# PUMA-10S_V2_1.net
KiCad netlist of a schematic drawn in Altium Designer
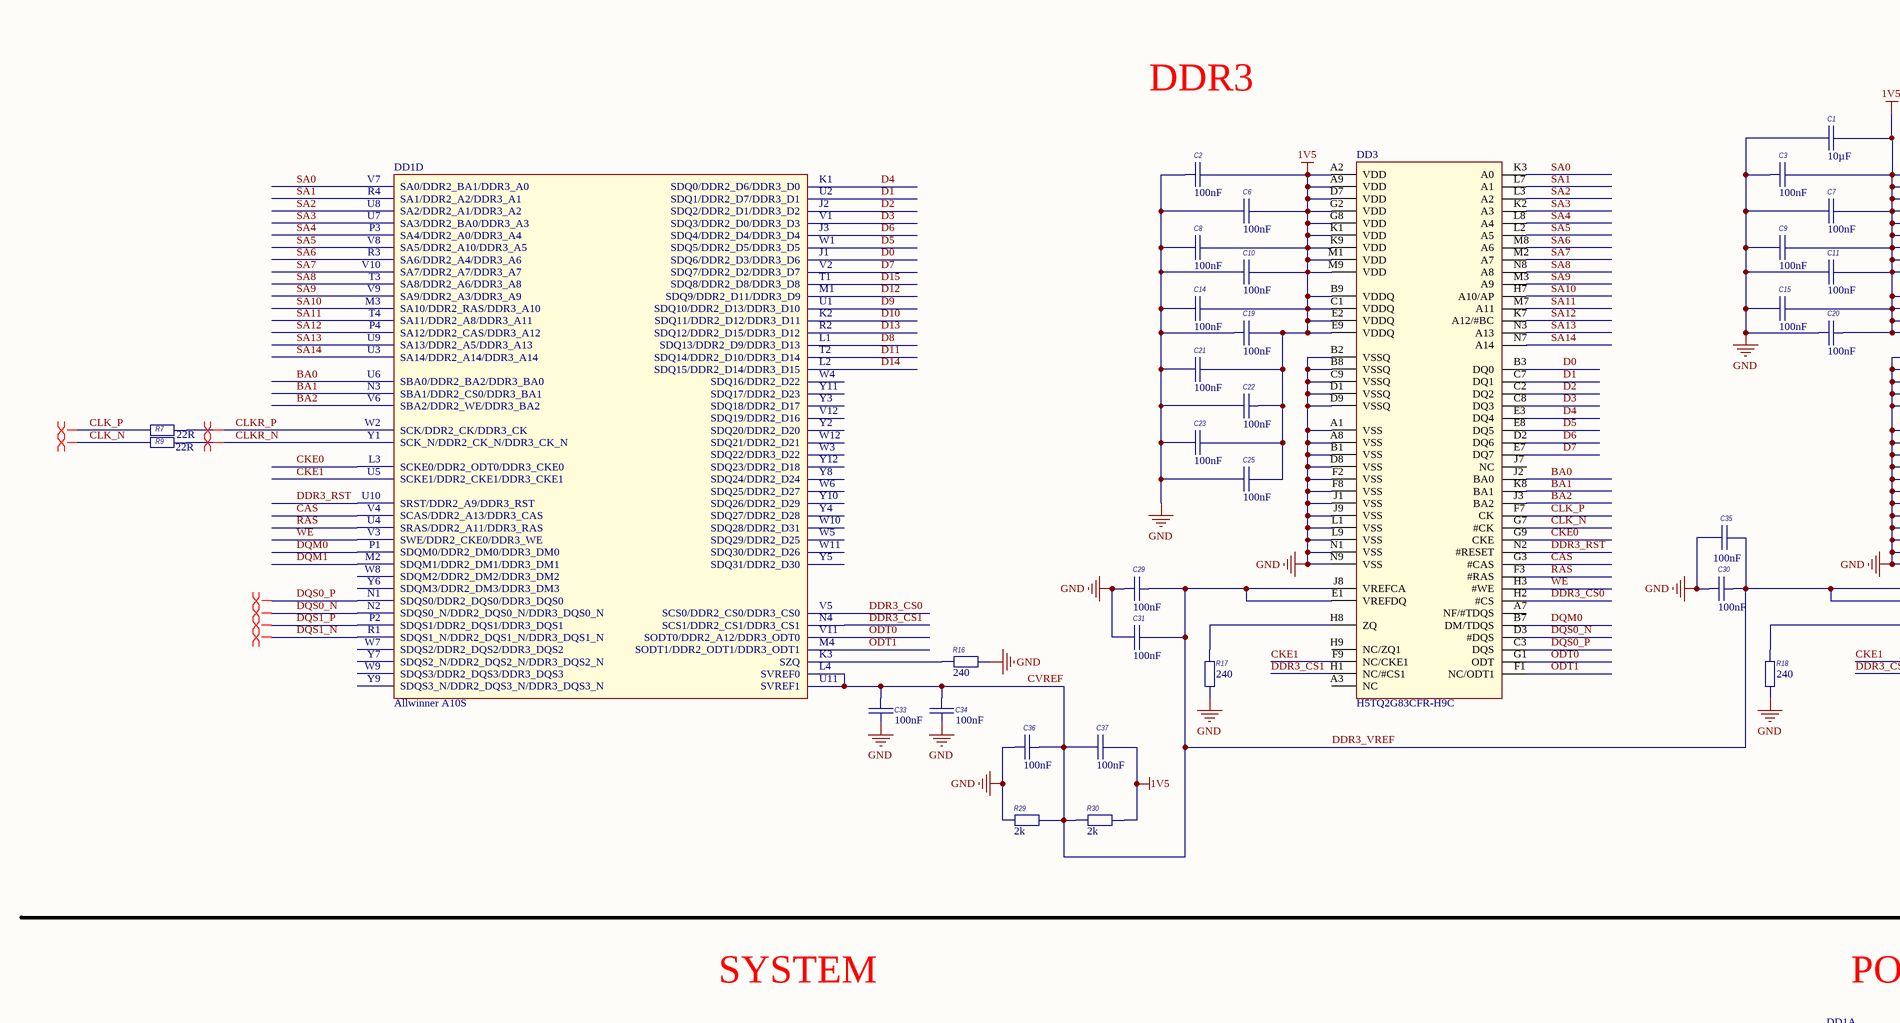
[diagram p0: PUMA-10S_V2.1.SchDoc, top left]
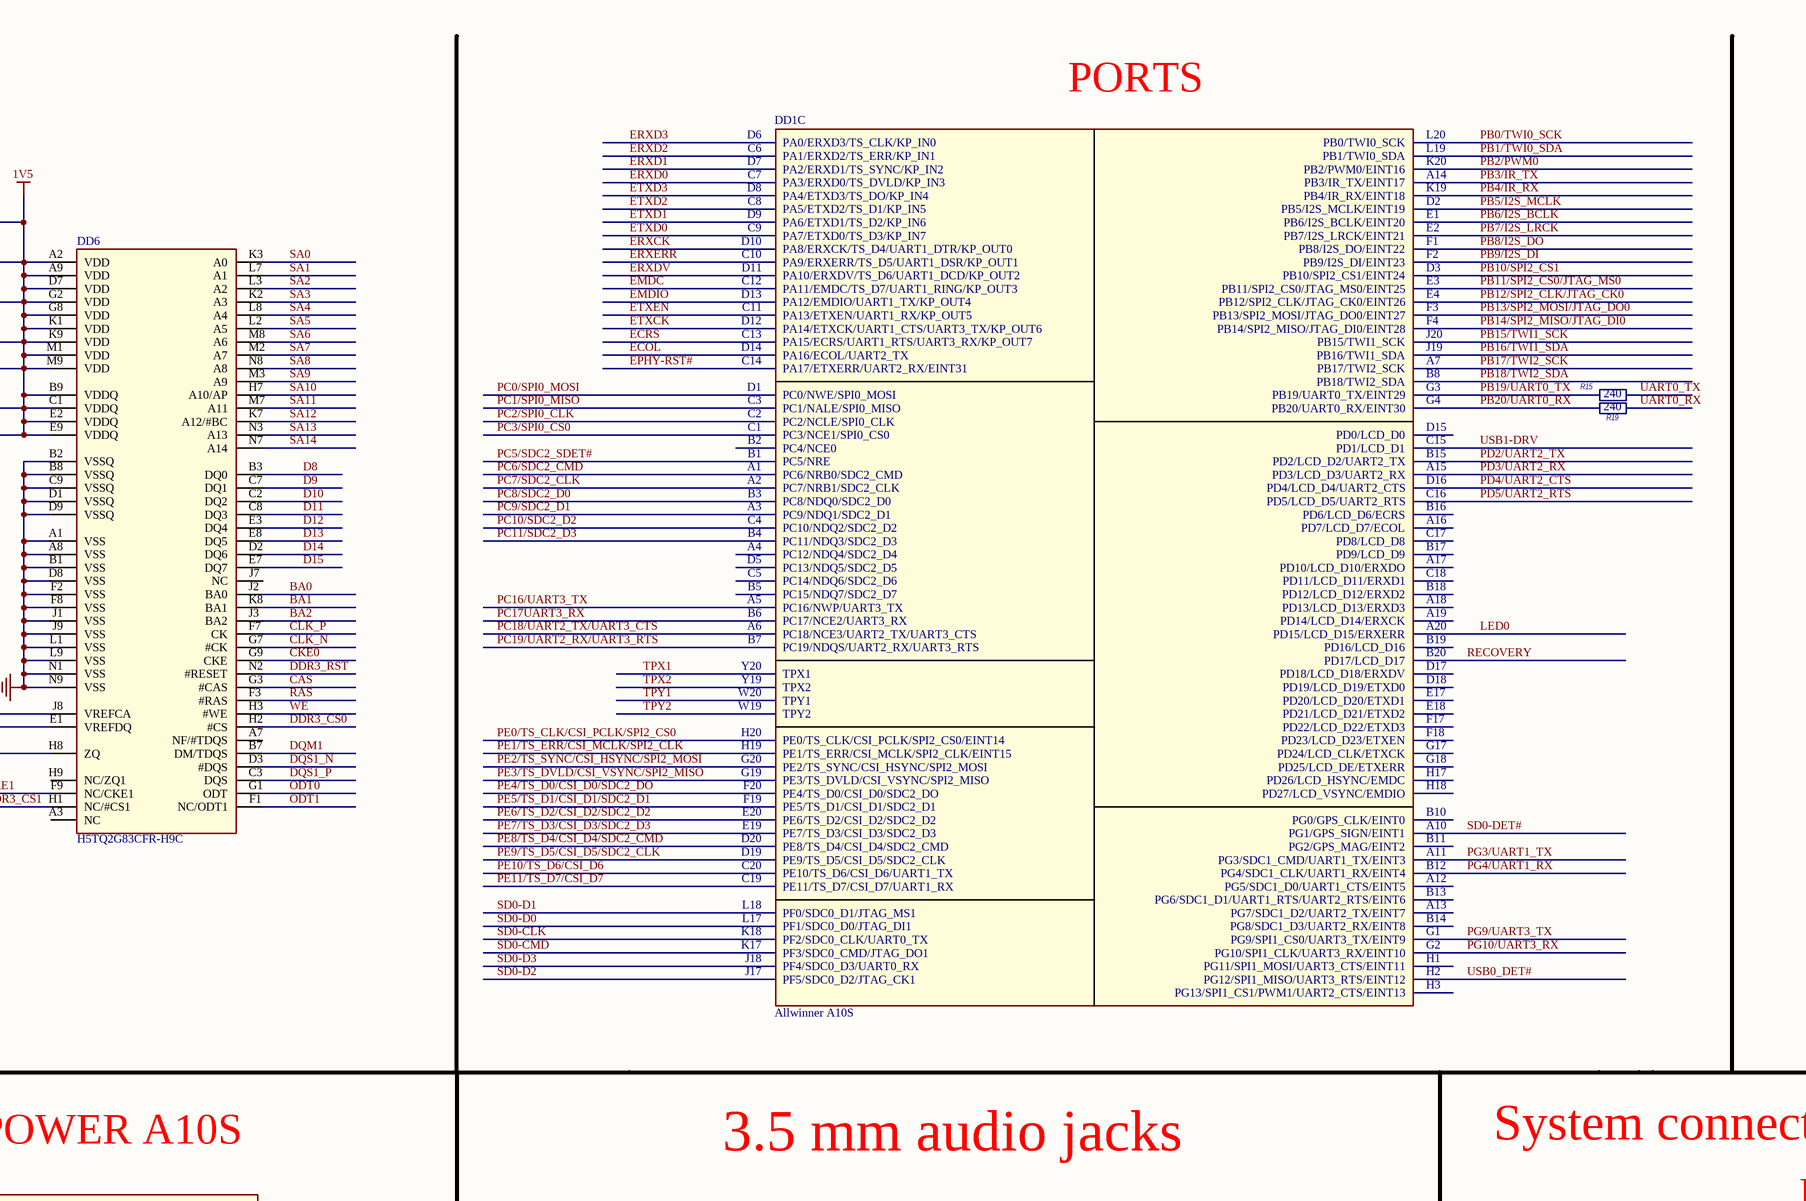
[diagram p1: PUMA-10S_V2.1.SchDoc, top middle]
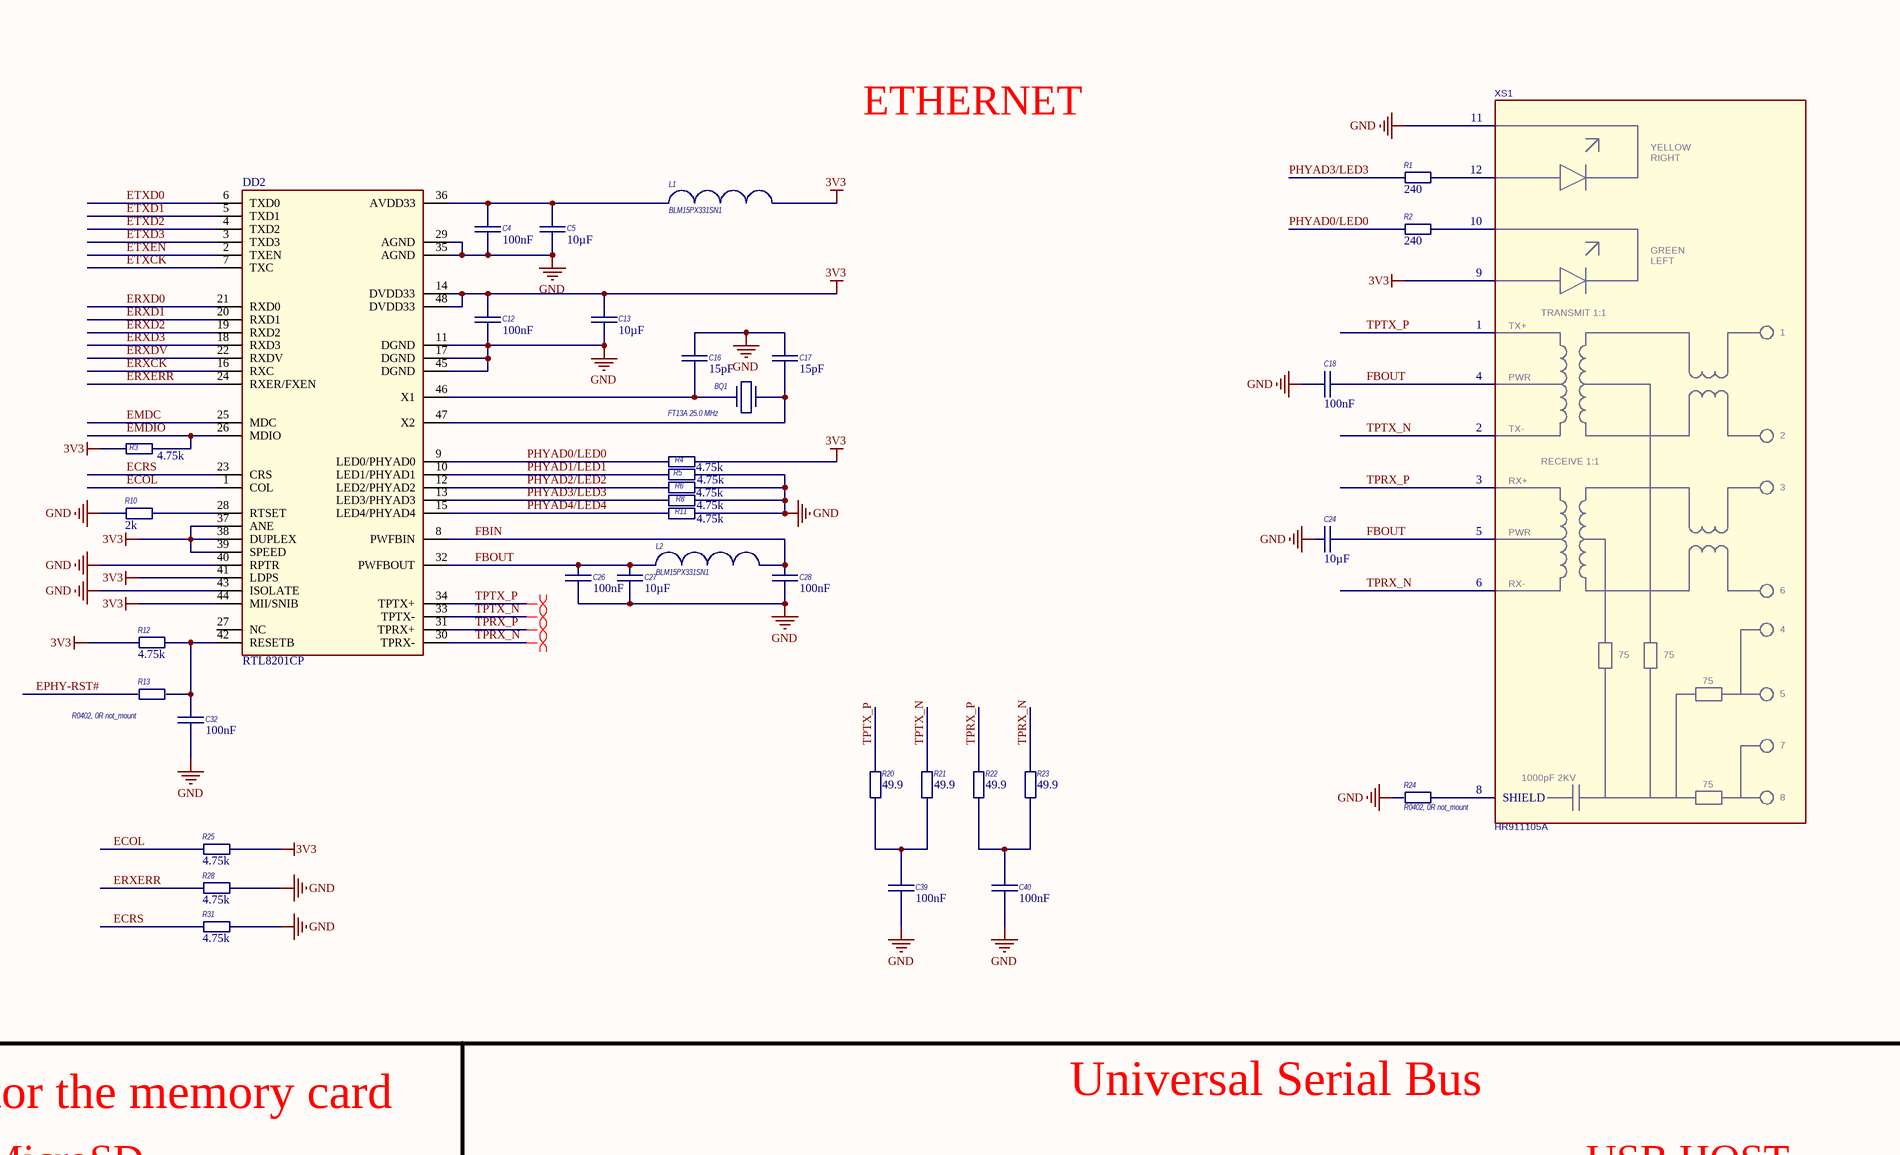
[diagram p2: PUMA-10S_V2.1.SchDoc, top right]
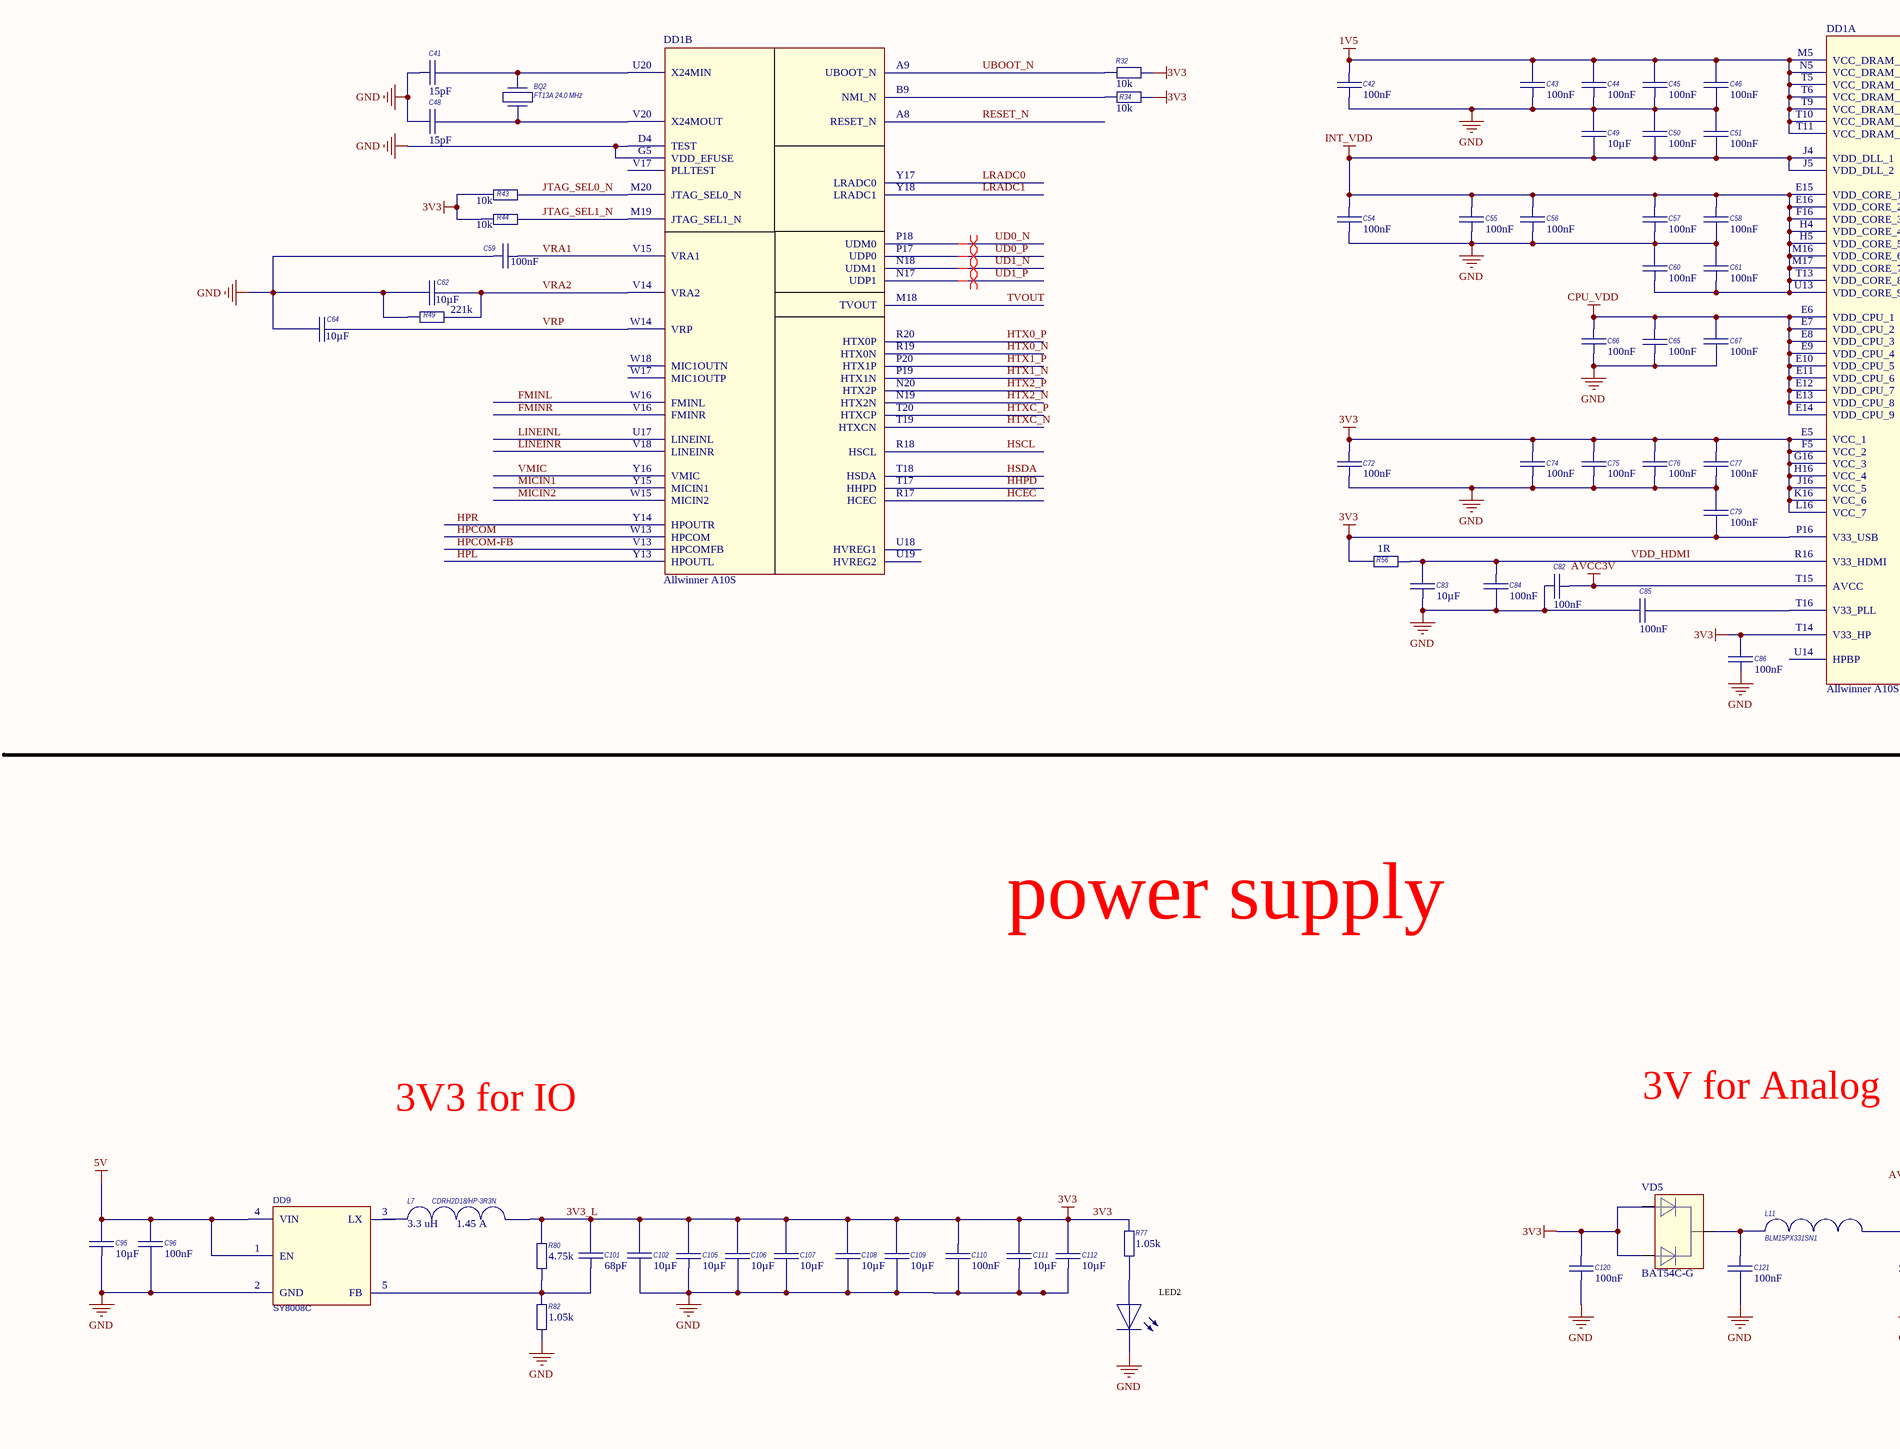
[diagram p3: PUMA-10S_V2.1.SchDoc, centre left]
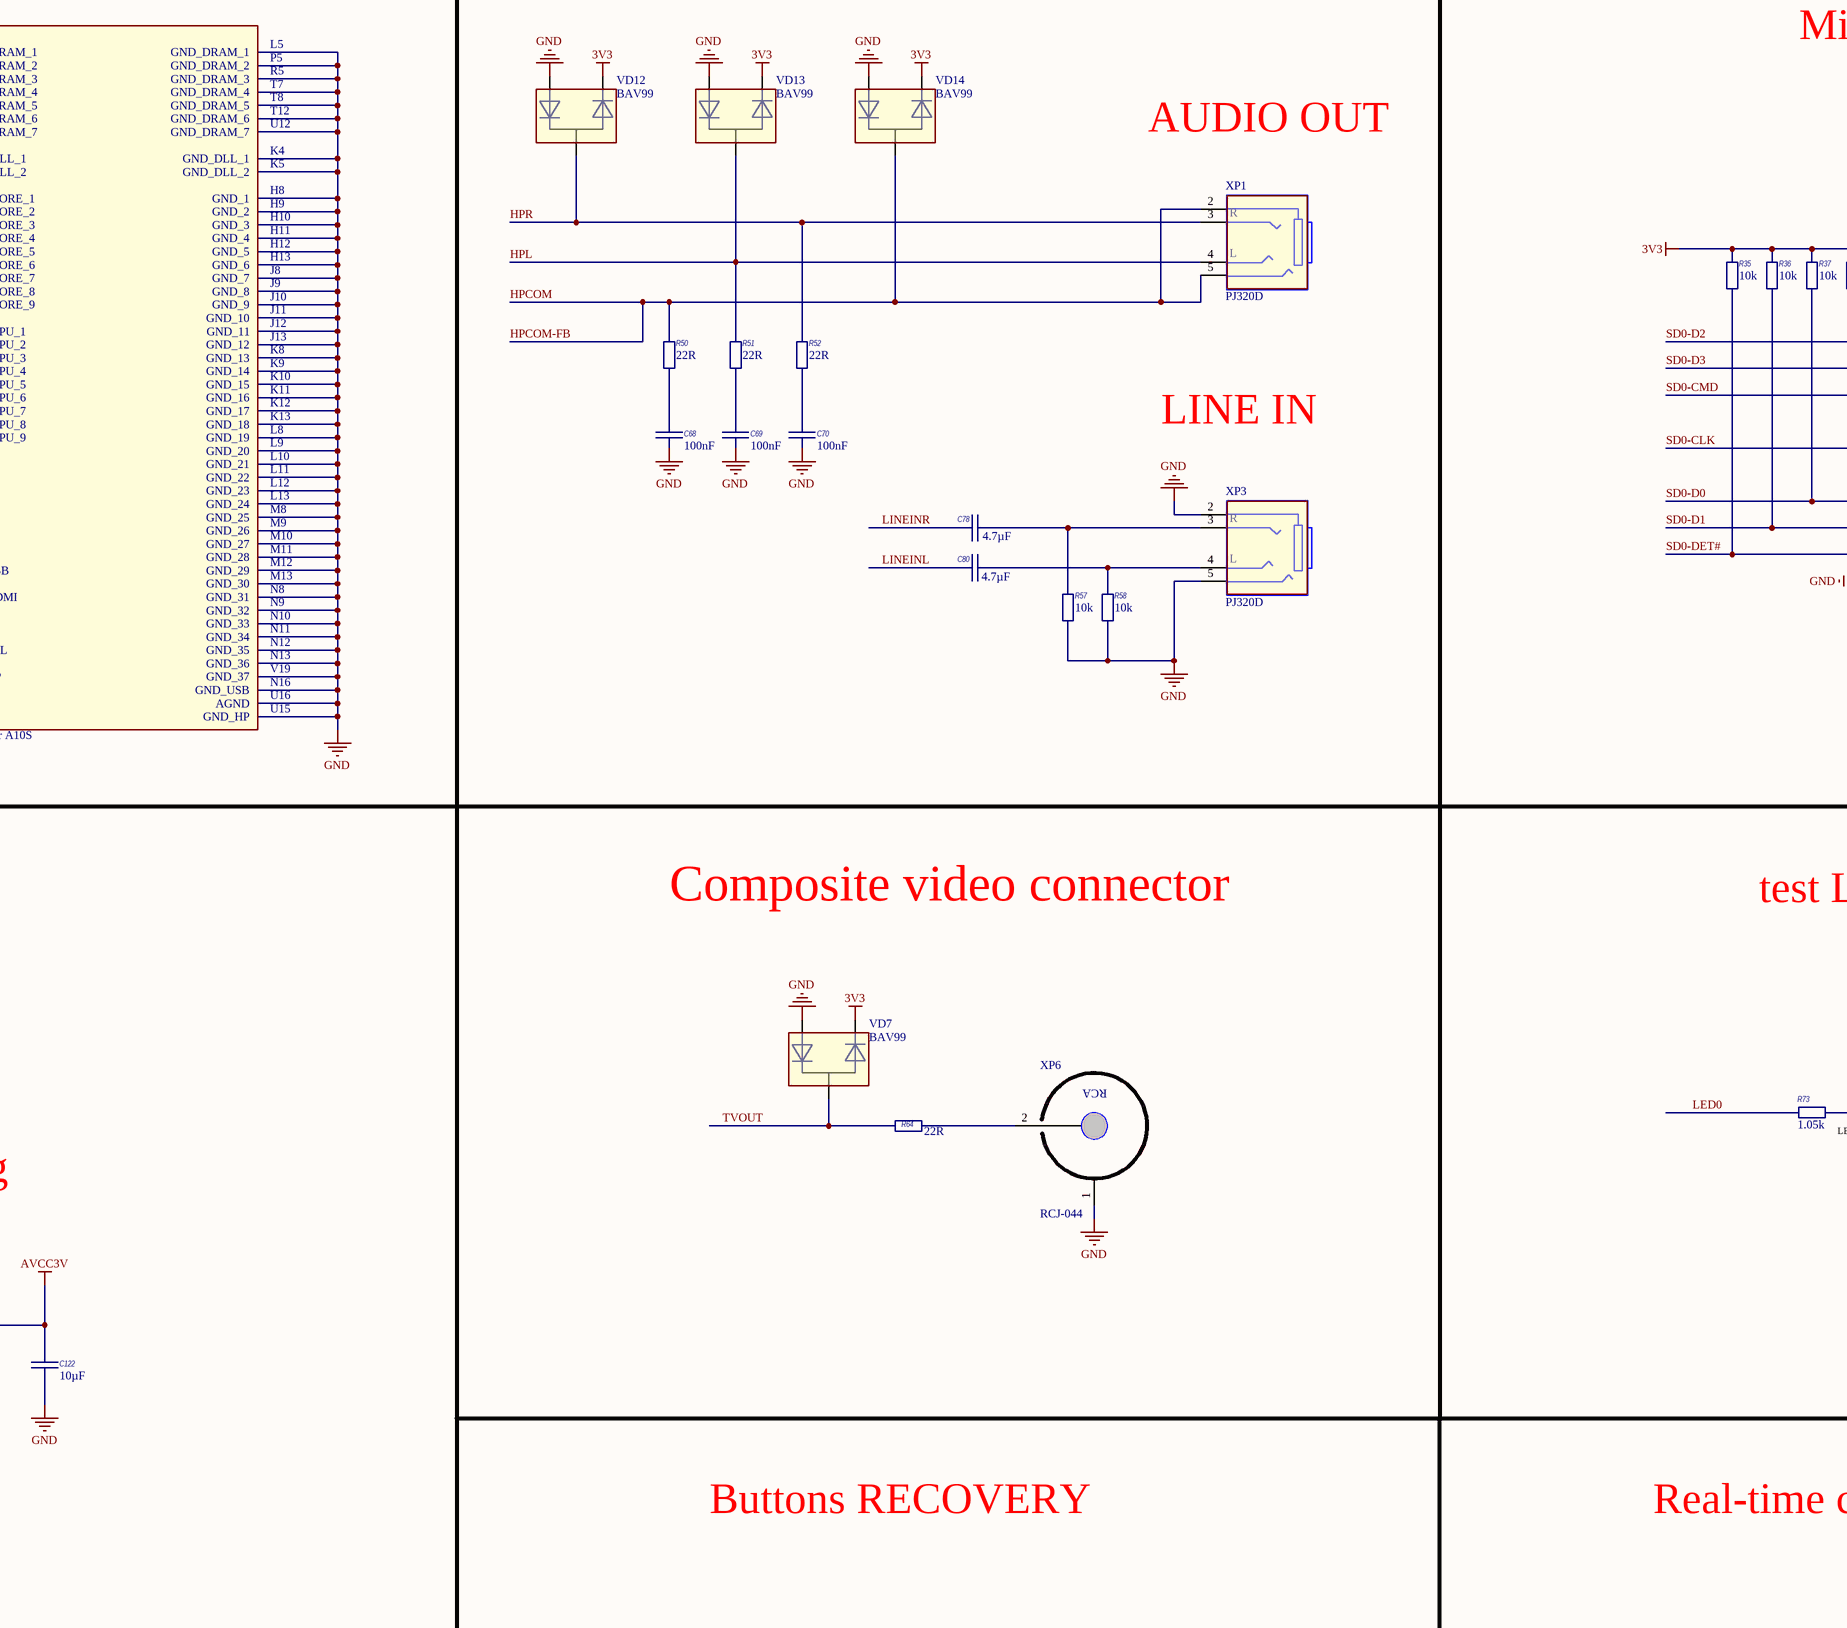
[diagram p4: PUMA-10S_V2.1.SchDoc, centre middle]
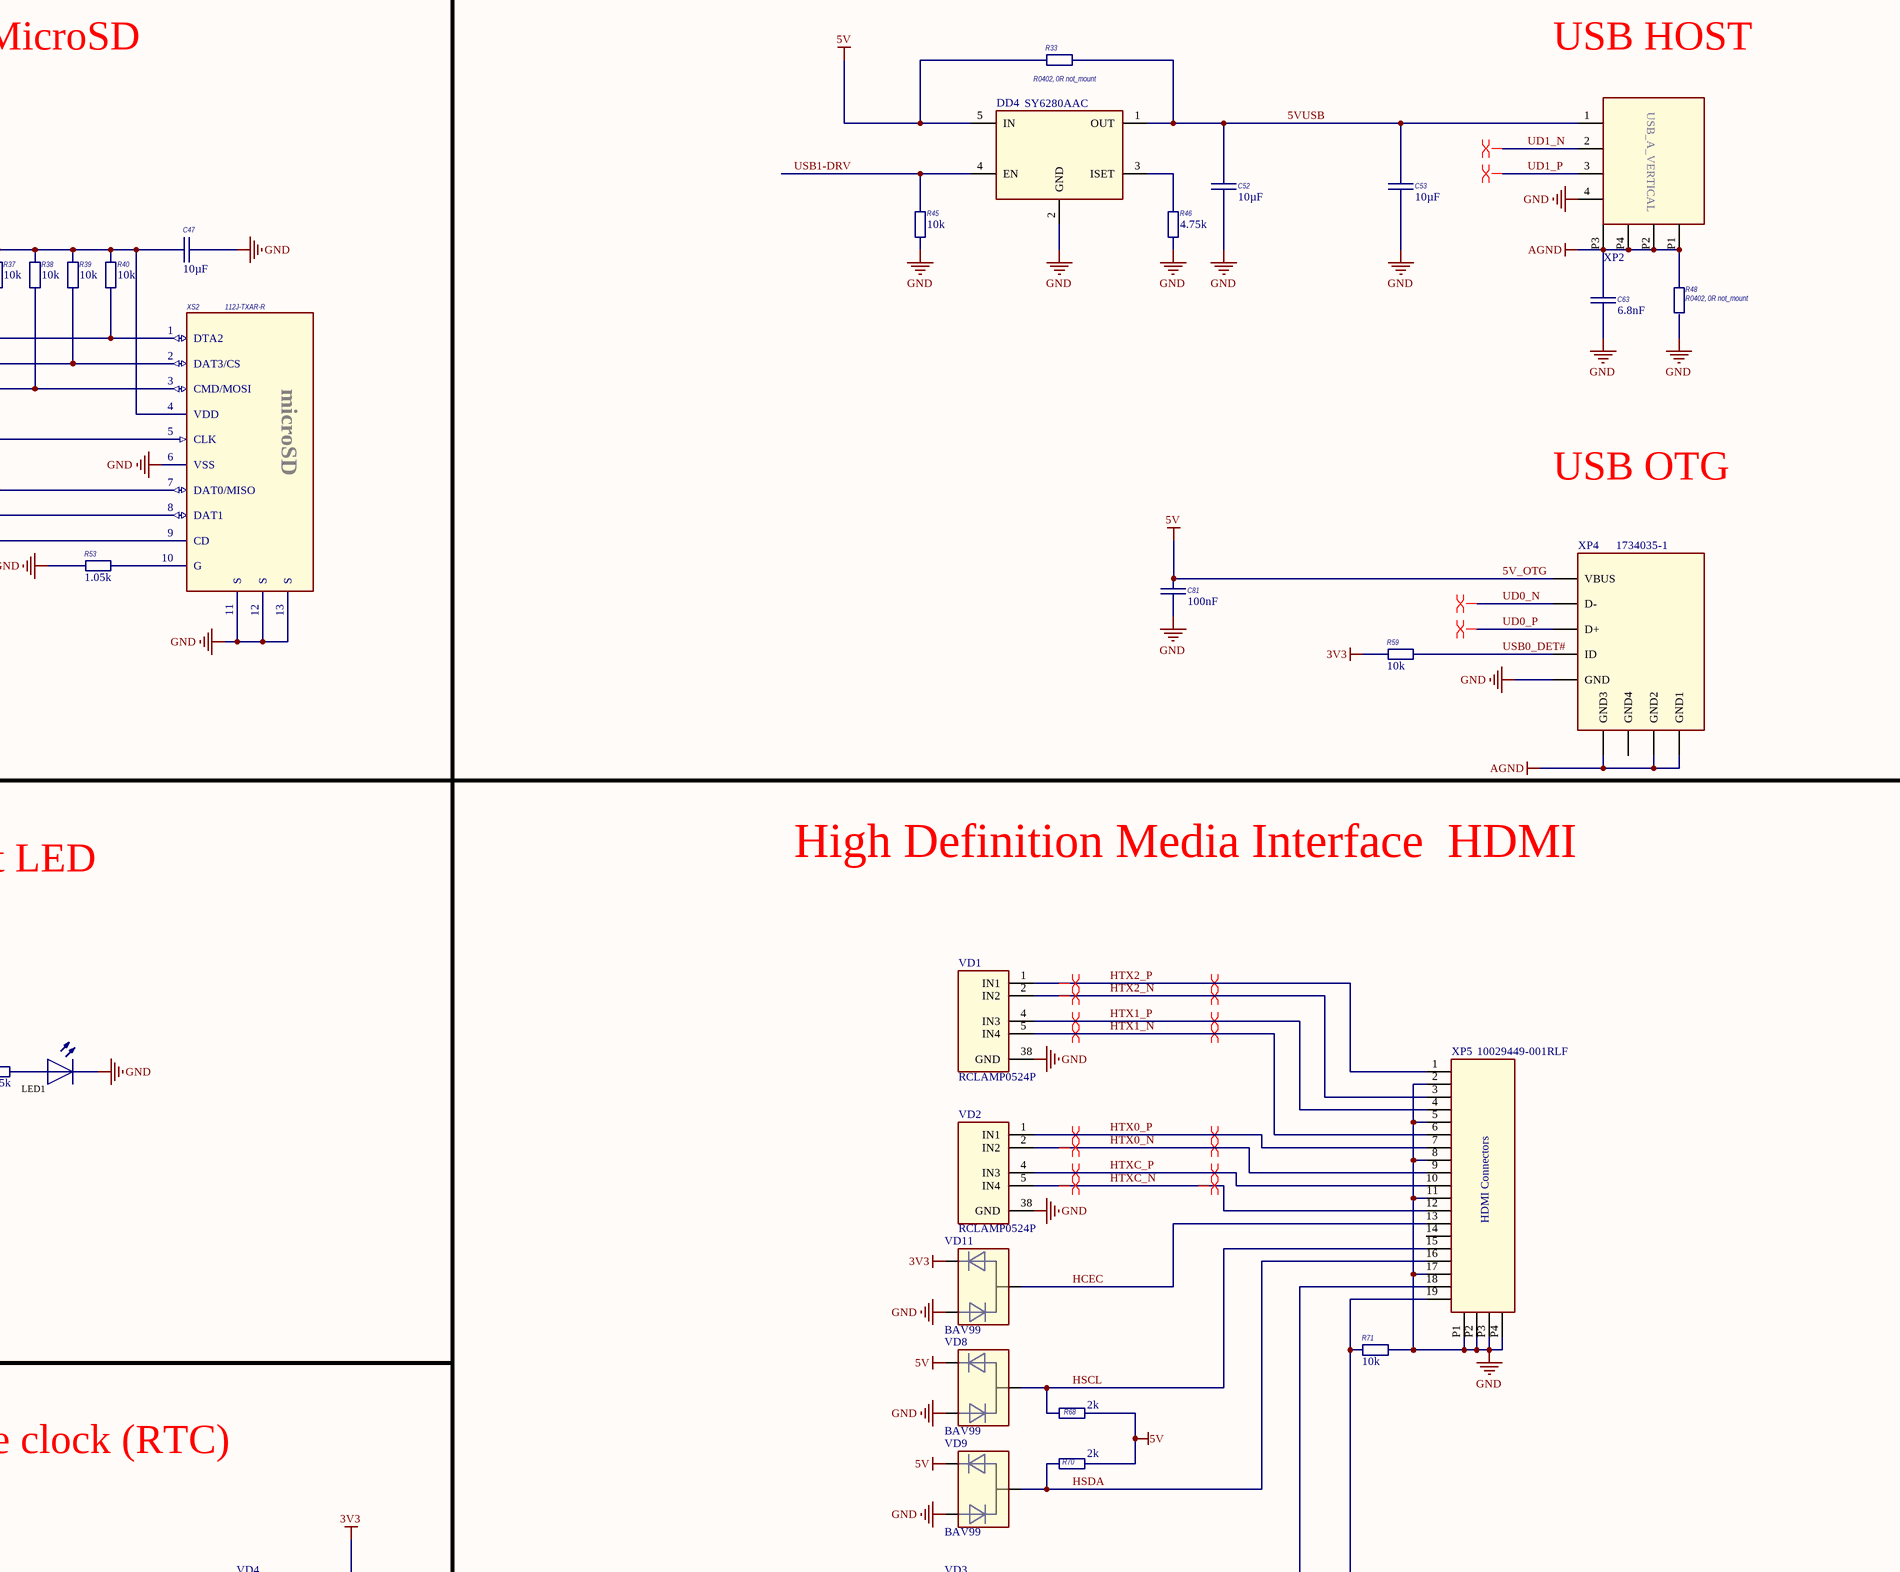
[diagram p5: PUMA-10S_V2.1.SchDoc, centre right]
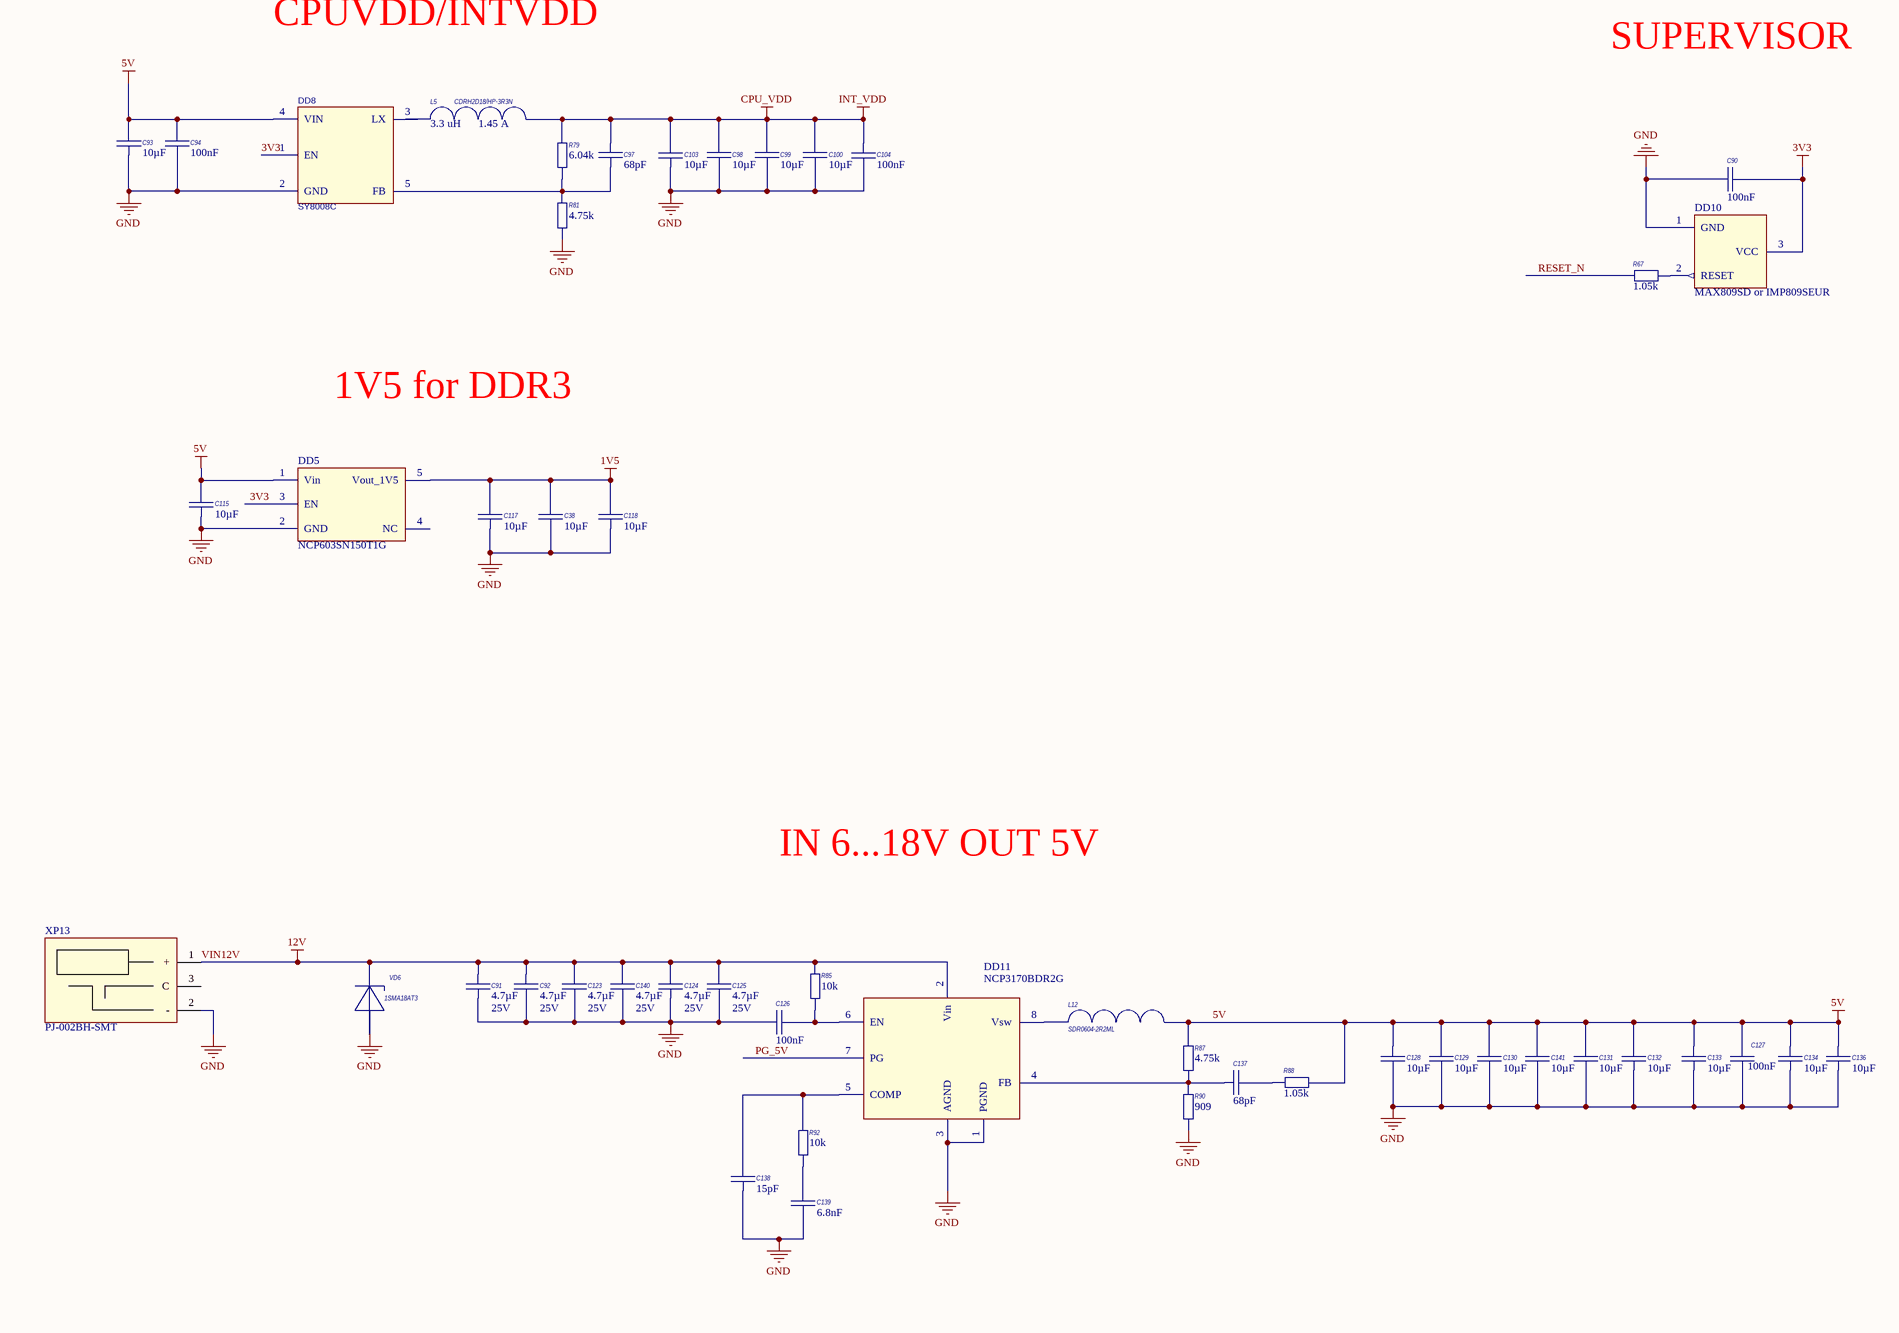
[diagram p6: PUMA-10S_V2.1.SchDoc, bottom left]
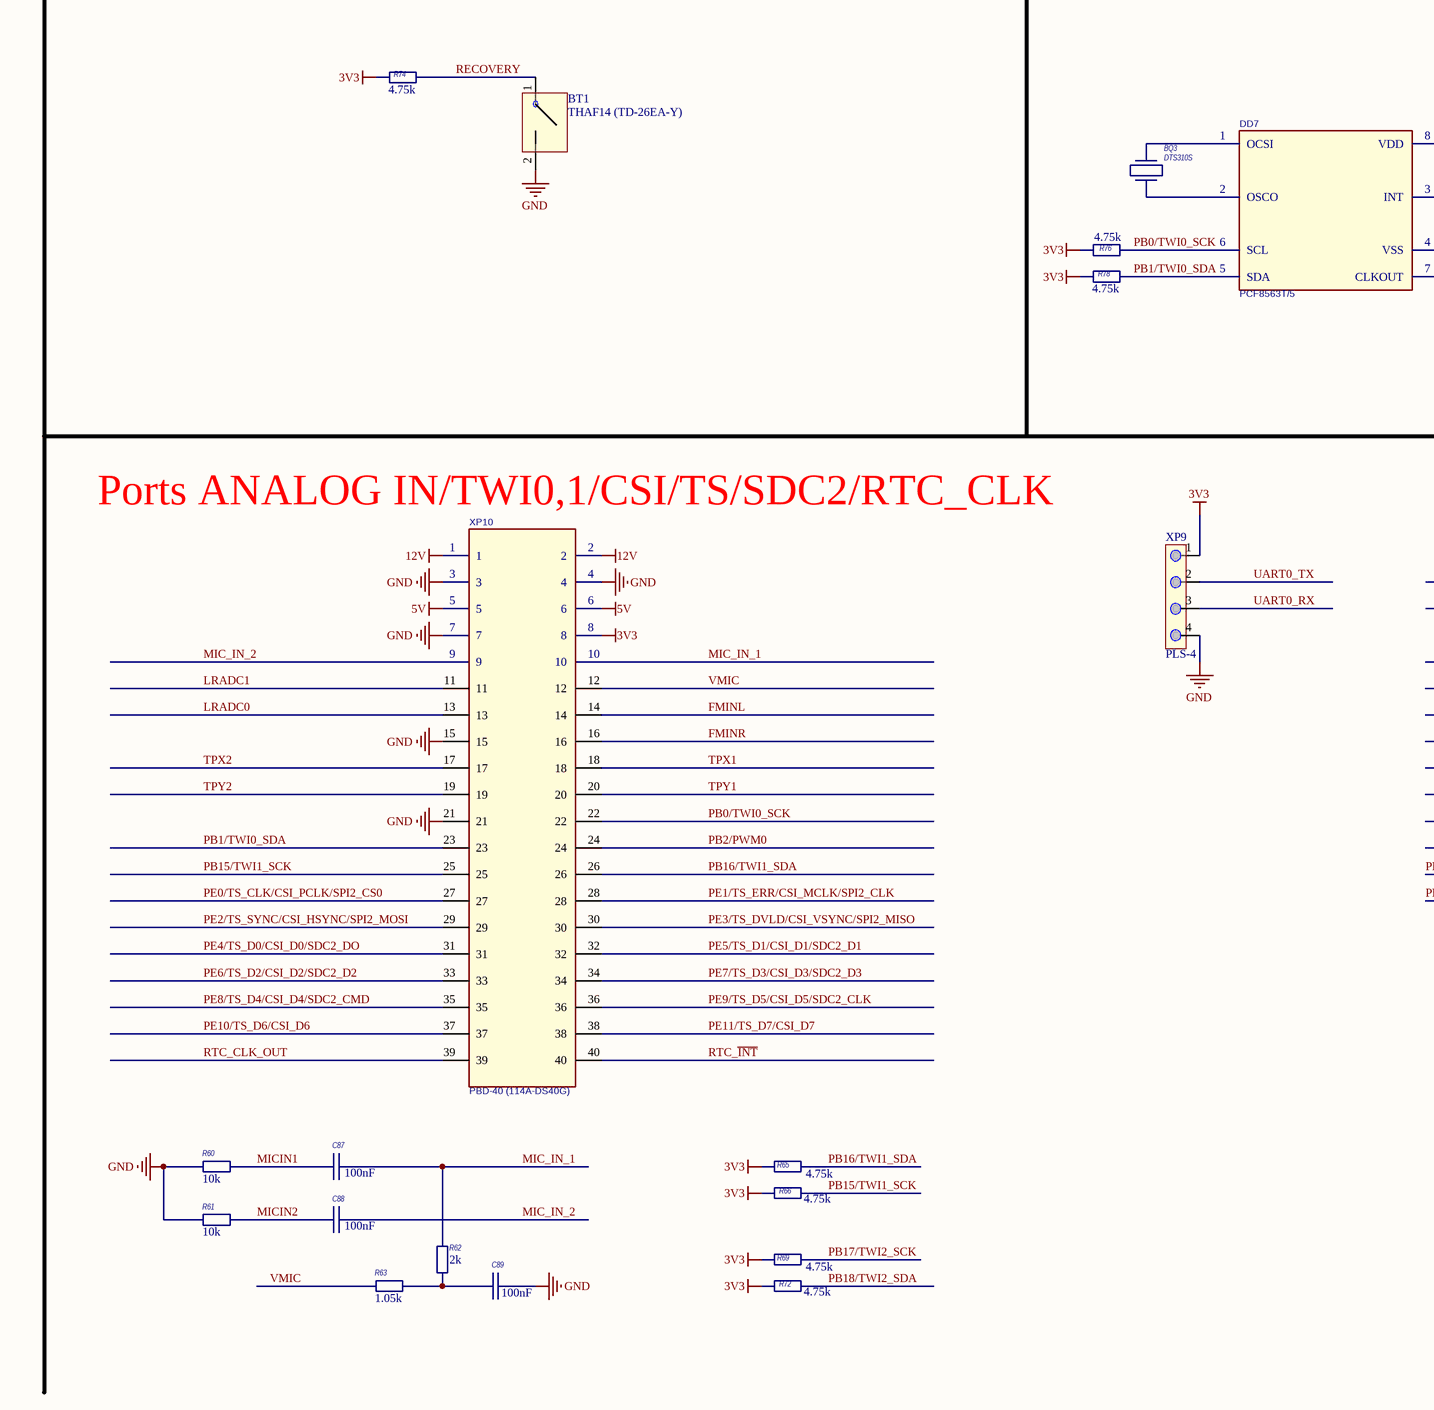
[diagram p7: PUMA-10S_V2.1.SchDoc, bottom middle]
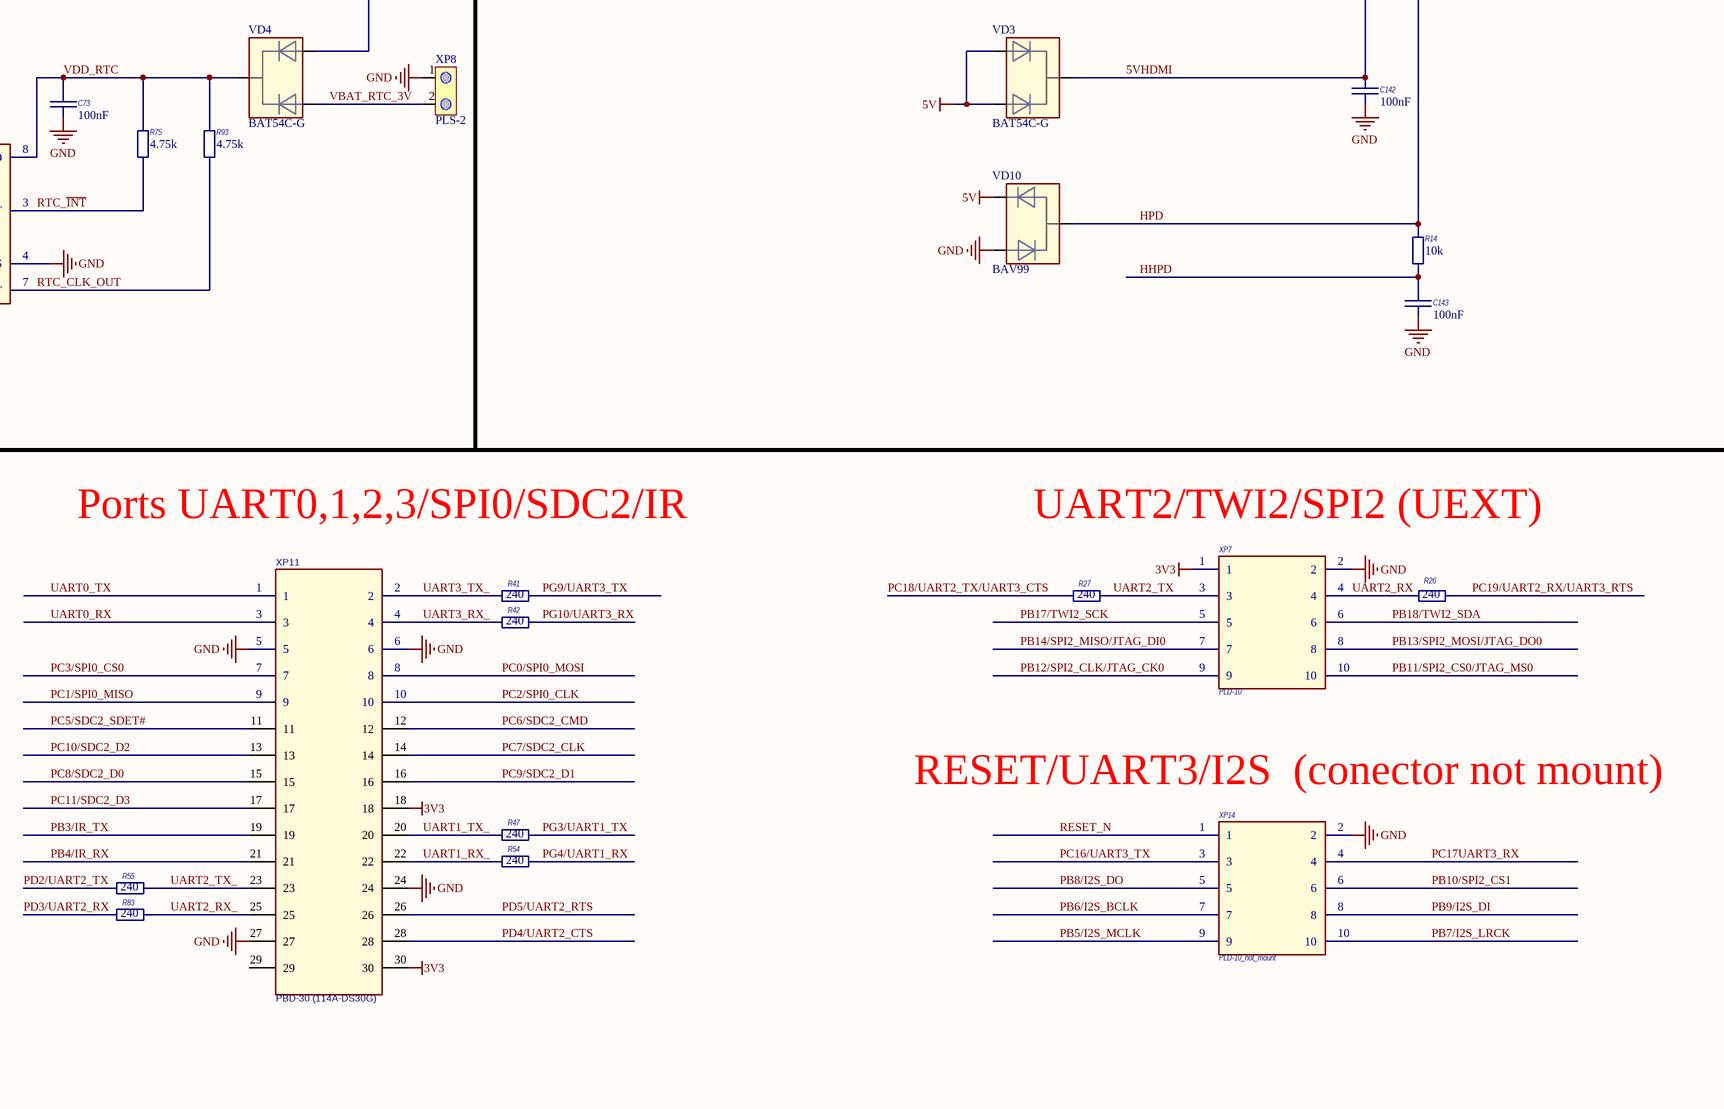
[diagram p8: PUMA-10S_V2.1.SchDoc, bottom right]

(export (version "E")
  (design (tool "Eeschema 10.0.6"))
  (components
    (comp (ref "BQ1")
      (value "FT13A 25.0 MHz")
      (footprint "3225")
      (description "CRYSTAL 25MHZ, 16pF, 50PPM, 3.2x2.5mm")
      (libsource (lib "CRYSTALS") (part "FT13A 25.0 MHz"))
    )
    (comp (ref "BQ2")
      (value "FT13A 24.0 MHz")
      (footprint "3225")
      (description "CRYSTAL 24MHZ, 16pF, 50PPM, 3.2x2.5mm")
      (libsource (lib "CRYSTALS") (part "FT13A 24.0 MHz"))
    )
    (comp (ref "BQ3")
      (value "DTS310S")
      (footprint "3215")
      (description "Crystal Resonator 32.768kHz, 12.5pF 30PPM")
      (libsource (lib "CRYSTALS") (part "Crystal Resonator 32.768kHz, 12.5pF 30PPM"))
    )
    (comp (ref "BT1")
      (value "THAF14 (TD-26EA-Y)")
      (footprint "THAF14")
      (description "Horizontal Push Tact Switch")
      (libsource (lib "PUMA-10S") (part "THAF14"))
    )
    (comp (ref "C1")
      (value "GRM188R60J106ME47")
      (footprint "C0603")
      (description "C0603 10uF 6.3V X5R")
      (fields
        (field (name "MANUFACTURER") "Murata Electronics North America")
        (field (name "MANUFACTURER PART NUMBER") "GRM188R60J106ME47D")
        (field (name "CAPACITANCE") "10µF")
      )
      (libsource (lib "CAPACITORS") (part "GRM188R60J106ME47"))
    )
    (comp (ref "C2")
      (value "GRM155R71C104KA88")
      (footprint "C0402_IPC High Density")
      (description "C0402, 100nF,  16V, X7R")
      (fields
        (field (name "MANUFACTURER") "MURATA")
        (field (name "MANUFACTURER PART NUMBER") "GRM155R71C104KA88D")
        (field (name "CAPACITANCE") "100nF")
      )
      (libsource (lib "CAPACITORS") (part "GRM155R71C104KA88"))
    )
    (comp (ref "C3")
      (value "GRM155R71C104KA88")
      (footprint "C0402_IPC High Density")
      (description "C0402, 100nF,  16V, X7R")
      (fields
        (field (name "MANUFACTURER") "MURATA")
        (field (name "MANUFACTURER PART NUMBER") "GRM155R71C104KA88D")
        (field (name "CAPACITANCE") "100nF")
      )
      (libsource (lib "CAPACITORS") (part "GRM155R71C104KA88"))
    )
    (comp (ref "C4")
      (value "GRM155R71C104KA88")
      (footprint "C0402_IPC High Density")
      (description "C0402, 100nF,  16V, X7R")
      (fields
        (field (name "MANUFACTURER") "MURATA")
        (field (name "MANUFACTURER PART NUMBER") "GRM155R71C104KA88D")
        (field (name "CAPACITANCE") "100nF")
      )
      (libsource (lib "CAPACITORS") (part "GRM155R71C104KA88"))
    )
    (comp (ref "C5")
      (value "GRM188R60J106ME47")
      (footprint "C0603")
      (description "C0603 10uF 6.3V X5R")
      (fields
        (field (name "MANUFACTURER") "Murata Electronics North America")
        (field (name "TOLERANCE") "±20%")
        (field (name "CAPACITANCE") "10µF")
      )
      (libsource (lib "CAPACITORS") (part "GRM188R60J106ME47"))
    )
    (comp (ref "C6")
      (value "GRM155R71C104KA88")
      (footprint "C0402_IPC High Density")
      (description "C0402, 100nF,  16V, X7R")
      (fields
        (field (name "MANUFACTURER") "MURATA")
        (field (name "MANUFACTURER PART NUMBER") "GRM155R71C104KA88D")
        (field (name "CAPACITANCE") "100nF")
      )
      (libsource (lib "CAPACITORS") (part "GRM155R71C104KA88"))
    )
    (comp (ref "C7")
      (value "GRM155R71C104KA88")
      (footprint "C0402_IPC High Density")
      (description "C0402, 100nF,  16V, X7R")
      (fields
        (field (name "MANUFACTURER") "MURATA")
        (field (name "MANUFACTURER PART NUMBER") "GRM155R71C104KA88D")
        (field (name "CAPACITANCE") "100nF")
      )
      (libsource (lib "CAPACITORS") (part "GRM155R71C104KA88"))
    )
    (comp (ref "C8")
      (value "GRM155R71C104KA88")
      (footprint "C0402_IPC High Density")
      (description "C0402, 100nF,  16V, X7R")
      (fields
        (field (name "MANUFACTURER") "MURATA")
        (field (name "MANUFACTURER PART NUMBER") "GRM155R71C104KA88D")
        (field (name "CAPACITANCE") "100nF")
      )
      (libsource (lib "CAPACITORS") (part "GRM155R71C104KA88"))
    )
    (comp (ref "C9")
      (value "GRM155R71C104KA88")
      (footprint "C0402_IPC High Density")
      (description "C0402, 100nF,  16V, X7R")
      (fields
        (field (name "MANUFACTURER") "MURATA")
        (field (name "MANUFACTURER PART NUMBER") "GRM155R71C104KA88D")
        (field (name "CAPACITANCE") "100nF")
      )
      (libsource (lib "CAPACITORS") (part "GRM155R71C104KA88"))
    )
    (comp (ref "C10")
      (value "GRM155R71C104KA88")
      (footprint "C0402_IPC High Density")
      (description "C0402, 100nF,  16V, X7R")
      (fields
        (field (name "MANUFACTURER") "MURATA")
        (field (name "MANUFACTURER PART NUMBER") "GRM155R71C104KA88D")
        (field (name "CAPACITANCE") "100nF")
      )
      (libsource (lib "CAPACITORS") (part "GRM155R71C104KA88"))
    )
    (comp (ref "C11")
      (value "GRM155R71C104KA88")
      (footprint "C0402_IPC High Density")
      (description "C0402, 100nF,  16V, X7R")
      (fields
        (field (name "MANUFACTURER") "MURATA")
        (field (name "MANUFACTURER PART NUMBER") "GRM155R71C104KA88D")
        (field (name "CAPACITANCE") "100nF")
      )
      (libsource (lib "CAPACITORS") (part "GRM155R71C104KA88"))
    )
    (comp (ref "C12")
      (value "GRM155R71C104KA88")
      (footprint "C0402_IPC High Density")
      (description "C0402, 100nF,  16V, X7R")
      (fields
        (field (name "MANUFACTURER") "MURATA")
        (field (name "MANUFACTURER PART NUMBER") "GRM155R71C104KA88D")
        (field (name "CAPACITANCE") "100nF")
      )
      (libsource (lib "CAPACITORS") (part "GRM155R71C104KA88"))
    )
    (comp (ref "C13")
      (value "GRM188R60J106ME47")
      (footprint "C0603")
      (description "C0603 10uF 6.3V X5R")
      (fields
        (field (name "MANUFACTURER") "Murata Electronics North America")
        (field (name "TOLERANCE") "±20%")
        (field (name "CAPACITANCE") "10µF")
      )
      (libsource (lib "CAPACITORS") (part "GRM188R60J106ME47"))
    )
    (comp (ref "C14")
      (value "GRM155R71C104KA88")
      (footprint "C0402_IPC High Density")
      (description "C0402, 100nF,  16V, X7R")
      (fields
        (field (name "MANUFACTURER") "MURATA")
        (field (name "MANUFACTURER PART NUMBER") "GRM155R71C104KA88D")
        (field (name "CAPACITANCE") "100nF")
      )
      (libsource (lib "CAPACITORS") (part "GRM155R71C104KA88"))
    )
    (comp (ref "C15")
      (value "GRM155R71C104KA88")
      (footprint "C0402_IPC High Density")
      (description "C0402, 100nF,  16V, X7R")
      (fields
        (field (name "MANUFACTURER") "MURATA")
        (field (name "MANUFACTURER PART NUMBER") "GRM155R71C104KA88D")
        (field (name "CAPACITANCE") "100nF")
      )
      (libsource (lib "CAPACITORS") (part "GRM155R71C104KA88"))
    )
    (comp (ref "C16")
      (value "GRM1555C1H150")
      (footprint "C0402_IPC High Density")
      (description "C0402, 15pF 50V, NP0")
      (fields
        (field (name "MANUFACTURER") "Murata Electronics North America")
        (field (name "MANUFACTURER PART NUMBER") "GRM1555C1H150JZ01D")
        (field (name "CAPACITANCE") "15pF")
      )
      (libsource (lib "PUMA-10S") (part "GRM1555C1H150"))
    )
    (comp (ref "C17")
      (value "GRM1555C1H150")
      (footprint "C0402_IPC High Density")
      (description "C0402, 15pF 50V, NP0")
      (fields
        (field (name "MANUFACTURER") "Murata Electronics North America")
        (field (name "MANUFACTURER PART NUMBER") "GRM1555C1H150JZ01D")
        (field (name "CAPACITANCE") "15pF")
      )
      (libsource (lib "PUMA-10S") (part "GRM1555C1H150"))
    )
    (comp (ref "C18")
      (value "GRM155R71C104KA88")
      (footprint "C0402_IPC High Density")
      (description "C0402, 100nF,  16V, X7R")
      (fields
        (field (name "MANUFACTURER") "MURATA")
        (field (name "MANUFACTURER PART NUMBER") "GRM155R71C104KA88D")
        (field (name "CAPACITANCE") "100nF")
      )
      (libsource (lib "CAPACITORS") (part "GRM155R71C104KA88"))
    )
    (comp (ref "C19")
      (value "GRM155R71C104KA88")
      (footprint "C0402_IPC High Density")
      (description "C0402, 100nF,  16V, X7R")
      (fields
        (field (name "MANUFACTURER") "MURATA")
        (field (name "MANUFACTURER PART NUMBER") "GRM155R71C104KA88D")
        (field (name "CAPACITANCE") "100nF")
      )
      (libsource (lib "CAPACITORS") (part "GRM155R71C104KA88"))
    )
    (comp (ref "C20")
      (value "GRM155R71C104KA88")
      (footprint "C0402_IPC High Density")
      (description "C0402, 100nF,  16V, X7R")
      (fields
        (field (name "MANUFACTURER") "MURATA")
        (field (name "MANUFACTURER PART NUMBER") "GRM155R71C104KA88D")
        (field (name "CAPACITANCE") "100nF")
      )
      (libsource (lib "CAPACITORS") (part "GRM155R71C104KA88"))
    )
    (comp (ref "C21")
      (value "GRM155R71C104KA88")
      (footprint "C0402_IPC High Density")
      (description "C0402, 100nF,  16V, X7R")
      (fields
        (field (name "MANUFACTURER") "MURATA")
        (field (name "MANUFACTURER PART NUMBER") "GRM155R71C104KA88D")
        (field (name "CAPACITANCE") "100nF")
      )
      (libsource (lib "CAPACITORS") (part "GRM155R71C104KA88"))
    )
    (comp (ref "C22")
      (value "GRM155R71C104KA88")
      (footprint "C0402_IPC High Density")
      (description "C0402, 100nF,  16V, X7R")
      (fields
        (field (name "MANUFACTURER") "MURATA")
        (field (name "MANUFACTURER PART NUMBER") "GRM155R71C104KA88D")
        (field (name "CAPACITANCE") "100nF")
      )
      (libsource (lib "CAPACITORS") (part "GRM155R71C104KA88"))
    )
    (comp (ref "C23")
      (value "GRM155R71C104KA88")
      (footprint "C0402_IPC High Density")
      (description "C0402, 100nF,  16V, X7R")
      (fields
        (field (name "MANUFACTURER") "MURATA")
        (field (name "MANUFACTURER PART NUMBER") "GRM155R71C104KA88D")
        (field (name "CAPACITANCE") "100nF")
      )
      (libsource (lib "CAPACITORS") (part "GRM155R71C104KA88"))
    )
    (comp (ref "C24")
      (value "GRM188R60J106ME47")
      (footprint "C0603")
      (description "C0603 10uF 6.3V X5R")
      (fields
        (field (name "MANUFACTURER") "Murata Electronics North America")
        (field (name "TOLERANCE") "±20%")
        (field (name "CAPACITANCE") "10µF")
      )
      (libsource (lib "CAPACITORS") (part "GRM188R60J106ME47"))
    )
    (comp (ref "C25")
      (value "GRM155R71C104KA88")
      (footprint "C0402_IPC High Density")
      (description "C0402, 100nF,  16V, X7R")
      (fields
        (field (name "MANUFACTURER") "MURATA")
        (field (name "MANUFACTURER PART NUMBER") "GRM155R71C104KA88D")
        (field (name "CAPACITANCE") "100nF")
      )
      (libsource (lib "CAPACITORS") (part "GRM155R71C104KA88"))
    )
    (comp (ref "C26")
      (value "GRM155R71C104KA88")
      (footprint "C0402_IPC High Density")
      (description "C0402, 100nF,  16V, X7R")
      (fields
        (field (name "MANUFACTURER") "MURATA")
        (field (name "MANUFACTURER PART NUMBER") "GRM155R71C104KA88D")
        (field (name "CAPACITANCE") "100nF")
      )
      (libsource (lib "CAPACITORS") (part "GRM155R71C104KA88"))
    )
    (comp (ref "C27")
      (value "GRM188R60J106ME47")
      (footprint "C0603")
      (description "C0603 10uF 6.3V X5R")
      (fields
        (field (name "MANUFACTURER") "Murata Electronics North America")
        (field (name "TOLERANCE") "±20%")
        (field (name "CAPACITANCE") "10µF")
      )
      (libsource (lib "CAPACITORS") (part "GRM188R60J106ME47"))
    )
    (comp (ref "C28")
      (value "GRM155R71C104KA88")
      (footprint "C0402_IPC High Density")
      (description "C0402, 100nF,  16V, X7R")
      (fields
        (field (name "MANUFACTURER") "MURATA")
        (field (name "MANUFACTURER PART NUMBER") "GRM155R71C104KA88D")
        (field (name "CAPACITANCE") "100nF")
      )
      (libsource (lib "CAPACITORS") (part "GRM155R71C104KA88"))
    )
    (comp (ref "C29")
      (value "GRM155R71C104KA88")
      (footprint "C0402_IPC High Density")
      (description "C0402, 100nF,  16V, X7R")
      (fields
        (field (name "MANUFACTURER") "MURATA")
        (field (name "MANUFACTURER PART NUMBER") "GRM155R71C104KA88D")
        (field (name "CAPACITANCE") "100nF")
      )
      (libsource (lib "CAPACITORS") (part "GRM155R71C104KA88"))
    )
    (comp (ref "C30")
      (value "GRM155R71C104KA88")
      (footprint "C0402_IPC High Density")
      (description "C0402, 100nF,  16V, X7R")
      (fields
        (field (name "MANUFACTURER") "MURATA")
        (field (name "MANUFACTURER PART NUMBER") "GRM155R71C104KA88D")
        (field (name "CAPACITANCE") "100nF")
      )
      (libsource (lib "CAPACITORS") (part "GRM155R71C104KA88"))
    )
    (comp (ref "C31")
      (value "GRM155R71C104KA88")
      (footprint "C0402_IPC High Density")
      (description "C0402, 100nF,  16V, X7R")
      (fields
        (field (name "MANUFACTURER") "MURATA")
        (field (name "MANUFACTURER PART NUMBER") "GRM155R71C104KA88D")
        (field (name "CAPACITANCE") "100nF")
      )
      (libsource (lib "CAPACITORS") (part "GRM155R71C104KA88"))
    )
    (comp (ref "C32")
      (value "GRM155R71C104KA88")
      (footprint "C0402_IPC High Density")
      (description "C0402, 100nF,  16V, X7R")
      (fields
        (field (name "MANUFACTURER") "MURATA")
        (field (name "MANUFACTURER PART NUMBER") "GRM155R71C104KA88D")
        (field (name "CAPACITANCE") "100nF")
      )
      (libsource (lib "CAPACITORS") (part "GRM155R71C104KA88"))
    )
    (comp (ref "C33")
      (value "GRM155R71C104KA88")
      (footprint "C0402_IPC High Density")
      (description "C0402, 100nF,  16V, X7R")
      (fields
        (field (name "MANUFACTURER") "MURATA")
        (field (name "MANUFACTURER PART NUMBER") "GRM155R71C104KA88D")
        (field (name "CAPACITANCE") "100nF")
      )
      (libsource (lib "CAPACITORS") (part "GRM155R71C104KA88"))
    )
    (comp (ref "C34")
      (value "GRM155R71C104KA88")
      (footprint "C0402_IPC High Density")
      (description "C0402, 100nF,  16V, X7R")
      (fields
        (field (name "MANUFACTURER") "MURATA")
        (field (name "MANUFACTURER PART NUMBER") "GRM155R71C104KA88D")
        (field (name "CAPACITANCE") "100nF")
      )
      (libsource (lib "CAPACITORS") (part "GRM155R71C104KA88"))
    )
    (comp (ref "C35")
      (value "GRM155R71C104KA88")
      (footprint "C0402_IPC High Density")
      (description "C0402, 100nF,  16V, X7R")
      (fields
        (field (name "MANUFACTURER") "MURATA")
        (field (name "MANUFACTURER PART NUMBER") "GRM155R71C104KA88D")
        (field (name "CAPACITANCE") "100nF")
      )
      (libsource (lib "CAPACITORS") (part "GRM155R71C104KA88"))
    )
    (comp (ref "C36")
      (value "GRM155R71C104KA88")
      (footprint "C0402_IPC High Density")
      (description "C0402, 100nF,  16V, X7R")
      (fields
        (field (name "MANUFACTURER") "MURATA")
        (field (name "MANUFACTURER PART NUMBER") "GRM155R71C104KA88D")
        (field (name "CAPACITANCE") "100nF")
      )
      (libsource (lib "CAPACITORS") (part "GRM155R71C104KA88"))
    )
    (comp (ref "C37")
      (value "GRM155R71C104KA88")
      (footprint "C0402_IPC High Density")
      (description "C0402, 100nF,  16V, X7R")
      (fields
        (field (name "MANUFACTURER") "MURATA")
        (field (name "MANUFACTURER PART NUMBER") "GRM155R71C104KA88D")
        (field (name "CAPACITANCE") "100nF")
      )
      (libsource (lib "CAPACITORS") (part "GRM155R71C104KA88"))
    )
    (comp (ref "C38")
      (value "GRM188R60J106ME47")
      (footprint "C0603")
      (description "C0603 10uF 6.3V X5R")
      (fields
        (field (name "MANUFACTURER") "Murata Electronics North America")
        (field (name "MANUFACTURER PART NUMBER") "GRM188R60J106ME47D")
        (field (name "CAPACITANCE") "10µF")
      )
      (libsource (lib "CAPACITORS") (part "GRM188R60J106ME47"))
    )
    (comp (ref "C39")
      (value "GRM155R71C104KA88")
      (footprint "C0402_IPC High Density")
      (description "C0402, 100nF,  16V, X7R")
      (fields
        (field (name "MANUFACTURER") "MURATA")
        (field (name "MANUFACTURER PART NUMBER") "GRM155R71C104KA88D")
        (field (name "CAPACITANCE") "100nF")
      )
      (libsource (lib "CAPACITORS") (part "GRM155R71C104KA88"))
    )
    (comp (ref "C40")
      (value "GRM155R71C104KA88")
      (footprint "C0402_IPC High Density")
      (description "C0402, 100nF,  16V, X7R")
      (fields
        (field (name "MANUFACTURER") "MURATA")
        (field (name "MANUFACTURER PART NUMBER") "GRM155R71C104KA88D")
        (field (name "CAPACITANCE") "100nF")
      )
      (libsource (lib "CAPACITORS") (part "GRM155R71C104KA88"))
    )
    (comp (ref "C41")
      (value "GRM1555C1H150")
      (footprint "C0402_IPC High Density")
      (description "C0402, 15pF 50V, NP0")
      (fields
        (field (name "MANUFACTURER PART NUMBER") "GRM1555C1H150JZ01D")
        (field (name "MANUFACTURER") "Murata Electronics North America")
        (field (name "CAPACITANCE") "15pF")
      )
      (libsource (lib "PUMA-10S") (part "GRM1555C1H150"))
    )
    (comp (ref "C42")
      (value "GRM155R71C104KA88")
      (footprint "C0402_IPC High Density")
      (description "C0402, 100nF,  16V, X7R")
      (fields
        (field (name "MANUFACTURER") "MURATA")
        (field (name "MANUFACTURER PART NUMBER") "GRM155R71C104KA88D")
        (field (name "CAPACITANCE") "100nF")
      )
      (libsource (lib "CAPACITORS") (part "GRM155R71C104KA88"))
    )
    (comp (ref "C43")
      (value "GRM155R71C104KA88")
      (footprint "C0402_IPC High Density")
      (description "C0402, 100nF,  16V, X7R")
      (fields
        (field (name "MANUFACTURER") "MURATA")
        (field (name "MANUFACTURER PART NUMBER") "GRM155R71C104KA88D")
        (field (name "CAPACITANCE") "100nF")
      )
      (libsource (lib "CAPACITORS") (part "GRM155R71C104KA88"))
    )
    (comp (ref "C44")
      (value "GRM155R71C104KA88")
      (footprint "C0402_IPC High Density")
      (description "C0402, 100nF,  16V, X7R")
      (fields
        (field (name "MANUFACTURER") "MURATA")
        (field (name "MANUFACTURER PART NUMBER") "GRM155R71C104KA88D")
        (field (name "CAPACITANCE") "100nF")
      )
      (libsource (lib "CAPACITORS") (part "GRM155R71C104KA88"))
    )
    (comp (ref "C45")
      (value "GRM155R71C104KA88")
      (footprint "C0402_IPC High Density")
      (description "C0402, 100nF,  16V, X7R")
      (fields
        (field (name "MANUFACTURER") "MURATA")
        (field (name "MANUFACTURER PART NUMBER") "GRM155R71C104KA88D")
        (field (name "CAPACITANCE") "100nF")
      )
      (libsource (lib "CAPACITORS") (part "GRM155R71C104KA88"))
    )
    (comp (ref "C46")
      (value "GRM155R71C104KA88")
      (footprint "C0402_IPC High Density")
      (description "C0402, 100nF,  16V, X7R")
      (fields
        (field (name "MANUFACTURER") "MURATA")
        (field (name "MANUFACTURER PART NUMBER") "GRM155R71C104KA88D")
        (field (name "CAPACITANCE") "100nF")
      )
      (libsource (lib "CAPACITORS") (part "GRM155R71C104KA88"))
    )
    (comp (ref "C47")
      (value "GRM188R60J106ME47")
      (footprint "C0603")
      (description "C0603 10uF 6.3V X5R")
      (fields
        (field (name "MANUFACTURER") "Murata Electronics North America")
        (field (name "MANUFACTURER PART NUMBER") "GRM188R60J106ME47D")
        (field (name "CAPACITANCE") "10µF")
      )
      (libsource (lib "CAPACITORS") (part "GRM188R60J106ME47"))
    )
    (comp (ref "C48")
      (value "GRM1555C1H150")
      (footprint "C0402_IPC High Density")
      (description "C0402, 15pF 50V, NP0")
      (fields
        (field (name "MANUFACTURER PART NUMBER") "GRM1555C1H150JZ01D")
        (field (name "MANUFACTURER") "Murata Electronics North America")
        (field (name "CAPACITANCE") "15pF")
      )
      (libsource (lib "PUMA-10S") (part "GRM1555C1H150"))
    )
    (comp (ref "C49")
      (value "GRM188R60J106ME47")
      (footprint "C0603")
      (description "C0603 10uF 6.3V X5R")
      (fields
        (field (name "MANUFACTURER") "Murata Electronics North America")
        (field (name "TOLERANCE") "±20%")
        (field (name "CAPACITANCE") "10µF")
      )
      (libsource (lib "CAPACITORS") (part "GRM188R60J106ME47"))
    )
    (comp (ref "C50")
      (value "GRM155R71C104KA88")
      (footprint "C0402_IPC High Density")
      (description "C0402, 100nF,  16V, X7R")
      (fields
        (field (name "MANUFACTURER") "MURATA")
        (field (name "MANUFACTURER PART NUMBER") "GRM155R71C104KA88D")
        (field (name "CAPACITANCE") "100nF")
      )
      (libsource (lib "CAPACITORS") (part "GRM155R71C104KA88"))
    )
    (comp (ref "C51")
      (value "GRM155R71C104KA88")
      (footprint "C0402_IPC High Density")
      (description "C0402, 100nF,  16V, X7R")
      (fields
        (field (name "MANUFACTURER") "MURATA")
        (field (name "MANUFACTURER PART NUMBER") "GRM155R71C104KA88D")
        (field (name "CAPACITANCE") "100nF")
      )
      (libsource (lib "CAPACITORS") (part "GRM155R71C104KA88"))
    )
    (comp (ref "C52")
      (value "GRM188R60J106ME47")
      (footprint "C0603")
      (description "C0603 10uF 6.3V X5R")
      (fields
        (field (name "MANUFACTURER") "Murata Electronics North America")
        (field (name "MANUFACTURER PART NUMBER") "GRM188R60J106ME47D")
        (field (name "CAPACITANCE") "10µF")
      )
      (libsource (lib "CAPACITORS") (part "GRM188R60J106ME47"))
    )
    (comp (ref "C53")
      (value "GRM188R60J106ME47")
      (footprint "C0603")
      (description "C0603 10uF 6.3V X5R")
      (fields
        (field (name "MANUFACTURER") "Murata Electronics North America")
        (field (name "TOLERANCE") "±20%")
        (field (name "CAPACITANCE") "10µF")
      )
      (libsource (lib "CAPACITORS") (part "GRM188R60J106ME47"))
    )
    (comp (ref "C54")
      (value "GRM155R71C104KA88")
      (footprint "C0402_IPC High Density")
      (description "C0402, 100nF,  16V, X7R")
      (fields
        (field (name "MANUFACTURER") "MURATA")
        (field (name "MANUFACTURER PART NUMBER") "GRM155R71C104KA88D")
        (field (name "CAPACITANCE") "100nF")
      )
      (libsource (lib "CAPACITORS") (part "GRM155R71C104KA88"))
    )
    (comp (ref "C55")
      (value "GRM155R71C104KA88")
      (footprint "C0402_IPC High Density")
      (description "C0402, 100nF,  16V, X7R")
      (fields
        (field (name "MANUFACTURER") "MURATA")
        (field (name "MANUFACTURER PART NUMBER") "GRM155R71C104KA88D")
        (field (name "CAPACITANCE") "100nF")
      )
      (libsource (lib "CAPACITORS") (part "GRM155R71C104KA88"))
    )
    (comp (ref "C56")
      (value "GRM155R71C104KA88")
      (footprint "C0402_IPC High Density")
      (description "C0402, 100nF,  16V, X7R")
      (fields
        (field (name "MANUFACTURER") "MURATA")
        (field (name "MANUFACTURER PART NUMBER") "GRM155R71C104KA88D")
        (field (name "CAPACITANCE") "100nF")
      )
      (libsource (lib "CAPACITORS") (part "GRM155R71C104KA88"))
    )
    (comp (ref "C57")
      (value "GRM155R71C104KA88")
      (footprint "C0402_IPC High Density")
      (description "C0402, 100nF,  16V, X7R")
      (fields
        (field (name "MANUFACTURER") "MURATA")
        (field (name "MANUFACTURER PART NUMBER") "GRM155R71C104KA88D")
        (field (name "CAPACITANCE") "100nF")
      )
      (libsource (lib "CAPACITORS") (part "GRM155R71C104KA88"))
    )
    (comp (ref "C58")
      (value "GRM155R71C104KA88")
      (footprint "C0402_IPC High Density")
      (description "C0402, 100nF,  16V, X7R")
      (fields
        (field (name "MANUFACTURER") "MURATA")
        (field (name "MANUFACTURER PART NUMBER") "GRM155R71C104KA88D")
        (field (name "CAPACITANCE") "100nF")
      )
      (libsource (lib "CAPACITORS") (part "GRM155R71C104KA88"))
    )
    (comp (ref "C59")
      (value "GRM155R71C104KA88")
      (footprint "C0402_IPC High Density")
      (description "C0402, 100nF,  16V, X7R")
      (fields
        (field (name "MANUFACTURER") "MURATA")
        (field (name "MANUFACTURER PART NUMBER") "GRM155R71C104KA88D")
        (field (name "CAPACITANCE") "100nF")
      )
      (libsource (lib "CAPACITORS") (part "GRM155R71C104KA88"))
    )
    (comp (ref "C60")
      (value "GRM155R71C104KA88")
      (footprint "C0402_IPC High Density")
      (description "C0402, 100nF,  16V, X7R")
      (fields
        (field (name "MANUFACTURER") "MURATA")
        (field (name "MANUFACTURER PART NUMBER") "GRM155R71C104KA88D")
        (field (name "CAPACITANCE") "100nF")
      )
      (libsource (lib "CAPACITORS") (part "GRM155R71C104KA88"))
    )
    (comp (ref "C61")
      (value "GRM155R71C104KA88")
      (footprint "C0402_IPC High Density")
      (description "C0402, 100nF,  16V, X7R")
      (fields
        (field (name "MANUFACTURER") "MURATA")
        (field (name "MANUFACTURER PART NUMBER") "GRM155R71C104KA88D")
        (field (name "CAPACITANCE") "100nF")
      )
      (libsource (lib "CAPACITORS") (part "GRM155R71C104KA88"))
    )
    (comp (ref "C62")
      (value "GRM188R60J106ME47")
      (footprint "C0603")
      (description "C0603 10uF 6.3V X5R")
      (fields
        (field (name "MANUFACTURER") "Murata Electronics North America")
        (field (name "TOLERANCE") "±20%")
        (field (name "CAPACITANCE") "10µF")
      )
      (libsource (lib "CAPACITORS") (part "GRM188R60J106ME47"))
    )
    (comp (ref "C63")
      (value "GRM155R71E682KA01")
      (footprint "C0402_IPC High Density")
      (description "C0402, 6.8nF 5%,  25V, X7R")
      (fields (field (name "CAPACITANCE") "6.8nF"))
      (libsource (lib "CAPACITORS") (part "GRM155R71E682KA01"))
    )
    (comp (ref "C64")
      (value "GRM188R60J106ME47")
      (footprint "C0603")
      (description "C0603 10uF 6.3V X5R")
      (fields
        (field (name "MANUFACTURER") "Murata Electronics North America")
        (field (name "TOLERANCE") "±20%")
        (field (name "CAPACITANCE") "10µF")
      )
      (libsource (lib "CAPACITORS") (part "GRM188R60J106ME47"))
    )
    (comp (ref "C65")
      (value "GRM155R71C104KA88")
      (footprint "C0402_IPC High Density")
      (description "C0402, 100nF,  16V, X7R")
      (fields
        (field (name "MANUFACTURER") "MURATA")
        (field (name "MANUFACTURER PART NUMBER") "GRM155R71C104KA88D")
        (field (name "CAPACITANCE") "100nF")
      )
      (libsource (lib "CAPACITORS") (part "GRM155R71C104KA88"))
    )
    (comp (ref "C66")
      (value "GRM155R71C104KA88")
      (footprint "C0402_IPC High Density")
      (description "C0402, 100nF,  16V, X7R")
      (fields
        (field (name "MANUFACTURER") "MURATA")
        (field (name "MANUFACTURER PART NUMBER") "GRM155R71C104KA88D")
        (field (name "CAPACITANCE") "100nF")
      )
      (libsource (lib "CAPACITORS") (part "GRM155R71C104KA88"))
    )
    (comp (ref "C67")
      (value "GRM155R71C104KA88")
      (footprint "C0402_IPC High Density")
      (description "C0402, 100nF,  16V, X7R")
      (fields
        (field (name "MANUFACTURER") "MURATA")
        (field (name "MANUFACTURER PART NUMBER") "GRM155R71C104KA88D")
        (field (name "CAPACITANCE") "100nF")
      )
      (libsource (lib "CAPACITORS") (part "GRM155R71C104KA88"))
    )
    (comp (ref "C68")
      (value "GRM155R71C104KA88")
      (footprint "C0402_IPC High Density")
      (description "C0402, 100nF,  16V, X7R")
      (fields
        (field (name "MANUFACTURER") "MURATA")
        (field (name "MANUFACTURER PART NUMBER") "GRM155R71C104KA88D")
        (field (name "CAPACITANCE") "100nF")
      )
      (libsource (lib "CAPACITORS") (part "GRM155R71C104KA88"))
    )
    (comp (ref "C69")
      (value "GRM155R71C104KA88")
      (footprint "C0402_IPC High Density")
      (description "C0402, 100nF,  16V, X7R")
      (fields
        (field (name "MANUFACTURER") "MURATA")
        (field (name "MANUFACTURER PART NUMBER") "GRM155R71C104KA88D")
        (field (name "CAPACITANCE") "100nF")
      )
      (libsource (lib "CAPACITORS") (part "GRM155R71C104KA88"))
    )
    (comp (ref "C70")
      (value "GRM155R71C104KA88")
      (footprint "C0402_IPC High Density")
      (description "C0402, 100nF,  16V, X7R")
      (fields
        (field (name "MANUFACTURER") "MURATA")
        (field (name "MANUFACTURER PART NUMBER") "GRM155R71C104KA88D")
        (field (name "CAPACITANCE") "100nF")
      )
      (libsource (lib "CAPACITORS") (part "GRM155R71C104KA88"))
    )
    (comp (ref "C72")
      (value "GRM155R71C104KA88")
      (footprint "C0402_IPC High Density")
      (description "C0402, 100nF,  16V, X7R")
      (fields
        (field (name "MANUFACTURER") "MURATA")
        (field (name "MANUFACTURER PART NUMBER") "GRM155R71C104KA88D")
        (field (name "CAPACITANCE") "100nF")
      )
      (libsource (lib "CAPACITORS") (part "GRM155R71C104KA88"))
    )
    (comp (ref "C73")
      (value "GRM155R71C104KA88")
      (footprint "C0402_IPC High Density")
      (description "C0402, 100nF,  16V, X7R")
      (fields
        (field (name "MANUFACTURER") "MURATA")
        (field (name "MANUFACTURER PART NUMBER") "GRM155R71C104KA88D")
        (field (name "CAPACITANCE") "100nF")
      )
      (libsource (lib "CAPACITORS") (part "GRM155R71C104KA88"))
    )
    (comp (ref "C74")
      (value "GRM155R71C104KA88")
      (footprint "C0402_IPC High Density")
      (description "C0402, 100nF,  16V, X7R")
      (fields
        (field (name "MANUFACTURER") "MURATA")
        (field (name "MANUFACTURER PART NUMBER") "GRM155R71C104KA88D")
        (field (name "CAPACITANCE") "100nF")
      )
      (libsource (lib "CAPACITORS") (part "GRM155R71C104KA88"))
    )
    (comp (ref "C75")
      (value "GRM155R71C104KA88")
      (footprint "C0402_IPC High Density")
      (description "C0402, 100nF,  16V, X7R")
      (fields
        (field (name "MANUFACTURER") "MURATA")
        (field (name "MANUFACTURER PART NUMBER") "GRM155R71C104KA88D")
        (field (name "CAPACITANCE") "100nF")
      )
      (libsource (lib "CAPACITORS") (part "GRM155R71C104KA88"))
    )
    (comp (ref "C76")
      (value "GRM155R71C104KA88")
      (footprint "C0402_IPC High Density")
      (description "C0402, 100nF,  16V, X7R")
      (fields
        (field (name "MANUFACTURER") "MURATA")
        (field (name "MANUFACTURER PART NUMBER") "GRM155R71C104KA88D")
        (field (name "CAPACITANCE") "100nF")
      )
      (libsource (lib "CAPACITORS") (part "GRM155R71C104KA88"))
    )
    (comp (ref "C77")
      (value "GRM155R71C104KA88")
      (footprint "C0402_IPC High Density")
      (description "C0402, 100nF,  16V, X7R")
      (fields
        (field (name "MANUFACTURER") "MURATA")
        (field (name "MANUFACTURER PART NUMBER") "GRM155R71C104KA88D")
        (field (name "CAPACITANCE") "100nF")
      )
      (libsource (lib "CAPACITORS") (part "GRM155R71C104KA88"))
    )
    (comp (ref "C78")
      (value "GRM21BR61E475KA12")
      (footprint "CAPC2012[0805]")
      (description "C0805, 4.7uF 10%, 25V, X5R")
      (fields
        (field (name "MANUFACTURER") "Murata Electronics North America")
        (field (name "TOLERANCE") "±10%")
        (field (name "CAPACITANCE") "4.7µF")
      )
      (libsource (lib "CAPACITORS") (part "GRM21BR61E475KA12"))
    )
    (comp (ref "C79")
      (value "GRM155R71C104KA88")
      (footprint "C0402_IPC High Density")
      (description "C0402, 100nF,  16V, X7R")
      (fields
        (field (name "MANUFACTURER") "MURATA")
        (field (name "MANUFACTURER PART NUMBER") "GRM155R71C104KA88D")
        (field (name "CAPACITANCE") "100nF")
      )
      (libsource (lib "CAPACITORS") (part "GRM155R71C104KA88"))
    )
    (comp (ref "C80")
      (value "GRM21BR61E475KA12")
      (footprint "CAPC2012[0805]")
      (description "C0805, 4.7uF 10%, 25V, X5R")
      (fields
        (field (name "MANUFACTURER") "Murata Electronics North America")
        (field (name "TOLERANCE") "±10%")
        (field (name "CAPACITANCE") "4.7µF")
      )
      (libsource (lib "CAPACITORS") (part "GRM21BR61E475KA12"))
    )
    (comp (ref "C81")
      (value "GRM155R71C104KA88")
      (footprint "C0402_IPC High Density")
      (description "C0402, 100nF,  16V, X7R")
      (fields
        (field (name "MANUFACTURER") "MURATA")
        (field (name "MANUFACTURER PART NUMBER") "GRM155R71C104KA88D")
        (field (name "CAPACITANCE") "100nF")
      )
      (libsource (lib "CAPACITORS") (part "GRM155R71C104KA88"))
    )
    (comp (ref "C82")
      (value "GRM155R71C104KA88")
      (footprint "C0402_IPC High Density")
      (description "C0402, 100nF,  16V, X7R")
      (fields
        (field (name "MANUFACTURER") "MURATA")
        (field (name "MANUFACTURER PART NUMBER") "GRM155R71C104KA88D")
        (field (name "CAPACITANCE") "100nF")
      )
      (libsource (lib "CAPACITORS") (part "GRM155R71C104KA88"))
    )
    (comp (ref "C83")
      (value "GRM188R60J106ME47")
      (footprint "C0603")
      (description "C0603 10uF 6.3V X5R")
      (fields
        (field (name "MANUFACTURER") "Murata Electronics North America")
        (field (name "TOLERANCE") "±20%")
        (field (name "CAPACITANCE") "10µF")
      )
      (libsource (lib "CAPACITORS") (part "GRM188R60J106ME47"))
    )
    (comp (ref "C84")
      (value "GRM155R71C104KA88")
      (footprint "C0402_IPC High Density")
      (description "C0402, 100nF,  16V, X7R")
      (fields
        (field (name "MANUFACTURER") "MURATA")
        (field (name "MANUFACTURER PART NUMBER") "GRM155R71C104KA88D")
        (field (name "CAPACITANCE") "100nF")
      )
      (libsource (lib "CAPACITORS") (part "GRM155R71C104KA88"))
    )
    (comp (ref "C85")
      (value "GRM155R71C104KA88")
      (footprint "C0402_IPC High Density")
      (description "C0402, 100nF,  16V, X7R")
      (fields
        (field (name "MANUFACTURER") "MURATA")
        (field (name "MANUFACTURER PART NUMBER") "GRM155R71C104KA88D")
        (field (name "CAPACITANCE") "100nF")
      )
      (libsource (lib "CAPACITORS") (part "GRM155R71C104KA88"))
    )
    (comp (ref "C86")
      (value "GRM155R71C104KA88")
      (footprint "C0402_IPC High Density")
      (description "C0402, 100nF,  16V, X7R")
      (fields
        (field (name "MANUFACTURER") "MURATA")
        (field (name "MANUFACTURER PART NUMBER") "GRM155R71C104KA88D")
        (field (name "CAPACITANCE") "100nF")
      )
      (libsource (lib "CAPACITORS") (part "GRM155R71C104KA88"))
    )
    (comp (ref "C87")
      (value "GRM155R71C104KA88")
      (footprint "C0402_IPC High Density")
      (description "C0402, 100nF,  16V, X7R")
      (fields
        (field (name "MANUFACTURER") "MURATA")
        (field (name "MANUFACTURER PART NUMBER") "GRM155R71C104KA88D")
        (field (name "CAPACITANCE") "100nF")
      )
      (libsource (lib "CAPACITORS") (part "GRM155R71C104KA88"))
    )
    (comp (ref "C88")
      (value "GRM155R71C104KA88")
      (footprint "C0402_IPC High Density")
      (description "C0402, 100nF,  16V, X7R")
      (fields
        (field (name "MANUFACTURER") "MURATA")
        (field (name "MANUFACTURER PART NUMBER") "GRM155R71C104KA88D")
        (field (name "CAPACITANCE") "100nF")
      )
      (libsource (lib "CAPACITORS") (part "GRM155R71C104KA88"))
    )
    (comp (ref "C89")
      (value "GRM155R71C104KA88")
      (footprint "C0402_IPC High Density")
      (description "C0402, 100nF,  16V, X7R")
      (fields
        (field (name "MANUFACTURER") "MURATA")
        (field (name "MANUFACTURER PART NUMBER") "GRM155R71C104KA88D")
        (field (name "CAPACITANCE") "100nF")
      )
      (libsource (lib "CAPACITORS") (part "GRM155R71C104KA88"))
    )
    (comp (ref "C90")
      (value "GRM155R71C104KA88")
      (footprint "C0402_IPC High Density")
      (description "C0402, 100nF,  16V, X7R")
      (fields
        (field (name "MANUFACTURER") "MURATA")
        (field (name "MANUFACTURER PART NUMBER") "GRM155R71C104KA88D")
        (field (name "CAPACITANCE") "100nF")
      )
      (libsource (lib "CAPACITORS") (part "GRM155R71C104KA88"))
    )
    (comp (ref "C91")
      (value "GRM21BR61E475KA12")
      (footprint "CAPC2012[0805]")
      (description "C0805, 4.7uF 10%, 25V, X5R")
      (fields
        (field (name "MANUFACTURER") "Murata Electronics North America")
        (field (name "TOLERANCE") "±10%")
        (field (name "CAPACITANCE") "4.7µF")
        (field (name "VOLTAGE - RATED") "25V")
      )
      (libsource (lib "CAPACITORS") (part "GRM21BR61E475KA12"))
    )
    (comp (ref "C92")
      (value "GRM21BR61E475KA12")
      (footprint "CAPC2012[0805]")
      (description "C0805, 4.7uF 10%, 25V, X5R")
      (fields
        (field (name "MANUFACTURER") "Murata Electronics North America")
        (field (name "TOLERANCE") "±10%")
        (field (name "CAPACITANCE") "4.7µF")
        (field (name "VOLTAGE - RATED") "25V")
      )
      (libsource (lib "CAPACITORS") (part "GRM21BR61E475KA12"))
    )
    (comp (ref "C93")
      (value "GRM188R60J106ME47")
      (footprint "C0603")
      (description "C0603 10uF 6.3V X5R")
      (fields
        (field (name "MANUFACTURER") "Murata Electronics North America")
        (field (name "MANUFACTURER PART NUMBER") "GRM188R60J106ME47D")
        (field (name "CAPACITANCE") "10µF")
      )
      (libsource (lib "CAPACITORS") (part "GRM188R60J106ME47"))
    )
    (comp (ref "C94")
      (value "GRM155R71C104KA88")
      (footprint "C0402_IPC High Density")
      (description "C0402, 100nF,  16V, X7R")
      (fields
        (field (name "MANUFACTURER") "MURATA")
        (field (name "MANUFACTURER PART NUMBER") "GRM155R71C104KA88D")
        (field (name "CAPACITANCE") "100nF")
      )
      (libsource (lib "CAPACITORS") (part "GRM155R71C104KA88"))
    )
    (comp (ref "C95")
      (value "GRM188R60J106ME47")
      (footprint "C0603")
      (description "C0603 10uF 6.3V X5R")
      (fields
        (field (name "MANUFACTURER") "Murata Electronics North America")
        (field (name "MANUFACTURER PART NUMBER") "GRM188R60J106ME47D")
        (field (name "CAPACITANCE") "10µF")
      )
      (libsource (lib "CAPACITORS") (part "GRM188R60J106ME47"))
    )
    (comp (ref "C96")
      (value "GRM155R71C104KA88")
      (footprint "C0402_IPC High Density")
      (description "C0402, 100nF,  16V, X7R")
      (fields
        (field (name "MANUFACTURER") "MURATA")
        (field (name "MANUFACTURER PART NUMBER") "GRM155R71C104KA88D")
        (field (name "CAPACITANCE") "100nF")
      )
      (libsource (lib "CAPACITORS") (part "GRM155R71C104KA88"))
    )
    (comp (ref "C97")
      (value "GRM1555C1H680JZ01")
      (footprint "C0402_IPC High Density")
      (description "C0402, 68pF,  50V, C0G")
      (fields
        (field (name "MANUFACTURER PART NUMBER") "GRM1555C1H680JZ01D")
        (field (name "CAPACITANCE") "68pF")
        (field (name "TOLERANCE") "±5%")
      )
      (libsource (lib "PUMA-10S") (part "GRM1555C1H680JZ01"))
    )
    (comp (ref "C98")
      (value "GRM188R60J106ME47")
      (footprint "C0603")
      (description "C0603 10uF 6.3V X5R")
      (fields
        (field (name "MANUFACTURER") "Murata Electronics North America")
        (field (name "MANUFACTURER PART NUMBER") "GRM188R60J106ME47D")
        (field (name "CAPACITANCE") "10µF")
      )
      (libsource (lib "CAPACITORS") (part "GRM188R60J106ME47"))
    )
    (comp (ref "C99")
      (value "GRM188R60J106ME47")
      (footprint "C0603")
      (description "C0603 10uF 6.3V X5R")
      (fields
        (field (name "MANUFACTURER") "Murata Electronics North America")
        (field (name "MANUFACTURER PART NUMBER") "GRM188R60J106ME47D")
        (field (name "CAPACITANCE") "10µF")
      )
      (libsource (lib "CAPACITORS") (part "GRM188R60J106ME47"))
    )
    (comp (ref "C100")
      (value "GRM188R60J106ME47")
      (footprint "C0603")
      (description "C0603 10uF 6.3V X5R")
      (fields
        (field (name "MANUFACTURER") "Murata Electronics North America")
        (field (name "MANUFACTURER PART NUMBER") "GRM188R60J106ME47D")
        (field (name "CAPACITANCE") "10µF")
      )
      (libsource (lib "CAPACITORS") (part "GRM188R60J106ME47"))
    )
    (comp (ref "C101")
      (value "GRM1555C1H680JZ01")
      (footprint "C0402_IPC High Density")
      (description "C0402, 68pF,  50V, C0G")
      (fields
        (field (name "MANUFACTURER PART NUMBER") "GRM1555C1H680JZ01D")
        (field (name "CAPACITANCE") "68pF")
        (field (name "TOLERANCE") "±5%")
      )
      (libsource (lib "PUMA-10S") (part "GRM1555C1H680JZ01"))
    )
    (comp (ref "C102")
      (value "GRM188R60J106ME47")
      (footprint "C0603")
      (description "C0603 10uF 6.3V X5R")
      (fields
        (field (name "MANUFACTURER") "Murata Electronics North America")
        (field (name "MANUFACTURER PART NUMBER") "GRM188R60J106ME47D")
        (field (name "CAPACITANCE") "10µF")
      )
      (libsource (lib "CAPACITORS") (part "GRM188R60J106ME47"))
    )
    (comp (ref "C103")
      (value "GRM188R60J106ME47")
      (footprint "C0603")
      (description "C0603 10uF 6.3V X5R")
      (fields
        (field (name "MANUFACTURER") "Murata Electronics North America")
        (field (name "MANUFACTURER PART NUMBER") "GRM188R60J106ME47D")
        (field (name "CAPACITANCE") "10µF")
      )
      (libsource (lib "CAPACITORS") (part "GRM188R60J106ME47"))
    )
    (comp (ref "C104")
      (value "GRM155R71C104KA88")
      (footprint "C0402_IPC High Density")
      (description "C0402, 100nF,  16V, X7R")
      (fields
        (field (name "MANUFACTURER") "MURATA")
        (field (name "MANUFACTURER PART NUMBER") "GRM155R71C104KA88D")
        (field (name "CAPACITANCE") "100nF")
      )
      (libsource (lib "CAPACITORS") (part "GRM155R71C104KA88"))
    )
    (comp (ref "C105")
      (value "GRM188R60J106ME47")
      (footprint "C0603")
      (description "C0603 10uF 6.3V X5R")
      (fields
        (field (name "MANUFACTURER") "Murata Electronics North America")
        (field (name "MANUFACTURER PART NUMBER") "GRM188R60J106ME47D")
        (field (name "CAPACITANCE") "10µF")
      )
      (libsource (lib "CAPACITORS") (part "GRM188R60J106ME47"))
    )
    (comp (ref "C106")
      (value "GRM188R60J106ME47")
      (footprint "C0603")
      (description "C0603 10uF 6.3V X5R")
      (fields
        (field (name "MANUFACTURER") "Murata Electronics North America")
        (field (name "MANUFACTURER PART NUMBER") "GRM188R60J106ME47D")
        (field (name "CAPACITANCE") "10µF")
      )
      (libsource (lib "CAPACITORS") (part "GRM188R60J106ME47"))
    )
    (comp (ref "C107")
      (value "GRM188R60J106ME47")
      (footprint "C0603")
      (description "C0603 10uF 6.3V X5R")
      (fields
        (field (name "MANUFACTURER") "Murata Electronics North America")
        (field (name "MANUFACTURER PART NUMBER") "GRM188R60J106ME47D")
        (field (name "CAPACITANCE") "10µF")
      )
      (libsource (lib "CAPACITORS") (part "GRM188R60J106ME47"))
    )
    (comp (ref "C108")
      (value "GRM188R60J106ME47")
      (footprint "C0603")
      (description "C0603 10uF 6.3V X5R")
      (fields
        (field (name "MANUFACTURER") "Murata Electronics North America")
        (field (name "MANUFACTURER PART NUMBER") "GRM188R60J106ME47D")
        (field (name "CAPACITANCE") "10µF")
      )
      (libsource (lib "CAPACITORS") (part "GRM188R60J106ME47"))
    )
    (comp (ref "C109")
      (value "GRM188R60J106ME47")
      (footprint "C0603")
      (description "C0603 10uF 6.3V X5R")
      (fields
        (field (name "MANUFACTURER") "Murata Electronics North America")
        (field (name "MANUFACTURER PART NUMBER") "GRM188R60J106ME47D")
        (field (name "CAPACITANCE") "10µF")
      )
      (libsource (lib "CAPACITORS") (part "GRM188R60J106ME47"))
    )
    (comp (ref "C110")
      (value "GRM155R71C104KA88")
      (footprint "C0402_IPC High Density")
      (description "C0402, 100nF,  16V, X7R")
      (fields
        (field (name "MANUFACTURER") "MURATA")
        (field (name "MANUFACTURER PART NUMBER") "GRM155R71C104KA88D")
        (field (name "CAPACITANCE") "100nF")
      )
      (libsource (lib "CAPACITORS") (part "GRM155R71C104KA88"))
    )
    (comp (ref "C111")
      (value "GRM188R60J106ME47")
      (footprint "C0603")
      (description "C0603 10uF 6.3V X5R")
      (fields
        (field (name "MANUFACTURER") "Murata Electronics North America")
        (field (name "MANUFACTURER PART NUMBER") "GRM188R60J106ME47D")
        (field (name "CAPACITANCE") "10µF")
      )
      (libsource (lib "CAPACITORS") (part "GRM188R60J106ME47"))
    )
    (comp (ref "C112")
      (value "GRM188R60J106ME47")
      (footprint "C0603")
      (description "C0603 10uF 6.3V X5R")
      (fields
        (field (name "MANUFACTURER") "Murata Electronics North America")
        (field (name "MANUFACTURER PART NUMBER") "GRM188R60J106ME47D")
        (field (name "CAPACITANCE") "10µF")
      )
      (libsource (lib "CAPACITORS") (part "GRM188R60J106ME47"))
    )
    (comp (ref "C115")
      (value "GRM188R60J106ME47")
      (footprint "C0603")
      (description "C0603 10uF 6.3V X5R")
      (fields
        (field (name "MANUFACTURER") "Murata Electronics North America")
        (field (name "MANUFACTURER PART NUMBER") "GRM188R60J106ME47D")
        (field (name "CAPACITANCE") "10µF")
      )
      (libsource (lib "CAPACITORS") (part "GRM188R60J106ME47"))
    )
    (comp (ref "C117")
      (value "GRM188R60J106ME47")
      (footprint "C0603")
      (description "C0603 10uF 6.3V X5R")
      (fields
        (field (name "MANUFACTURER") "Murata Electronics North America")
        (field (name "MANUFACTURER PART NUMBER") "GRM188R60J106ME47D")
        (field (name "CAPACITANCE") "10µF")
      )
      (libsource (lib "CAPACITORS") (part "GRM188R60J106ME47"))
    )
    (comp (ref "C118")
      (value "GRM188R60J106ME47")
      (footprint "C0603")
      (description "C0603 10uF 6.3V X5R")
      (fields
        (field (name "MANUFACTURER") "Murata Electronics North America")
        (field (name "MANUFACTURER PART NUMBER") "GRM188R60J106ME47D")
        (field (name "CAPACITANCE") "10µF")
      )
      (libsource (lib "CAPACITORS") (part "GRM188R60J106ME47"))
    )
    (comp (ref "C120")
      (value "GRM155R71C104KA88")
      (footprint "C0402_IPC High Density")
      (description "C0402, 100nF,  16V, X7R")
      (fields
        (field (name "MANUFACTURER") "MURATA")
        (field (name "MANUFACTURER PART NUMBER") "GRM155R71C104KA88D")
        (field (name "CAPACITANCE") "100nF")
      )
      (libsource (lib "CAPACITORS") (part "GRM155R71C104KA88"))
    )
    (comp (ref "C121")
      (value "GRM155R71C104KA88")
      (footprint "C0402_IPC High Density")
      (description "C0402, 100nF,  16V, X7R")
      (fields
        (field (name "MANUFACTURER") "MURATA")
        (field (name "MANUFACTURER PART NUMBER") "GRM155R71C104KA88D")
        (field (name "CAPACITANCE") "100nF")
      )
      (libsource (lib "CAPACITORS") (part "GRM155R71C104KA88"))
    )
    (comp (ref "C122")
      (value "GRM188R60J106ME47")
      (footprint "C0603")
      (description "C0603 10uF 6.3V X5R")
      (fields
        (field (name "MANUFACTURER") "Murata Electronics North America")
        (field (name "MANUFACTURER PART NUMBER") "GRM188R60J106ME47D")
        (field (name "CAPACITANCE") "10µF")
      )
      (libsource (lib "CAPACITORS") (part "GRM188R60J106ME47"))
    )
    (comp (ref "C123")
      (value "GRM21BR61E475KA12")
      (footprint "CAPC2012[0805]")
      (description "C0805, 4.7uF 10%, 25V, X5R")
      (fields
        (field (name "MANUFACTURER") "Murata Electronics North America")
        (field (name "TOLERANCE") "±10%")
        (field (name "CAPACITANCE") "4.7µF")
        (field (name "VOLTAGE - RATED") "25V")
      )
      (libsource (lib "CAPACITORS") (part "GRM21BR61E475KA12"))
    )
    (comp (ref "C124")
      (value "GRM21BR61E475KA12")
      (footprint "CAPC2012[0805]")
      (description "C0805, 4.7uF 10%, 25V, X5R")
      (fields
        (field (name "MANUFACTURER") "Murata Electronics North America")
        (field (name "TOLERANCE") "±10%")
        (field (name "CAPACITANCE") "4.7µF")
        (field (name "VOLTAGE - RATED") "25V")
      )
      (libsource (lib "CAPACITORS") (part "GRM21BR61E475KA12"))
    )
    (comp (ref "C125")
      (value "GRM21BR61E475KA12")
      (footprint "CAPC2012[0805]")
      (description "C0805, 4.7uF 10%, 25V, X5R")
      (fields
        (field (name "MANUFACTURER") "Murata Electronics North America")
        (field (name "TOLERANCE") "±10%")
        (field (name "CAPACITANCE") "4.7µF")
        (field (name "VOLTAGE - RATED") "25V")
      )
      (libsource (lib "CAPACITORS") (part "GRM21BR61E475KA12"))
    )
    (comp (ref "C126")
      (value "GRM155R71C104KA88")
      (footprint "C0402_IPC High Density")
      (description "C0402, 100nF,  16V, X7R")
      (fields
        (field (name "MANUFACTURER") "MURATA")
        (field (name "MANUFACTURER PART NUMBER") "GRM155R71C104KA88D")
        (field (name "CAPACITANCE") "100nF")
      )
      (libsource (lib "CAPACITORS") (part "GRM155R71C104KA88"))
    )
    (comp (ref "C127")
      (value "GRM155R71C104KA88")
      (footprint "C0402_IPC High Density")
      (description "C0402, 100nF,  16V, X7R")
      (fields
        (field (name "MANUFACTURER") "MURATA")
        (field (name "MANUFACTURER PART NUMBER") "GRM155R71C104KA88D")
        (field (name "CAPACITANCE") "100nF")
      )
      (libsource (lib "CAPACITORS") (part "GRM155R71C104KA88"))
    )
    (comp (ref "C128")
      (value "GRM188R60J106ME47")
      (footprint "C0603")
      (description "C0603 10uF 6.3V X5R")
      (fields
        (field (name "MANUFACTURER") "Murata Electronics North America")
        (field (name "TOLERANCE") "±20%")
        (field (name "CAPACITANCE") "10µF")
      )
      (libsource (lib "CAPACITORS") (part "GRM188R60J106ME47"))
    )
    (comp (ref "C129")
      (value "GRM188R60J106ME47")
      (footprint "C0603")
      (description "C0603 10uF 6.3V X5R")
      (fields
        (field (name "MANUFACTURER") "Murata Electronics North America")
        (field (name "TOLERANCE") "±20%")
        (field (name "CAPACITANCE") "10µF")
      )
      (libsource (lib "CAPACITORS") (part "GRM188R60J106ME47"))
    )
    (comp (ref "C130")
      (value "GRM188R60J106ME47")
      (footprint "C0603")
      (description "C0603 10uF 6.3V X5R")
      (fields
        (field (name "MANUFACTURER") "Murata Electronics North America")
        (field (name "TOLERANCE") "±20%")
        (field (name "CAPACITANCE") "10µF")
      )
      (libsource (lib "CAPACITORS") (part "GRM188R60J106ME47"))
    )
    (comp (ref "C131")
      (value "GRM188R60J106ME47")
      (footprint "C0603")
      (description "C0603 10uF 6.3V X5R")
      (fields
        (field (name "MANUFACTURER") "Murata Electronics North America")
        (field (name "TOLERANCE") "±20%")
        (field (name "CAPACITANCE") "10µF")
      )
      (libsource (lib "CAPACITORS") (part "GRM188R60J106ME47"))
    )
    (comp (ref "C132")
      (value "GRM188R60J106ME47")
      (footprint "C0603")
      (description "C0603 10uF 6.3V X5R")
      (fields
        (field (name "MANUFACTURER") "Murata Electronics North America")
        (field (name "TOLERANCE") "±20%")
        (field (name "CAPACITANCE") "10µF")
      )
      (libsource (lib "CAPACITORS") (part "GRM188R60J106ME47"))
    )
    (comp (ref "C133")
      (value "GRM188R60J106ME47")
      (footprint "C0603")
      (description "C0603 10uF 6.3V X5R")
      (fields
        (field (name "MANUFACTURER") "Murata Electronics North America")
        (field (name "MANUFACTURER PART NUMBER") "GRM188R60J106ME47D")
        (field (name "CAPACITANCE") "10µF")
      )
      (libsource (lib "CAPACITORS") (part "GRM188R60J106ME47"))
    )
    (comp (ref "C134")
      (value "GRM188R60J106ME47")
      (footprint "C0603")
      (description "C0603 10uF 6.3V X5R")
      (fields
        (field (name "MANUFACTURER") "Murata Electronics North America")
        (field (name "MANUFACTURER PART NUMBER") "GRM188R60J106ME47D")
        (field (name "CAPACITANCE") "10µF")
      )
      (libsource (lib "CAPACITORS") (part "GRM188R60J106ME47"))
    )
    (comp (ref "C136")
      (value "GRM188R60J106ME47")
      (footprint "C0603")
      (description "C0603 10uF 6.3V X5R")
      (fields
        (field (name "MANUFACTURER") "Murata Electronics North America")
        (field (name "MANUFACTURER PART NUMBER") "GRM188R60J106ME47D")
        (field (name "CAPACITANCE") "10µF")
      )
      (libsource (lib "CAPACITORS") (part "GRM188R60J106ME47"))
    )
    (comp (ref "C137")
      (value "GRM1555C1H680JZ01")
      (footprint "C0402_IPC High Density")
      (description "C0402, 68pF,  50V, C0G")
      (fields
        (field (name "MANUFACTURER PART NUMBER") "GRM1555C1H680JZ01D")
        (field (name "CAPACITANCE") "68pF")
        (field (name "TOLERANCE") "±5%")
      )
      (libsource (lib "PUMA-10S") (part "GRM1555C1H680JZ01"))
    )
    (comp (ref "C138")
      (value "GRM1555C1H150")
      (footprint "C0402_IPC High Density")
      (description "C0402, 15pF 50V, NP0")
      (fields
        (field (name "MANUFACTURER PART NUMBER") "GRM1555C1H150JZ01D")
        (field (name "MANUFACTURER") "Murata Electronics North America")
        (field (name "CAPACITANCE") "15pF")
      )
      (libsource (lib "PUMA-10S") (part "GRM1555C1H150"))
    )
    (comp (ref "C139")
      (value "GRM155R71E682KA01")
      (footprint "C0402_IPC High Density")
      (description "C0402, 6.8nF 5%,  25V, X7R")
      (fields (field (name "CAPACITANCE") "6.8nF"))
      (libsource (lib "CAPACITORS") (part "GRM155R71E682KA01"))
    )
    (comp (ref "C140")
      (value "GRM21BR61E475KA12")
      (footprint "CAPC2012[0805]")
      (description "C0805, 4.7uF 10%, 25V, X5R")
      (fields
        (field (name "MANUFACTURER") "Murata Electronics North America")
        (field (name "TOLERANCE") "±10%")
        (field (name "CAPACITANCE") "4.7µF")
        (field (name "VOLTAGE - RATED") "25V")
      )
      (libsource (lib "CAPACITORS") (part "GRM21BR61E475KA12"))
    )
    (comp (ref "C141")
      (value "GRM188R60J106ME47")
      (footprint "C0603")
      (description "C0603 10uF 6.3V X5R")
      (fields
        (field (name "MANUFACTURER") "Murata Electronics North America")
        (field (name "TOLERANCE") "±20%")
        (field (name "CAPACITANCE") "10µF")
      )
      (libsource (lib "CAPACITORS") (part "GRM188R60J106ME47"))
    )
    (comp (ref "C142")
      (value "GRM155R71C104KA88")
      (footprint "C0402_IPC High Density")
      (description "C0402, 100nF,  16V, X7R")
      (fields
        (field (name "MANUFACTURER") "MURATA")
        (field (name "MANUFACTURER PART NUMBER") "GRM155R71C104KA88D")
        (field (name "CAPACITANCE") "100nF")
      )
      (libsource (lib "CAPACITORS") (part "GRM155R71C104KA88"))
    )
    (comp (ref "C143")
      (value "GRM155R71C104KA88")
      (footprint "C0402_IPC High Density")
      (description "C0402, 100nF,  16V, X7R")
      (fields
        (field (name "MANUFACTURER") "MURATA")
        (field (name "MANUFACTURER PART NUMBER") "GRM155R71C104KA88D")
        (field (name "CAPACITANCE") "100nF")
      )
      (libsource (lib "CAPACITORS") (part "GRM155R71C104KA88"))
    )
    (comp (ref "DD1")
      (value "Allwinner A10S")
      (footprint "TFBGA336")
      (description "CPU ARM Cortex-A8 1G")
      (libsource (lib "PUMA-10S_V0") (part "A10S-TFBGA336"))
    )
    (comp (ref "DD2")
      (value "RTL8201CP")
      (footprint "LQFP48")
      (description "Single-Port 10/100M Fast Ethernet PHYceiver")
      (libsource (lib "LIB_A10S") (part "RTL8201CP"))
    )
    (comp (ref "DD3")
      (value "H5TQ2G83CFR-H9C")
      (footprint "FBGA78")
      (description "2Gb DDR3 SDRAM")
      (libsource (lib "LIB_A10S") (part "H5TQ2G83CFR-H9C"))
    )
    (comp (ref "DD4")
      (value "SY6280AAC")
      (footprint "SOT23-5")
      (description "Low Loss Power Distribution Switch")
      (libsource (lib "LIB_A10S") (part "SY6280AAC"))
    )
    (comp (ref "DD5")
      (value "NCP603SN150T1G")
      (footprint "SOT23-5")
      (description "IC 300mA 1.5V CMOS LDO REG")
      (fields
        (field (name "MANUFACTURER") "ON Semiconductor")
        (field (name "MANUFACTURER PART NUMBER") "NCP603SN180T1G")
      )
      (libsource (lib "DIGITAL and ANALIG ICs") (part "NCP603SN150T1G"))
    )
    (comp (ref "DD6")
      (value "H5TQ2G83CFR-H9C")
      (footprint "FBGA78")
      (description "2Gb DDR3 SDRAM")
      (libsource (lib "LIB_A10S") (part "H5TQ2G83CFR-H9C"))
    )
    (comp (ref "DD7")
      (value "PCF8563T/5")
      (footprint "SO-8_L")
      (description "Real-Time Clock (RTC) and calendar")
      (libsource (lib "PUMA-10S_V0") (part "PCF8563T/5"))
    )
    (comp (ref "DD8")
      (value "SY8008C")
      (footprint "SOT23-5")
      (description "Synchronous Step Down Regulator 1.5MHz, 1.2A")
      (libsource (lib "DIGITAL and ANALIG ICs") (part "SY8008C"))
    )
    (comp (ref "DD9")
      (value "SY8008C")
      (footprint "SOT23-5")
      (description "Synchronous Step Down Regulator 1.5MHz, 1.2A")
      (libsource (lib "DIGITAL and ANALIG ICs") (part "SY8008C"))
    )
    (comp (ref "DD10")
      (value "MAX809SD or IMP809SEUR")
      (footprint "SOT-23")
      (description "IC SUPERVISOR, RESET THRESHOLD 2.93V")
      (libsource (lib "DIGITAL and ANALIG ICs") (part "MAX809SD"))
    )
    (comp (ref "DD11")
      (value "NCP3170BDR2G")
      (footprint "SO-8_N")
      (description "IC DC/DC Switching Converters 3A 1MHz")
      (libsource (lib "DIGITAL and ANALIG ICs") (part "NCP3170BDR2G"))
    )
    (comp (ref "L1")
      (value "BLM15PX331SN1")
      (footprint "L 0402")
      (description "FILTER BLM15 (0402, 1.2A)")
      (libsource (lib "INDUCTORS") (part "BLM15PX331SN1"))
    )
    (comp (ref "L2")
      (value "BLM15PX331SN1")
      (footprint "L 0402")
      (description "FILTER BLM15 (0402, 1.2A)")
      (libsource (lib "INDUCTORS") (part "BLM15PX331SN1"))
    )
    (comp (ref "L5")
      (value "CDRH2D18/HP-3R3N")
      (footprint "CDRH2D18B/HPNP-3R3N")
      (description "INDUCTOR 3.3UH 1.3A")
      (fields
        (field (name "MANUFACTURER") "Sumida")
        (field (name "MANUFACTURER PART NUMBER") "CDRH2D18/HP-3R3NC")
        (field (name "INDUCTANCE") "3.3 uH")
        (field (name "MAXIMUM DC CURRENT") "1.45 A")
      )
      (libsource (lib "LIB_A10S") (part "CDRH2D18/HP-3R3N"))
    )
    (comp (ref "L7")
      (value "CDRH2D18/HP-3R3N")
      (footprint "CDRH2D18B/HPNP-3R3N")
      (description "INDUCTOR 3.3UH 1.3A")
      (fields
        (field (name "MANUFACTURER") "Sumida")
        (field (name "MANUFACTURER PART NUMBER") "CDRH2D18/HP-3R3NC")
        (field (name "INDUCTANCE") "3.3 uH")
        (field (name "MAXIMUM DC CURRENT") "1.45 A")
      )
      (libsource (lib "LIB_A10S") (part "CDRH2D18/HP-3R3N"))
    )
    (comp (ref "L11")
      (value "BLM15PX331SN1")
      (footprint "L 0402")
      (description "FILTER BLM15 (0402, 1.2A)")
      (libsource (lib "INDUCTORS") (part "BLM15PX331SN1"))
    )
    (comp (ref "L12")
      (value "SDR0604-2R2ML")
      (footprint "SDR0403")
      (description "INDUCTOR 2.2 UH 2.8A")
      (fields (field (name "MANUFACTURER") "BOURNS"))
      (libsource (lib "INDUCTORS") (part "SDR0604-2R2ML"))
    )
    (comp (ref "LED1")
      (value "FYLS-0603PGC")
      (footprint "LED0603")
      (description "LED, Pure Green, 0603")
      (libsource (lib "LED") (part "FYLS-0603PGC"))
    )
    (comp (ref "LED2")
      (value "FYLS-0603PGC")
      (footprint "LED0603")
      (description "LED, Pure Green, 0603")
      (libsource (lib "LED") (part "FYLS-0603PGC"))
    )
    (comp (ref "R1")
      (value "ERJ-2RKF2400X")
      (footprint "RESC1005[0402]")
      (description "R0402, 240R 1%")
      (fields
        (field (name "MANUFACTURER") "Panasonic Electronic Components")
        (field (name "TOLERANCE") "±1%")
        (field (name "RESISTANCE (OHMS)") "240")
      )
      (libsource (lib "PUMA-10S") (part "ERJ-2RKF2400X"))
    )
    (comp (ref "R2")
      (value "ERJ-2RKF2400X")
      (footprint "RESC1005[0402]")
      (description "R0402, 240R 1%")
      (fields
        (field (name "MANUFACTURER") "Panasonic Electronic Components")
        (field (name "TOLERANCE") "±1%")
        (field (name "RESISTANCE (OHMS)") "240")
      )
      (libsource (lib "PUMA-10S") (part "ERJ-2RKF2400X"))
    )
    (comp (ref "R3")
      (value "ERJ-2RKF4751X")
      (footprint "RESC1005[0402]")
      (description "R0402, 4.75k 1%")
      (fields
        (field (name "TOLERANCE") "±1%")
        (field (name "MANUFACTURER") "Panasonic Electronic Components")
        (field (name "RESISTANCE (OHMS)") "4.75k")
      )
      (libsource (lib "PUMA-10S") (part "ERJ-2RKF4751X"))
    )
    (comp (ref "R4")
      (value "ERJ-2RKF4751X")
      (footprint "RESC1005[0402]")
      (description "R0402, 4.75k 1%")
      (fields
        (field (name "TOLERANCE") "±1%")
        (field (name "MANUFACTURER") "Panasonic Electronic Components")
        (field (name "RESISTANCE (OHMS)") "4.75k")
      )
      (libsource (lib "PUMA-10S") (part "ERJ-2RKF4751X"))
    )
    (comp (ref "R5")
      (value "ERJ-2RKF4751X")
      (footprint "RESC1005[0402]")
      (description "R0402, 4.75k 1%")
      (fields
        (field (name "TOLERANCE") "±1%")
        (field (name "MANUFACTURER") "Panasonic Electronic Components")
        (field (name "RESISTANCE (OHMS)") "4.75k")
      )
      (libsource (lib "PUMA-10S") (part "ERJ-2RKF4751X"))
    )
    (comp (ref "R6")
      (value "ERJ-2RKF4751X")
      (footprint "RESC1005[0402]")
      (description "R0402, 4.75k 1%")
      (fields
        (field (name "TOLERANCE") "±1%")
        (field (name "MANUFACTURER") "Panasonic Electronic Components")
        (field (name "RESISTANCE (OHMS)") "4.75k")
      )
      (libsource (lib "PUMA-10S") (part "ERJ-2RKF4751X"))
    )
    (comp (ref "R7")
      (value "ERJ-2RKF22R0X")
      (footprint "RESC1005[0402]")
      (description "R0402, 22R 1%")
      (fields
        (field (name "MANUFACTURER PART NUMBER") "ERJ2RKF33R2X")
        (field (name "MANUFACTURER") "PANASONIC")
        (field (name "RESISTANCE") "22R")
      )
      (libsource (lib "RESISTOR") (part "ERJ-2RKF22R0X"))
    )
    (comp (ref "R8")
      (value "ERJ-2RKF4751X")
      (footprint "RESC1005[0402]")
      (description "R0402, 4.75k 1%")
      (fields
        (field (name "TOLERANCE") "±1%")
        (field (name "MANUFACTURER") "Panasonic Electronic Components")
        (field (name "RESISTANCE (OHMS)") "4.75k")
      )
      (libsource (lib "PUMA-10S") (part "ERJ-2RKF4751X"))
    )
    (comp (ref "R9")
      (value "ERJ-2RKF22R0X")
      (footprint "RESC1005[0402]")
      (description "R0402, 22R 1%")
      (fields
        (field (name "MANUFACTURER PART NUMBER") "ERJ2RKF33R2X")
        (field (name "MANUFACTURER") "PANASONIC")
        (field (name "RESISTANCE") "22R")
      )
      (libsource (lib "RESISTOR") (part "ERJ-2RKF22R0X"))
    )
    (comp (ref "R10")
      (value "ERJ-2RKF2001X")
      (footprint "RESC1005[0402]")
      (description "R0402, 2k 1%")
      (fields
        (field (name "TOLERANCE") "±1%")
        (field (name "MANUFACTURER") "Panasonic Electronic Components")
        (field (name "RESISTANCE (OHMS)") "2k")
      )
      (libsource (lib "RESISTOR") (part "ERJ-2RKF2001X"))
    )
    (comp (ref "R11")
      (value "ERJ-2RKF4751X")
      (footprint "RESC1005[0402]")
      (description "R0402, 4.75k 1%")
      (fields
        (field (name "TOLERANCE") "±1%")
        (field (name "MANUFACTURER") "Panasonic Electronic Components")
        (field (name "RESISTANCE (OHMS)") "4.75k")
      )
      (libsource (lib "PUMA-10S") (part "ERJ-2RKF4751X"))
    )
    (comp (ref "R12")
      (value "ERJ-2RKF4751X")
      (footprint "RESC1005[0402]")
      (description "R0402, 4.75k 1%")
      (fields
        (field (name "TOLERANCE") "±1%")
        (field (name "MANUFACTURER") "Panasonic Electronic Components")
        (field (name "RESISTANCE (OHMS)") "4.75k")
      )
      (libsource (lib "PUMA-10S") (part "ERJ-2RKF4751X"))
    )
    (comp (ref "R13")
      (value "CR0402-J/-000GLF not_mount")
      (footprint "RESC1005[0402]")
      (description "R0402, 0R not_mount")
      (fields (field (name "0R NOT_MOUNT") "R0402, 0R not_mount"))
      (libsource (lib "LIB_A10S") (part "CR0402-J/-000GLF not_mount"))
    )
    (comp (ref "R14")
      (value "ERJ-2RKF1002X")
      (footprint "RESC1005[0402]")
      (description "R0402, 10k 1%")
      (fields
        (field (name "TOLERANCE") "1 %")
        (field (name "MANUFACTURER") "Panasonic")
        (field (name "RESISTANCE") "10k")
      )
      (libsource (lib "PUMA-10S") (part "ERJ-2RKF1002X"))
    )
    (comp (ref "R15")
      (value "ERJ-2RKF2400X")
      (footprint "RESC1005[0402]")
      (description "R0402, 240R 1%")
      (fields
        (field (name "MANUFACTURER") "Panasonic Electronic Components")
        (field (name "MANUFACTURER PART NUMBER") "ERJ-2RKF2260X")
        (field (name "RESISTANCE (OHMS)") "240")
      )
      (libsource (lib "PUMA-10S") (part "ERJ-2RKF2400X"))
    )
    (comp (ref "R16")
      (value "ERJ-2RKF2400X")
      (footprint "RESC1005[0402]")
      (description "R0402, 240R 1%")
      (fields
        (field (name "MANUFACTURER") "Panasonic Electronic Components")
        (field (name "MANUFACTURER PART NUMBER") "ERJ-2RKF2260X")
        (field (name "RESISTANCE (OHMS)") "240")
      )
      (libsource (lib "PUMA-10S") (part "ERJ-2RKF2400X"))
    )
    (comp (ref "R17")
      (value "ERJ-2RKF2400X")
      (footprint "RESC1005[0402]")
      (description "R0402, 240R 1%")
      (fields
        (field (name "MANUFACTURER") "Panasonic Electronic Components")
        (field (name "MANUFACTURER PART NUMBER") "ERJ-2RKF2260X")
        (field (name "RESISTANCE (OHMS)") "240")
      )
      (libsource (lib "PUMA-10S") (part "ERJ-2RKF2400X"))
    )
    (comp (ref "R18")
      (value "ERJ-2RKF2400X")
      (footprint "RESC1005[0402]")
      (description "R0402, 240R 1%")
      (fields
        (field (name "MANUFACTURER") "Panasonic Electronic Components")
        (field (name "MANUFACTURER PART NUMBER") "ERJ-2RKF2260X")
        (field (name "RESISTANCE (OHMS)") "240")
      )
      (libsource (lib "PUMA-10S") (part "ERJ-2RKF2400X"))
    )
    (comp (ref "R19")
      (value "ERJ-2RKF2400X")
      (footprint "RESC1005[0402]")
      (description "R0402, 240R 1%")
      (fields
        (field (name "MANUFACTURER") "Panasonic Electronic Components")
        (field (name "MANUFACTURER PART NUMBER") "ERJ-2RKF2260X")
        (field (name "RESISTANCE (OHMS)") "240")
      )
      (libsource (lib "PUMA-10S") (part "ERJ-2RKF2400X"))
    )
    (comp (ref "R20")
      (value "ERJ-2RKF49R9X")
      (footprint "RESC1005[0402]")
      (description "R0402, 49.9R 1%")
      (fields
        (field (name "MANUFACTURER") "Panasonic")
        (field (name "TOLERANCE") "1 %")
        (field (name "RESISTANCE") "49.9")
      )
      (libsource (lib "RESISTOR") (part "ERJ-2RKF49R9X"))
    )
    (comp (ref "R21")
      (value "ERJ-2RKF49R9X")
      (footprint "RESC1005[0402]")
      (description "R0402, 49.9R 1%")
      (fields
        (field (name "MANUFACTURER") "Panasonic")
        (field (name "TOLERANCE") "1 %")
        (field (name "RESISTANCE") "49.9")
      )
      (libsource (lib "RESISTOR") (part "ERJ-2RKF49R9X"))
    )
    (comp (ref "R22")
      (value "ERJ-2RKF49R9X")
      (footprint "RESC1005[0402]")
      (description "R0402, 49.9R 1%")
      (fields
        (field (name "MANUFACTURER") "Panasonic")
        (field (name "TOLERANCE") "1 %")
        (field (name "RESISTANCE") "49.9")
      )
      (libsource (lib "RESISTOR") (part "ERJ-2RKF49R9X"))
    )
    (comp (ref "R23")
      (value "ERJ-2RKF49R9X")
      (footprint "RESC1005[0402]")
      (description "R0402, 49.9R 1%")
      (fields
        (field (name "MANUFACTURER") "Panasonic")
        (field (name "TOLERANCE") "1 %")
        (field (name "RESISTANCE") "49.9")
      )
      (libsource (lib "RESISTOR") (part "ERJ-2RKF49R9X"))
    )
    (comp (ref "R24")
      (value "CR0402-J/-000GLF not_mount")
      (footprint "RESC1005[0402]")
      (description "R0402, 0R not_mount")
      (fields (field (name "0R NOT_MOUNT") "R0402, 0R not_mount"))
      (libsource (lib "LIB_A10S") (part "CR0402-J/-000GLF not_mount"))
    )
    (comp (ref "R25")
      (value "ERJ-2RKF4751X")
      (footprint "RESC1005[0402]")
      (description "R0402, 4.75k 1%")
      (fields
        (field (name "TOLERANCE") "±1%")
        (field (name "MANUFACTURER") "Panasonic Electronic Components")
        (field (name "RESISTANCE (OHMS)") "4.75k")
      )
      (libsource (lib "PUMA-10S") (part "ERJ-2RKF4751X"))
    )
    (comp (ref "R26")
      (value "ERJ-2RKF2400X")
      (footprint "RESC1005[0402]")
      (description "R0402, 240R 1%")
      (fields
        (field (name "MANUFACTURER") "Panasonic Electronic Components")
        (field (name "MANUFACTURER PART NUMBER") "ERJ-2RKF2260X")
        (field (name "RESISTANCE (OHMS)") "240")
      )
      (libsource (lib "PUMA-10S") (part "ERJ-2RKF2400X"))
    )
    (comp (ref "R27")
      (value "ERJ-2RKF2400X")
      (footprint "RESC1005[0402]")
      (description "R0402, 240R 1%")
      (fields
        (field (name "MANUFACTURER") "Panasonic Electronic Components")
        (field (name "MANUFACTURER PART NUMBER") "ERJ-2RKF2260X")
        (field (name "RESISTANCE (OHMS)") "240")
      )
      (libsource (lib "PUMA-10S") (part "ERJ-2RKF2400X"))
    )
    (comp (ref "R28")
      (value "ERJ-2RKF4751X")
      (footprint "RESC1005[0402]")
      (description "R0402, 4.75k 1%")
      (fields
        (field (name "TOLERANCE") "±1%")
        (field (name "MANUFACTURER") "Panasonic Electronic Components")
        (field (name "RESISTANCE (OHMS)") "4.75k")
      )
      (libsource (lib "PUMA-10S") (part "ERJ-2RKF4751X"))
    )
    (comp (ref "R29")
      (value "ERJ-2RKF2001X")
      (footprint "RESC1005[0402]")
      (description "R0402, 2k 1%")
      (fields
        (field (name "TOLERANCE") "±1%")
        (field (name "MANUFACTURER") "Panasonic Electronic Components")
        (field (name "RESISTANCE (OHMS)") "2k")
      )
      (libsource (lib "RESISTOR") (part "ERJ-2RKF2001X"))
    )
    (comp (ref "R30")
      (value "ERJ-2RKF2001X")
      (footprint "RESC1005[0402]")
      (description "R0402, 2k 1%")
      (fields
        (field (name "TOLERANCE") "±1%")
        (field (name "MANUFACTURER") "Panasonic Electronic Components")
        (field (name "RESISTANCE (OHMS)") "2k")
      )
      (libsource (lib "RESISTOR") (part "ERJ-2RKF2001X"))
    )
    (comp (ref "R31")
      (value "ERJ-2RKF4751X")
      (footprint "RESC1005[0402]")
      (description "R0402, 4.75k 1%")
      (fields
        (field (name "TOLERANCE") "±1%")
        (field (name "MANUFACTURER") "Panasonic Electronic Components")
        (field (name "RESISTANCE (OHMS)") "4.75k")
      )
      (libsource (lib "PUMA-10S") (part "ERJ-2RKF4751X"))
    )
    (comp (ref "R32")
      (value "ERJ-2RKF1002X")
      (footprint "RESC1005[0402]")
      (description "R0402, 10k 1%")
      (fields
        (field (name "TOLERANCE") "1 %")
        (field (name "MANUFACTURER") "Panasonic")
        (field (name "RESISTANCE") "10k")
      )
      (libsource (lib "PUMA-10S") (part "ERJ-2RKF1002X"))
    )
    (comp (ref "R33")
      (value "CR0402-J/-000GLF not_mount")
      (footprint "RESC1005[0402]")
      (description "R0402, 0R not_mount")
      (fields (field (name "0R NOT_MOUNT") "R0402, 0R not_mount"))
      (libsource (lib "LIB_A10S") (part "CR0402-J/-000GLF not_mount"))
    )
    (comp (ref "R34")
      (value "ERJ-2RKF1002X")
      (footprint "RESC1005[0402]")
      (description "R0402, 10k 1%")
      (fields
        (field (name "TOLERANCE") "1 %")
        (field (name "MANUFACTURER") "Panasonic")
        (field (name "RESISTANCE") "10k")
      )
      (libsource (lib "PUMA-10S") (part "ERJ-2RKF1002X"))
    )
    (comp (ref "R35")
      (value "ERJ-2RKF1002X")
      (footprint "RESC1005[0402]")
      (description "R0402, 10k 1%")
      (fields
        (field (name "MANUFACTURER") "Panasonic")
        (field (name "TOLERANCE") "1 %")
        (field (name "RESISTANCE") "10k")
      )
      (libsource (lib "PUMA-10S") (part "ERJ-2RKF1002X"))
    )
    (comp (ref "R36")
      (value "ERJ-2RKF1002X")
      (footprint "RESC1005[0402]")
      (description "R0402, 10k 1%")
      (fields
        (field (name "MANUFACTURER") "Panasonic")
        (field (name "TOLERANCE") "1 %")
        (field (name "RESISTANCE") "10k")
      )
      (libsource (lib "PUMA-10S") (part "ERJ-2RKF1002X"))
    )
    (comp (ref "R37")
      (value "ERJ-2RKF1002X")
      (footprint "RESC1005[0402]")
      (description "R0402, 10k 1%")
      (fields
        (field (name "MANUFACTURER") "Panasonic")
        (field (name "TOLERANCE") "1 %")
        (field (name "RESISTANCE") "10k")
      )
      (libsource (lib "PUMA-10S") (part "ERJ-2RKF1002X"))
    )
    (comp (ref "R38")
      (value "ERJ-2RKF1002X")
      (footprint "RESC1005[0402]")
      (description "R0402, 10k 1%")
      (fields
        (field (name "MANUFACTURER") "Panasonic")
        (field (name "TOLERANCE") "1 %")
        (field (name "RESISTANCE") "10k")
      )
      (libsource (lib "PUMA-10S") (part "ERJ-2RKF1002X"))
    )
    (comp (ref "R39")
      (value "ERJ-2RKF1002X")
      (footprint "RESC1005[0402]")
      (description "R0402, 10k 1%")
      (fields
        (field (name "MANUFACTURER") "Panasonic")
        (field (name "TOLERANCE") "1 %")
        (field (name "RESISTANCE") "10k")
      )
      (libsource (lib "PUMA-10S") (part "ERJ-2RKF1002X"))
    )
    (comp (ref "R40")
      (value "ERJ-2RKF1002X")
      (footprint "RESC1005[0402]")
      (description "R0402, 10k 1%")
      (fields
        (field (name "MANUFACTURER") "Panasonic")
        (field (name "TOLERANCE") "1 %")
        (field (name "RESISTANCE") "10k")
      )
      (libsource (lib "PUMA-10S") (part "ERJ-2RKF1002X"))
    )
    (comp (ref "R41")
      (value "ERJ-2RKF2400X")
      (footprint "RESC1005[0402]")
      (description "R0402, 240R 1%")
      (fields
        (field (name "MANUFACTURER") "Panasonic Electronic Components")
        (field (name "MANUFACTURER PART NUMBER") "ERJ-2RKF2260X")
        (field (name "RESISTANCE (OHMS)") "240")
      )
      (libsource (lib "PUMA-10S") (part "ERJ-2RKF2400X"))
    )
    (comp (ref "R42")
      (value "ERJ-2RKF2400X")
      (footprint "RESC1005[0402]")
      (description "R0402, 240R 1%")
      (fields
        (field (name "MANUFACTURER") "Panasonic Electronic Components")
        (field (name "MANUFACTURER PART NUMBER") "ERJ-2RKF2260X")
        (field (name "RESISTANCE (OHMS)") "240")
      )
      (libsource (lib "PUMA-10S") (part "ERJ-2RKF2400X"))
    )
    (comp (ref "R43")
      (value "ERJ-2RKF1002X")
      (footprint "RESC1005[0402]")
      (description "R0402, 10k 1%")
      (fields
        (field (name "TOLERANCE") "1 %")
        (field (name "MANUFACTURER") "Panasonic")
        (field (name "RESISTANCE") "10k")
      )
      (libsource (lib "PUMA-10S") (part "ERJ-2RKF1002X"))
    )
    (comp (ref "R44")
      (value "ERJ-2RKF1002X")
      (footprint "RESC1005[0402]")
      (description "R0402, 10k 1%")
      (fields
        (field (name "TOLERANCE") "1 %")
        (field (name "MANUFACTURER") "Panasonic")
        (field (name "RESISTANCE") "10k")
      )
      (libsource (lib "PUMA-10S") (part "ERJ-2RKF1002X"))
    )
    (comp (ref "R45")
      (value "ERJ-2RKF1002X")
      (footprint "RESC1005[0402]")
      (description "R0402, 10k 1%")
      (fields
        (field (name "MANUFACTURER") "Panasonic")
        (field (name "TOLERANCE") "1 %")
        (field (name "RESISTANCE") "10k")
      )
      (libsource (lib "PUMA-10S") (part "ERJ-2RKF1002X"))
    )
    (comp (ref "R46")
      (value "ERJ-2RKF4751X")
      (footprint "RESISTOR:RESC1005[0402]")
      (description "R0402, 4.75k 1%")
      (fields
        (field (name "MANUFACTURER") "Panasonic Electronic Components")
        (field (name "TOLERANCE") "±1%")
        (field (name "RESISTANCE (OHMS)") "4.75k")
      )
      (libsource (lib "RESISTOR") (part "ERJ-2RKF4751X"))
    )
    (comp (ref "R47")
      (value "ERJ-2RKF2400X")
      (footprint "RESC1005[0402]")
      (description "R0402, 240R 1%")
      (fields
        (field (name "MANUFACTURER") "Panasonic Electronic Components")
        (field (name "MANUFACTURER PART NUMBER") "ERJ-2RKF2260X")
        (field (name "RESISTANCE (OHMS)") "240")
      )
      (libsource (lib "PUMA-10S") (part "ERJ-2RKF2400X"))
    )
    (comp (ref "R48")
      (value "CR0402-J/-000GLF not_mount")
      (footprint "RESC1005[0402]")
      (description "R0402, 0R not_mount")
      (fields (field (name "0R NOT_MOUNT") "R0402, 0R not_mount"))
      (libsource (lib "LIB_A10S") (part "CR0402-J/-000GLF not_mount"))
    )
    (comp (ref "R49")
      (value "ERJ-2RKF2213X")
      (footprint "RESC1005[0402]")
      (description "R0402, 221k 1%")
      (fields
        (field (name "MANUFACTURER") "Panasonic Electronic Components")
        (field (name "TOLERANCE") "±1%")
        (field (name "RESISTANCE (OHMS)") "221k")
      )
      (libsource (lib "RESISTOR") (part "ERJ-2RKF2213X"))
    )
    (comp (ref "R50")
      (value "ERJ-2RKF22R0X")
      (footprint "RESC1005[0402]")
      (description "R0402, 22R 1%")
      (fields
        (field (name "MANUFACTURER PART NUMBER") "ERJ2RKF33R2X")
        (field (name "MANUFACTURER") "PANASONIC")
        (field (name "RESISTANCE") "22R")
      )
      (libsource (lib "RESISTOR") (part "ERJ-2RKF22R0X"))
    )
    (comp (ref "R51")
      (value "ERJ-2RKF22R0X")
      (footprint "RESC1005[0402]")
      (description "R0402, 22R 1%")
      (fields
        (field (name "MANUFACTURER PART NUMBER") "ERJ2RKF33R2X")
        (field (name "MANUFACTURER") "PANASONIC")
        (field (name "RESISTANCE") "22R")
      )
      (libsource (lib "RESISTOR") (part "ERJ-2RKF22R0X"))
    )
    (comp (ref "R52")
      (value "ERJ-2RKF22R0X")
      (footprint "RESC1005[0402]")
      (description "R0402, 22R 1%")
      (fields
        (field (name "MANUFACTURER PART NUMBER") "ERJ2RKF33R2X")
        (field (name "MANUFACTURER") "PANASONIC")
        (field (name "RESISTANCE") "22R")
      )
      (libsource (lib "RESISTOR") (part "ERJ-2RKF22R0X"))
    )
    (comp (ref "R53")
      (value "ERJ-2RKF1051X")
      (footprint "RESC1005[0402]")
      (description "R0402, 1.05k 1%")
      (fields
        (field (name "MANUFACTURER") "Panasonic Electronic Components")
        (field (name "MANUFACTURER PART NUMBER") "ERJ-2RKF1001X")
        (field (name "RESISTANCE") "1.05k")
      )
      (libsource (lib "RESISTOR") (part "ERJ-2RKF1051X"))
    )
    (comp (ref "R54")
      (value "ERJ-2RKF2400X")
      (footprint "RESC1005[0402]")
      (description "R0402, 240R 1%")
      (fields
        (field (name "MANUFACTURER") "Panasonic Electronic Components")
        (field (name "MANUFACTURER PART NUMBER") "ERJ-2RKF2260X")
        (field (name "RESISTANCE (OHMS)") "240")
      )
      (libsource (lib "PUMA-10S") (part "ERJ-2RKF2400X"))
    )
    (comp (ref "R55")
      (value "ERJ-2RKF2400X")
      (footprint "RESC1005[0402]")
      (description "R0402, 240R 1%")
      (fields
        (field (name "MANUFACTURER") "Panasonic Electronic Components")
        (field (name "MANUFACTURER PART NUMBER") "ERJ-2RKF2260X")
        (field (name "RESISTANCE (OHMS)") "240")
      )
      (libsource (lib "PUMA-10S") (part "ERJ-2RKF2400X"))
    )
    (comp (ref "R56")
      (value "ERJ-2GEJ1R0X")
      (footprint "RESC1005[0402]")
      (description "R0402, 1R 5%")
      (fields
        (field (name "MANUFACTURER PART NUMBER") "ERJ-2GEJ101X")
        (field (name "MANUFACTURER") "Panasonic Electronic Components")
        (field (name "RESISTANCE (OHMS)") "1R")
      )
      (libsource (lib "RESISTOR") (part "ERJ-2GEJ1R0X"))
    )
    (comp (ref "R57")
      (value "ERJ-2RKF1002X")
      (footprint "RESC1005[0402]")
      (description "R0402, 10k 1%")
      (fields
        (field (name "TOLERANCE") "1 %")
        (field (name "MANUFACTURER") "Panasonic")
        (field (name "RESISTANCE") "10k")
      )
      (libsource (lib "PUMA-10S") (part "ERJ-2RKF1002X"))
    )
    (comp (ref "R58")
      (value "ERJ-2RKF1002X")
      (footprint "RESC1005[0402]")
      (description "R0402, 10k 1%")
      (fields
        (field (name "TOLERANCE") "1 %")
        (field (name "MANUFACTURER") "Panasonic")
        (field (name "RESISTANCE") "10k")
      )
      (libsource (lib "PUMA-10S") (part "ERJ-2RKF1002X"))
    )
    (comp (ref "R59")
      (value "ERJ-2RKF1002X")
      (footprint "RESC1005[0402]")
      (description "R0402, 10k 1%")
      (fields
        (field (name "MANUFACTURER") "Panasonic")
        (field (name "TOLERANCE") "1 %")
        (field (name "RESISTANCE") "10k")
      )
      (libsource (lib "PUMA-10S") (part "ERJ-2RKF1002X"))
    )
    (comp (ref "R60")
      (value "ERJ-2RKF1002X")
      (footprint "RESC1005[0402]")
      (description "R0402, 10k 1%")
      (fields
        (field (name "MANUFACTURER") "Panasonic")
        (field (name "TOLERANCE") "1 %")
        (field (name "RESISTANCE") "10k")
      )
      (libsource (lib "PUMA-10S") (part "ERJ-2RKF1002X"))
    )
    (comp (ref "R61")
      (value "ERJ-2RKF1002X")
      (footprint "RESC1005[0402]")
      (description "R0402, 10k 1%")
      (fields
        (field (name "MANUFACTURER") "Panasonic")
        (field (name "TOLERANCE") "1 %")
        (field (name "RESISTANCE") "10k")
      )
      (libsource (lib "PUMA-10S") (part "ERJ-2RKF1002X"))
    )
    (comp (ref "R62")
      (value "ERJ-2RKF2001X")
      (footprint "RESC1005[0402]")
      (description "R0402, 2k 1%")
      (fields
        (field (name "TOLERANCE") "±1%")
        (field (name "MANUFACTURER") "Panasonic Electronic Components")
        (field (name "RESISTANCE (OHMS)") "2k")
      )
      (libsource (lib "RESISTOR") (part "ERJ-2RKF2001X"))
    )
    (comp (ref "R63")
      (value "ERJ-2RKF1051X")
      (footprint "RESC1005[0402]")
      (description "R0402, 1.05k 1%")
      (fields
        (field (name "MANUFACTURER") "Panasonic Electronic Components")
        (field (name "MANUFACTURER PART NUMBER") "ERJ-2RKF1001X")
        (field (name "RESISTANCE") "1.05k")
      )
      (libsource (lib "PUMA-10S") (part "ERJ-2RKF1051X"))
    )
    (comp (ref "R64")
      (value "ERJ-2RKF22R0X")
      (footprint "RESC1005[0402]")
      (description "R0402, 22R 1%")
      (fields
        (field (name "MANUFACTURER PART NUMBER") "ERJ2RKF33R2X")
        (field (name "MANUFACTURER") "PANASONIC")
        (field (name "RESISTANCE") "22R")
      )
      (libsource (lib "RESISTOR") (part "ERJ-2RKF22R0X"))
    )
    (comp (ref "R65")
      (value "ERJ-2RKF4751X")
      (footprint "RESC1005[0402]")
      (description "R0402, 4.75k 1%")
      (fields
        (field (name "TOLERANCE") "±1%")
        (field (name "MANUFACTURER") "Panasonic Electronic Components")
        (field (name "RESISTANCE (OHMS)") "4.75k")
      )
      (libsource (lib "PUMA-10S") (part "ERJ-2RKF4751X"))
    )
    (comp (ref "R66")
      (value "ERJ-2RKF4751X")
      (footprint "RESC1005[0402]")
      (description "R0402, 4.75k 1%")
      (fields
        (field (name "TOLERANCE") "±1%")
        (field (name "MANUFACTURER") "Panasonic Electronic Components")
        (field (name "RESISTANCE (OHMS)") "4.75k")
      )
      (libsource (lib "PUMA-10S") (part "ERJ-2RKF4751X"))
    )
    (comp (ref "R67")
      (value "ERJ-2RKF1051X")
      (footprint "RESC1005[0402]")
      (description "R0402, 1.05k 1%")
      (fields
        (field (name "MANUFACTURER") "Panasonic Electronic Components")
        (field (name "MANUFACTURER PART NUMBER") "ERJ-2RKF1001X")
        (field (name "RESISTANCE") "1.05k")
      )
      (libsource (lib "RESISTOR") (part "ERJ-2RKF1051X"))
    )
    (comp (ref "R68")
      (value "ERJ-2RKF2001X")
      (footprint "RESC1005[0402]")
      (description "R0402, 2k 1%")
      (fields
        (field (name "TOLERANCE") "±1%")
        (field (name "MANUFACTURER") "Panasonic Electronic Components")
        (field (name "RESISTANCE (OHMS)") "2k")
      )
      (libsource (lib "RESISTOR") (part "ERJ-2RKF2001X"))
    )
    (comp (ref "R69")
      (value "ERJ-2RKF4751X")
      (footprint "RESC1005[0402]")
      (description "R0402, 4.75k 1%")
      (fields
        (field (name "TOLERANCE") "±1%")
        (field (name "MANUFACTURER") "Panasonic Electronic Components")
        (field (name "RESISTANCE (OHMS)") "4.75k")
      )
      (libsource (lib "PUMA-10S") (part "ERJ-2RKF4751X"))
    )
    (comp (ref "R70")
      (value "ERJ-2RKF2001X")
      (footprint "RESC1005[0402]")
      (description "R0402, 2k 1%")
      (fields
        (field (name "TOLERANCE") "±1%")
        (field (name "MANUFACTURER") "Panasonic Electronic Components")
        (field (name "RESISTANCE (OHMS)") "2k")
      )
      (libsource (lib "RESISTOR") (part "ERJ-2RKF2001X"))
    )
    (comp (ref "R71")
      (value "ERJ-2RKF1002X")
      (footprint "RESC1005[0402]")
      (description "R0402, 10k 1%")
      (fields
        (field (name "TOLERANCE") "1 %")
        (field (name "MANUFACTURER") "Panasonic")
        (field (name "RESISTANCE") "10k")
      )
      (libsource (lib "PUMA-10S") (part "ERJ-2RKF1002X"))
    )
    (comp (ref "R72")
      (value "ERJ-2RKF4751X")
      (footprint "RESC1005[0402]")
      (description "R0402, 4.75k 1%")
      (fields
        (field (name "TOLERANCE") "±1%")
        (field (name "MANUFACTURER") "Panasonic Electronic Components")
        (field (name "RESISTANCE (OHMS)") "4.75k")
      )
      (libsource (lib "PUMA-10S") (part "ERJ-2RKF4751X"))
    )
    (comp (ref "R73")
      (value "ERJ-2RKF1051X")
      (footprint "RESC1005[0402]")
      (description "R0402, 1.05k 1%")
      (fields
        (field (name "MANUFACTURER") "Panasonic Electronic Components")
        (field (name "MANUFACTURER PART NUMBER") "ERJ-2RKF1001X")
        (field (name "RESISTANCE") "1.05k")
      )
      (libsource (lib "RESISTOR") (part "ERJ-2RKF1051X"))
    )
    (comp (ref "R74")
      (value "ERJ-2RKF4751X")
      (footprint "RESC1005[0402]")
      (description "R0402, 4.75k 1%")
      (fields
        (field (name "TOLERANCE") "±1%")
        (field (name "MANUFACTURER") "Panasonic Electronic Components")
        (field (name "RESISTANCE (OHMS)") "4.75k")
      )
      (libsource (lib "PUMA-10S") (part "ERJ-2RKF4751X"))
    )
    (comp (ref "R75")
      (value "ERJ-2RKF4751X")
      (footprint "RESC1005[0402]")
      (description "R0402, 4.75k 1%")
      (fields
        (field (name "TOLERANCE") "±1%")
        (field (name "MANUFACTURER") "Panasonic Electronic Components")
        (field (name "RESISTANCE (OHMS)") "4.75k")
      )
      (libsource (lib "PUMA-10S") (part "ERJ-2RKF4751X"))
    )
    (comp (ref "R76")
      (value "ERJ-2RKF4751X")
      (footprint "RESC1005[0402]")
      (description "R0402, 4.75k 1%")
      (fields
        (field (name "TOLERANCE") "±1%")
        (field (name "MANUFACTURER") "Panasonic Electronic Components")
        (field (name "RESISTANCE (OHMS)") "4.75k")
      )
      (libsource (lib "PUMA-10S") (part "ERJ-2RKF4751X"))
    )
    (comp (ref "R77")
      (value "ERJ-2RKF1051X")
      (footprint "RESC1005[0402]")
      (description "R0402, 1.05k 1%")
      (fields
        (field (name "MANUFACTURER") "Panasonic Electronic Components")
        (field (name "MANUFACTURER PART NUMBER") "ERJ-2RKF1001X")
        (field (name "RESISTANCE") "1.05k")
      )
      (libsource (lib "RESISTOR") (part "ERJ-2RKF1051X"))
    )
    (comp (ref "R78")
      (value "ERJ-2RKF4751X")
      (footprint "RESC1005[0402]")
      (description "R0402, 4.75k 1%")
      (fields
        (field (name "TOLERANCE") "±1%")
        (field (name "MANUFACTURER") "Panasonic Electronic Components")
        (field (name "RESISTANCE (OHMS)") "4.75k")
      )
      (libsource (lib "PUMA-10S") (part "ERJ-2RKF4751X"))
    )
    (comp (ref "R79")
      (value "ERJ-2RKF6041X")
      (footprint "RESISTOR:RESC1005[0402]")
      (description "R0402, 6.04k 1%")
      (fields
        (field (name "TOLERANCE") "±1%")
        (field (name "MANUFACTURER") "Panasonic Electronic Components")
        (field (name "RESISTANCE (OHMS)") "6.04k")
      )
      (libsource (lib "RESISTOR") (part "ERJ-2RKF6041X"))
    )
    (comp (ref "R80")
      (value "ERJ-2RKF4751X")
      (footprint "RESC1005[0402]")
      (description "R0402, 4.75k 1%")
      (fields
        (field (name "TOLERANCE") "±1%")
        (field (name "MANUFACTURER") "Panasonic Electronic Components")
        (field (name "RESISTANCE (OHMS)") "4.75k")
      )
      (libsource (lib "PUMA-10S") (part "ERJ-2RKF4751X"))
    )
    (comp (ref "R81")
      (value "ERJ-2RKF4751X")
      (footprint "RESC1005[0402]")
      (description "R0402, 4.75k 1%")
      (fields
        (field (name "TOLERANCE") "±1%")
        (field (name "MANUFACTURER") "Panasonic Electronic Components")
        (field (name "RESISTANCE (OHMS)") "4.75k")
      )
      (libsource (lib "PUMA-10S") (part "ERJ-2RKF4751X"))
    )
    (comp (ref "R82")
      (value "ERJ-2RKF1051X")
      (footprint "RESC1005[0402]")
      (description "R0402, 1.05k 1%")
      (fields
        (field (name "MANUFACTURER") "Panasonic Electronic Components")
        (field (name "MANUFACTURER PART NUMBER") "ERJ-2RKF1001X")
        (field (name "RESISTANCE") "1.05k")
      )
      (libsource (lib "RESISTOR") (part "ERJ-2RKF1051X"))
    )
    (comp (ref "R83")
      (value "ERJ-2RKF2400X")
      (footprint "RESC1005[0402]")
      (description "R0402, 240R 1%")
      (fields
        (field (name "MANUFACTURER") "Panasonic Electronic Components")
        (field (name "MANUFACTURER PART NUMBER") "ERJ-2RKF2260X")
        (field (name "RESISTANCE (OHMS)") "240")
      )
      (libsource (lib "PUMA-10S") (part "ERJ-2RKF2400X"))
    )
    (comp (ref "R85")
      (value "ERJ-2RKF1002X")
      (footprint "RESC1005[0402]")
      (description "R0402, 10k 1%")
      (fields
        (field (name "MANUFACTURER") "Panasonic")
        (field (name "TOLERANCE") "1 %")
        (field (name "RESISTANCE") "10k")
      )
      (libsource (lib "PUMA-10S") (part "ERJ-2RKF1002X"))
    )
    (comp (ref "R87")
      (value "ERJ-2RKF4751X")
      (footprint "RESC1005[0402]")
      (description "R0402, 4.75k 1%")
      (fields
        (field (name "TOLERANCE") "±1%")
        (field (name "MANUFACTURER") "Panasonic Electronic Components")
        (field (name "RESISTANCE (OHMS)") "4.75k")
      )
      (libsource (lib "PUMA-10S") (part "ERJ-2RKF4751X"))
    )
    (comp (ref "R88")
      (value "ERJ-2RKF1051X")
      (footprint "RESC1005[0402]")
      (description "R0402, 1.05k 1%")
      (fields
        (field (name "MANUFACTURER") "Panasonic Electronic Components")
        (field (name "MANUFACTURER PART NUMBER") "ERJ-2RKF1001X")
        (field (name "RESISTANCE") "1.05k")
      )
      (libsource (lib "RESISTOR") (part "ERJ-2RKF1051X"))
    )
    (comp (ref "R90")
      (value "ERJ-2RKF9090X")
      (footprint "RESISTOR:RESC1005[0402]")
      (description "R0402, 909R 1%")
      (fields (field (name "TOLERANCE") "1 %") (field (name "RESISTANCE") "909"))
      (libsource (lib "PUMA-10S") (part "ERJ-2RKF9090X"))
    )
    (comp (ref "R92")
      (value "ERJ-2RKF1002X")
      (footprint "RESC1005[0402]")
      (description "R0402, 10k 1%")
      (fields
        (field (name "MANUFACTURER") "Panasonic")
        (field (name "TOLERANCE") "1 %")
        (field (name "RESISTANCE") "10k")
      )
      (libsource (lib "PUMA-10S") (part "ERJ-2RKF1002X"))
    )
    (comp (ref "R93")
      (value "ERJ-2RKF4751X")
      (footprint "RESC1005[0402]")
      (description "R0402, 4.75k 1%")
      (fields
        (field (name "TOLERANCE") "±1%")
        (field (name "MANUFACTURER") "Panasonic Electronic Components")
        (field (name "RESISTANCE (OHMS)") "4.75k")
      )
      (libsource (lib "PUMA-10S") (part "ERJ-2RKF4751X"))
    )
    (comp (ref "VD1")
      (value "RCLAMP0524P")
      (footprint "SLP2510P8")
      (description "Ultra Low Capacitance TVS Arrays")
      (libsource (lib "PUMA-10S_V1") (part "RCLAMP0524P"))
    )
    (comp (ref "VD2")
      (value "RCLAMP0524P")
      (footprint "SLP2510P8")
      (description "Ultra Low Capacitance TVS Arrays")
      (libsource (lib "PUMA-10S_V1") (part "RCLAMP0524P"))
    )
    (comp (ref "VD3")
      (value "BAT54C-G")
      (footprint "SOT-23")
      (description "DIODE SCHOTTKY  200mA 30V SOT23")
      (libsource (lib "") (part "BAT54C-G_1"))
    )
    (comp (ref "VD4")
      (value "BAT54C-G")
      (footprint "SOT-23")
      (description "DIODE SCHOTTKY  200mA 30V SOT23")
      (libsource (lib "PUMA-10S_V0") (part "BAT54C-G"))
    )
    (comp (ref "VD5")
      (value "BAT54C-G")
      (footprint "SOT-23")
      (description "DIODE SCHOTTKY  200mA 30V SOT23")
      (libsource (lib "") (part "BAT54C-G_1"))
    )
    (comp (ref "VD6")
      (value "1SMA18AT3")
      (footprint "DIODES:SMA")
      (description "DIODE TVS 18V 400W SMA")
      (fields
        (field (name "MANUFACTURER") "ON Semiconductor")
        (field (name "MANUFACTURER PART NUMBER") "1SMA18AT3G")
      )
      (libsource (lib "DIODES") (part "1SMA18AT3"))
    )
    (comp (ref "VD7")
      (value "BAV99")
      (footprint "SOT-23")
      (description "High-speed switching diodes, SOT23")
      (libsource (lib "DIODES") (part "BAV99"))
    )
    (comp (ref "VD8")
      (value "BAV99")
      (footprint "SOT-23")
      (description "High-speed switching diodes, SOT23")
      (libsource (lib "") (part "BAV99_1"))
    )
    (comp (ref "VD9")
      (value "BAV99")
      (footprint "SOT-23")
      (description "High-speed switching diodes, SOT23")
      (libsource (lib "") (part "BAV99_1"))
    )
    (comp (ref "VD10")
      (value "BAV99")
      (footprint "SOT-23")
      (description "High-speed switching diodes, SOT23")
      (libsource (lib "") (part "BAV99_1"))
    )
    (comp (ref "VD11")
      (value "BAV99")
      (footprint "SOT-23")
      (description "High-speed switching diodes, SOT23")
      (libsource (lib "") (part "BAV99_1"))
    )
    (comp (ref "VD12")
      (value "BAV99")
      (footprint "SOT-23")
      (description "High-speed switching diodes, SOT23")
      (libsource (lib "DIODES") (part "BAV99"))
    )
    (comp (ref "VD13")
      (value "BAV99")
      (footprint "SOT-23")
      (description "High-speed switching diodes, SOT23")
      (libsource (lib "DIODES") (part "BAV99"))
    )
    (comp (ref "VD14")
      (value "BAV99")
      (footprint "SOT-23")
      (description "High-speed switching diodes, SOT23")
      (libsource (lib "DIODES") (part "BAV99"))
    )
    (comp (ref "XP1")
      (value "PJ320D")
      (footprint "PJ320D")
      (description "SMT Female 3.5mm Headphone Jacks")
      (libsource (lib "PUMA-10S_V0") (part "PJ320D"))
    )
    (comp (ref "XP2")
      (value "XUSB-F0125")
      (footprint "USB_A_VERTICAL_PTH")
      (description "USB_A_VERTICAL, Right Angle Single Port")
      (libsource (lib "PUMA-10S_V0") (part "USB_A_VERTICAL"))
    )
    (comp (ref "XP3")
      (value "PJ320D")
      (footprint "PJ320D")
      (description "SMT Female 3.5mm Headphone Jacks")
      (libsource (lib "PUMA-10S_V0") (part "PJ320D"))
    )
    (comp (ref "XP4")
      (value "1734035-1")
      (footprint "MINI USB, R/A, SMT, B TYPE")
      (description "MINI USB, R/A, SMT, B TYPE")
      (libsource (lib "LIB_A10S") (part "MINI USB, R/A, SMT, B TYPE"))
    )
    (comp (ref "XP5")
      (value "10029449-001RLF")
      (footprint "10029449-001RLF")
      (description "HDMI Connectors")
      (fields (field (name "ALTIUM_UNNAMED_1") "HDMI Connectors"))
      (libsource (lib "LIB_A10S") (part "10029449-001RLF"))
    )
    (comp (ref "XP6")
      (value "RCJ-044")
      (footprint "RCJ-044")
      (description "RCA Jack Connector, Yellow")
      (libsource (lib "PUMA-10S") (part "RCJ-044"))
    )
    (comp (ref "XP7")
      (value "PLD-10")
      (footprint "PLD-10")
      (description "Connector PLD-10")
      (libsource (lib "CONNECTORS") (part "PLD-10"))
    )
    (comp (ref "XP8")
      (value "PLS-2")
      (footprint "PLS-2")
      (description "Connector PLS-2 (2.54mm x1)")
      (libsource (lib "CONNECTORS") (part "PLS-2"))
    )
    (comp (ref "XP9")
      (value "PLS-4")
      (footprint "PLS-4")
      (description "Connector PLS-4 (2.54mm x1)")
      (libsource (lib "CONNECTORS") (part "PLS-4"))
    )
    (comp (ref "XP10")
      (value "PBD-40 (114A-DS40G)")
      (footprint "PBD-40")
      (description "Connector PBD-40")
      (libsource (lib "CONNECTORS") (part "PBD-40"))
    )
    (comp (ref "XP11")
      (value "PBD-30 (114A-DS30G)")
      (footprint "PBD-30")
      (description "Connector PBD-30")
      (libsource (lib "CONNECTORS") (part "PBD-30"))
    )
    (comp (ref "XP13")
      (value "PJ-002BH-SMT")
      (footprint "PJ-002BH-SMT")
      (description "2.5 mm Center Pin, 5.0 A, Right Angle, Surface Mount (SMT), Dc Power Jack Connector")
      (libsource (lib "LIB_A10S") (part "PJ-002BH-SMT"))
    )
    (comp (ref "XP14")
      (value "PLD-10_not_mount")
      (footprint "PLD-10_not_mount")
      (description "Connector PLD-10")
      (libsource (lib "CONNECTORS") (part "PLD-10"))
    )
    (comp (ref "XS1")
      (value "HR911105A")
      (footprint "HR911105A")
      (description "Single Port RJ45 connector with magnetics module and LED")
      (libsource (lib "PUMA-10S") (part "HR911105A"))
    )
    (comp (ref "XS2")
      (value "112J-TXAR-R")
      (footprint "112J-TDAR-R")
      (description "Connector microSD Push-push Type")
      (libsource (lib "CONNECTORS") (part "microSD"))
    )
  )
  (nets
    (net (code "1") (name "/5VHDMI") (class "Default")
      (node (ref "C142") (pin "2") (pintype "passive"))
      (node (ref "VD3") (pin "3") (pinfunction "3_3") (pintype "passive"))
      (node (ref "XP5") (pin "18") (pinfunction "18_18") (pintype "passive"))
    )
    (net (code "2") (name "/5VUSB") (class "Default")
      (node (ref "C52") (pin "2") (pintype "passive"))
      (node (ref "C53") (pin "2") (pintype "passive"))
      (node (ref "DD4") (pin "1") (pinfunction "OUT_1") (pintype "passive"))
      (node (ref "R33") (pin "2") (pintype "passive"))
      (node (ref "XP2") (pin "1") (pinfunction "1_1") (pintype "passive"))
    )
    (net (code "3") (name "/BA0") (class "Default")
      (node (ref "DD1") (pin "U6") (pinfunction "SBA0/DDR2_BA2/DDR3_BA0_U6") (pintype "passive"))
      (node (ref "DD3") (pin "J2") (pinfunction "BA0_J2") (pintype "passive"))
      (node (ref "DD6") (pin "J2") (pinfunction "BA0_J2") (pintype "passive"))
    )
    (net (code "4") (name "/BA1") (class "Default")
      (node (ref "DD1") (pin "N3") (pinfunction "SBA1/DDR2_CS0/DDR3_BA1_N3") (pintype "passive"))
      (node (ref "DD3") (pin "K8") (pinfunction "BA1_K8") (pintype "passive"))
      (node (ref "DD6") (pin "K8") (pinfunction "BA1_K8") (pintype "passive"))
    )
    (net (code "5") (name "/BA2") (class "Default")
      (node (ref "DD1") (pin "V6") (pinfunction "SBA2/DDR2_WE/DDR3_BA2_V6") (pintype "passive"))
      (node (ref "DD3") (pin "J3") (pinfunction "BA2_J3") (pintype "passive"))
      (node (ref "DD6") (pin "J3") (pinfunction "BA2_J3") (pintype "passive"))
    )
    (net (code "6") (name "/CAS") (class "Default")
      (node (ref "DD1") (pin "V4") (pinfunction "SCAS/DDR2_A13/DDR3_CAS_V4") (pintype "passive"))
      (node (ref "DD3") (pin "G3") (pinfunction "#CAS_G3") (pintype "passive"))
      (node (ref "DD6") (pin "G3") (pinfunction "#CAS_G3") (pintype "passive"))
    )
    (net (code "7") (name "/CKE0") (class "Default")
      (node (ref "DD1") (pin "L3") (pinfunction "SCKE0/DDR2_ODT0/DDR3_CKE0_L3") (pintype "passive"))
      (node (ref "DD3") (pin "G9") (pinfunction "CKE_G9") (pintype "passive"))
      (node (ref "DD6") (pin "G9") (pinfunction "CKE_G9") (pintype "passive"))
    )
    (net (code "8") (name "/CKE1") (class "Default")
      (node (ref "DD1") (pin "U5") (pinfunction "SCKE1/DDR2_CKE1/DDR3_CKE1_U5") (pintype "passive"))
      (node (ref "DD3") (pin "F9") (pinfunction "NC/CKE1_F9") (pintype "passive"))
      (node (ref "DD6") (pin "F9") (pinfunction "NC/CKE1_F9") (pintype "passive"))
    )
    (net (code "9") (name "/CLKR_N") (class "Default")
      (node (ref "DD1") (pin "Y1") (pinfunction "SCK_N/DDR2_CK_N/DDR3_CK_N_Y1") (pintype "passive"))
      (node (ref "R9") (pin "2") (pintype "passive"))
    )
    (net (code "10") (name "/CLKR_P") (class "Default")
      (node (ref "DD1") (pin "W2") (pinfunction "SCK/DDR2_CK/DDR3_CK_W2") (pintype "passive"))
      (node (ref "R7") (pin "2") (pintype "passive"))
    )
    (net (code "11") (name "/CLK_N") (class "Default")
      (node (ref "DD3") (pin "G7") (pinfunction "#CK_G7") (pintype "passive"))
      (node (ref "DD6") (pin "G7") (pinfunction "#CK_G7") (pintype "passive"))
      (node (ref "R9") (pin "1") (pintype "passive"))
    )
    (net (code "12") (name "/CLK_P") (class "Default")
      (node (ref "DD3") (pin "F7") (pinfunction "CK_F7") (pintype "passive"))
      (node (ref "DD6") (pin "F7") (pinfunction "CK_F7") (pintype "passive"))
      (node (ref "R7") (pin "1") (pintype "passive"))
    )
    (net (code "13") (name "/CVREF") (class "Default")
      (node (ref "C29") (pin "2") (pintype "passive"))
      (node (ref "C30") (pin "2") (pintype "passive"))
      (node (ref "C31") (pin "2") (pintype "passive"))
      (node (ref "C33") (pin "2") (pintype "passive"))
      (node (ref "C34") (pin "2") (pintype "passive"))
      (node (ref "C35") (pin "2") (pintype "passive"))
      (node (ref "C36") (pin "2") (pintype "passive"))
      (node (ref "C37") (pin "1") (pintype "passive"))
      (node (ref "DD1") (pin "L4") (pinfunction "SVREF0_L4") (pintype "passive"))
      (node (ref "DD1") (pin "U11") (pinfunction "SVREF1_U11") (pintype "passive"))
      (node (ref "DD3") (pin "E1") (pinfunction "VREFDQ_E1") (pintype "passive"))
      (node (ref "DD3") (pin "J8") (pinfunction "VREFCA_J8") (pintype "passive"))
      (node (ref "DD6") (pin "E1") (pinfunction "VREFDQ_E1") (pintype "passive"))
      (node (ref "DD6") (pin "J8") (pinfunction "VREFCA_J8") (pintype "passive"))
      (node (ref "R29") (pin "2") (pintype "passive"))
      (node (ref "R30") (pin "1") (pintype "passive"))
    )
    (net (code "14") (name "/D0") (class "Default")
      (node (ref "DD1") (pin "J1") (pinfunction "SDQ6/DDR2_D3/DDR3_D6_J1") (pintype "passive"))
      (node (ref "DD3") (pin "B3") (pinfunction "DQ0_B3") (pintype "passive"))
    )
    (net (code "15") (name "/D1") (class "Default")
      (node (ref "DD1") (pin "U2") (pinfunction "SDQ1/DDR2_D7/DDR3_D1_U2") (pintype "passive"))
      (node (ref "DD3") (pin "C7") (pinfunction "DQ1_C7") (pintype "passive"))
    )
    (net (code "16") (name "/D2") (class "Default")
      (node (ref "DD1") (pin "J2") (pinfunction "SDQ2/DDR2_D1/DDR3_D2_J2") (pintype "passive"))
      (node (ref "DD3") (pin "C2") (pinfunction "DQ2_C2") (pintype "passive"))
    )
    (net (code "17") (name "/D3") (class "Default")
      (node (ref "DD1") (pin "V1") (pinfunction "SDQ3/DDR2_D0/DDR3_D3_V1") (pintype "passive"))
      (node (ref "DD3") (pin "C8") (pinfunction "DQ3_C8") (pintype "passive"))
    )
    (net (code "18") (name "/D4") (class "Default")
      (node (ref "DD1") (pin "K1") (pinfunction "SDQ0/DDR2_D6/DDR3_D0_K1") (pintype "passive"))
      (node (ref "DD3") (pin "E3") (pinfunction "DQ4_E3") (pintype "passive"))
    )
    (net (code "19") (name "/D5") (class "Default")
      (node (ref "DD1") (pin "W1") (pinfunction "SDQ5/DDR2_D5/DDR3_D5_W1") (pintype "passive"))
      (node (ref "DD3") (pin "E8") (pinfunction "DQ5_E8") (pintype "passive"))
    )
    (net (code "20") (name "/D6") (class "Default")
      (node (ref "DD1") (pin "J3") (pinfunction "SDQ4/DDR2_D4/DDR3_D4_J3") (pintype "passive"))
      (node (ref "DD3") (pin "D2") (pinfunction "DQ6_D2") (pintype "passive"))
    )
    (net (code "21") (name "/D7") (class "Default")
      (node (ref "DD1") (pin "V2") (pinfunction "SDQ7/DDR2_D2/DDR3_D7_V2") (pintype "passive"))
      (node (ref "DD3") (pin "E7") (pinfunction "DQ7_E7") (pintype "passive"))
    )
    (net (code "22") (name "/D8") (class "Default")
      (node (ref "DD1") (pin "L1") (pinfunction "SDQ13/DDR2_D9/DDR3_D13_L1") (pintype "passive"))
      (node (ref "DD6") (pin "B3") (pinfunction "DQ0_B3") (pintype "passive"))
    )
    (net (code "23") (name "/D9") (class "Default")
      (node (ref "DD1") (pin "U1") (pinfunction "SDQ10/DDR2_D13/DDR3_D10_U1") (pintype "passive"))
      (node (ref "DD6") (pin "C7") (pinfunction "DQ1_C7") (pintype "passive"))
    )
    (net (code "24") (name "/D10") (class "Default")
      (node (ref "DD1") (pin "K2") (pinfunction "SDQ11/DDR2_D12/DDR3_D11_K2") (pintype "passive"))
      (node (ref "DD6") (pin "C2") (pinfunction "DQ2_C2") (pintype "passive"))
    )
    (net (code "25") (name "/D11") (class "Default")
      (node (ref "DD1") (pin "T2") (pinfunction "SDQ14/DDR2_D10/DDR3_D14_T2") (pintype "passive"))
      (node (ref "DD6") (pin "C8") (pinfunction "DQ3_C8") (pintype "passive"))
    )
    (net (code "26") (name "/D12") (class "Default")
      (node (ref "DD1") (pin "M1") (pinfunction "SDQ9/DDR2_D11/DDR3_D9_M1") (pintype "passive"))
      (node (ref "DD6") (pin "E3") (pinfunction "DQ4_E3") (pintype "passive"))
    )
    (net (code "27") (name "/D13") (class "Default")
      (node (ref "DD1") (pin "R2") (pinfunction "SDQ12/DDR2_D15/DDR3_D12_R2") (pintype "passive"))
      (node (ref "DD6") (pin "E8") (pinfunction "DQ5_E8") (pintype "passive"))
    )
    (net (code "28") (name "/D14") (class "Default")
      (node (ref "DD1") (pin "L2") (pinfunction "SDQ15/DDR2_D14/DDR3_D15_L2") (pintype "passive"))
      (node (ref "DD6") (pin "D2") (pinfunction "DQ6_D2") (pintype "passive"))
    )
    (net (code "29") (name "/D15") (class "Default")
      (node (ref "DD1") (pin "T1") (pinfunction "SDQ8/DDR2_D8/DDR3_D8_T1") (pintype "passive"))
      (node (ref "DD6") (pin "E7") (pinfunction "DQ7_E7") (pintype "passive"))
    )
    (net (code "30") (name "/DDR3_CS0") (class "Default")
      (node (ref "DD1") (pin "V5") (pinfunction "SCS0/DDR2_CS0/DDR3_CS0_V5") (pintype "passive"))
      (node (ref "DD3") (pin "H2") (pinfunction "#CS_H2") (pintype "passive"))
      (node (ref "DD6") (pin "H2") (pinfunction "#CS_H2") (pintype "passive"))
    )
    (net (code "31") (name "/DDR3_CS1") (class "Default")
      (node (ref "DD1") (pin "N4") (pinfunction "SCS1/DDR2_CS1/DDR3_CS1_N4") (pintype "passive"))
      (node (ref "DD3") (pin "H1") (pinfunction "NC/#CS1_H1") (pintype "passive"))
      (node (ref "DD6") (pin "H1") (pinfunction "NC/#CS1_H1") (pintype "passive"))
    )
    (net (code "32") (name "/DDR3_RST") (class "Default")
      (node (ref "DD1") (pin "U10") (pinfunction "SRST/DDR2_A9/DDR3_RST_U10") (pintype "passive"))
      (node (ref "DD3") (pin "N2") (pinfunction "#RESET_N2") (pintype "passive"))
      (node (ref "DD6") (pin "N2") (pinfunction "#RESET_N2") (pintype "passive"))
    )
    (net (code "33") (name "/DQM0") (class "Default")
      (node (ref "DD1") (pin "P1") (pinfunction "SDQM0/DDR2_DM0/DDR3_DM0_P1") (pintype "passive"))
      (node (ref "DD3") (pin "B7") (pinfunction "DM/TDQS_B7") (pintype "passive"))
    )
    (net (code "34") (name "/DQM1") (class "Default")
      (node (ref "DD1") (pin "M2") (pinfunction "SDQM1/DDR2_DM1/DDR3_DM1_M2") (pintype "passive"))
      (node (ref "DD6") (pin "B7") (pinfunction "DM/TDQS_B7") (pintype "passive"))
    )
    (net (code "35") (name "/DQS0_N") (class "Default")
      (node (ref "DD1") (pin "N2") (pinfunction "SDQS0_N/DDR2_DQS0_N/DDR3_DQS0_N_N2") (pintype "passive"))
      (node (ref "DD3") (pin "D3") (pinfunction "#DQS_D3") (pintype "passive"))
    )
    (net (code "36") (name "/DQS0_P") (class "Default")
      (node (ref "DD1") (pin "N1") (pinfunction "SDQS0/DDR2_DQS0/DDR3_DQS0_N1") (pintype "passive"))
      (node (ref "DD3") (pin "C3") (pinfunction "DQS_C3") (pintype "passive"))
    )
    (net (code "37") (name "/DQS1_N") (class "Default")
      (node (ref "DD1") (pin "R1") (pinfunction "SDQS1_N/DDR2_DQS1_N/DDR3_DQS1_N_R1") (pintype "passive"))
      (node (ref "DD6") (pin "D3") (pinfunction "#DQS_D3") (pintype "passive"))
    )
    (net (code "38") (name "/DQS1_P") (class "Default")
      (node (ref "DD1") (pin "P2") (pinfunction "SDQS1/DDR2_DQS1/DDR3_DQS1_P2") (pintype "passive"))
      (node (ref "DD6") (pin "C3") (pinfunction "DQS_C3") (pintype "passive"))
    )
    (net (code "39") (name "/ECOL") (class "Default")
      (node (ref "DD1") (pin "D14") (pinfunction "PA16/ECOL/UART2_TX_D14") (pintype "passive"))
      (node (ref "DD2") (pin "1") (pinfunction "COL_1") (pintype "passive"))
      (node (ref "R25") (pin "1") (pintype "passive"))
    )
    (net (code "40") (name "/ECRS") (class "Default")
      (node (ref "DD1") (pin "C13") (pinfunction "PA15/ECRS/UART1_RTS/UART3_RX/KP_OUT7_C13") (pintype "passive"))
      (node (ref "DD2") (pin "23") (pinfunction "CRS_23") (pintype "passive"))
      (node (ref "R31") (pin "1") (pintype "passive"))
    )
    (net (code "41") (name "/EMDC") (class "Default")
      (node (ref "DD1") (pin "C12") (pinfunction "PA11/EMDC/TS_D7/UART1_RING/KP_OUT3_C12") (pintype "passive"))
      (node (ref "DD2") (pin "25") (pinfunction "MDC_25") (pintype "passive"))
    )
    (net (code "42") (name "/EMDIO") (class "Default")
      (node (ref "DD1") (pin "D13") (pinfunction "PA12/EMDIO/UART1_TX/KP_OUT4_D13") (pintype "passive"))
      (node (ref "DD2") (pin "26") (pinfunction "MDIO_26") (pintype "passive"))
      (node (ref "R3") (pin "2") (pintype "passive"))
    )
    (net (code "43") (name "/EPHY-RST#") (class "Default")
      (node (ref "DD1") (pin "C14") (pinfunction "PA17/ETXERR/UART2_RX/EINT31_C14") (pintype "passive"))
      (node (ref "R13") (pin "1") (pintype "passive"))
    )
    (net (code "44") (name "/ERXCK") (class "Default")
      (node (ref "DD1") (pin "D10") (pinfunction "PA8/ERXCK/TS_D4/UART1_DTR/KP_OUT0_D10") (pintype "passive"))
      (node (ref "DD2") (pin "16") (pinfunction "RXC_16") (pintype "passive"))
    )
    (net (code "45") (name "/ERXD0") (class "Default")
      (node (ref "DD1") (pin "C7") (pinfunction "PA3/ERXD0/TS_DVLD/KP_IN3_C7") (pintype "passive"))
      (node (ref "DD2") (pin "21") (pinfunction "RXD0_21") (pintype "passive"))
    )
    (net (code "46") (name "/ERXD1") (class "Default")
      (node (ref "DD1") (pin "D7") (pinfunction "PA2/ERXD1/TS_SYNC/KP_IN2_D7") (pintype "passive"))
      (node (ref "DD2") (pin "20") (pinfunction "RXD1_20") (pintype "passive"))
    )
    (net (code "47") (name "/ERXD2") (class "Default")
      (node (ref "DD1") (pin "C6") (pinfunction "PA1/ERXD2/TS_ERR/KP_IN1_C6") (pintype "passive"))
      (node (ref "DD2") (pin "19") (pinfunction "RXD2_19") (pintype "passive"))
    )
    (net (code "48") (name "/ERXD3") (class "Default")
      (node (ref "DD1") (pin "D6") (pinfunction "PA0/ERXD3/TS_CLK/KP_IN0_D6") (pintype "passive"))
      (node (ref "DD2") (pin "18") (pinfunction "RXD3_18") (pintype "passive"))
    )
    (net (code "49") (name "/ERXDV") (class "Default")
      (node (ref "DD1") (pin "D11") (pinfunction "PA10/ERXDV/TS_D6/UART1_DCD/KP_OUT2_D11") (pintype "passive"))
      (node (ref "DD2") (pin "22") (pinfunction "RXDV_22") (pintype "passive"))
    )
    (net (code "50") (name "/ERXERR") (class "Default")
      (node (ref "DD1") (pin "C10") (pinfunction "PA9/ERXERR/TS_D5/UART1_DSR/KP_OUT1_C10") (pintype "passive"))
      (node (ref "DD2") (pin "24") (pinfunction "RXER/FXEN_24") (pintype "passive"))
      (node (ref "R28") (pin "1") (pintype "passive"))
    )
    (net (code "51") (name "/ETXCK") (class "Default")
      (node (ref "DD1") (pin "D12") (pinfunction "PA14/ETXCK/UART1_CTS/UART3_TX/KP_OUT6_D12") (pintype "passive"))
      (node (ref "DD2") (pin "7") (pinfunction "TXC_7") (pintype "passive"))
    )
    (net (code "52") (name "/ETXD0") (class "Default")
      (node (ref "DD1") (pin "C9") (pinfunction "PA7/ETXD0/TS_D3/KP_IN7_C9") (pintype "passive"))
      (node (ref "DD2") (pin "6") (pinfunction "TXD0_6") (pintype "passive"))
    )
    (net (code "53") (name "/ETXD1") (class "Default")
      (node (ref "DD1") (pin "D9") (pinfunction "PA6/ETXD1/TS_D2/KP_IN6_D9") (pintype "passive"))
      (node (ref "DD2") (pin "5") (pinfunction "TXD1_5") (pintype "passive"))
    )
    (net (code "54") (name "/ETXD2") (class "Default")
      (node (ref "DD1") (pin "C8") (pinfunction "PA5/ETXD2/TS_D1/KP_IN5_C8") (pintype "passive"))
      (node (ref "DD2") (pin "4") (pinfunction "TXD2_4") (pintype "passive"))
    )
    (net (code "55") (name "/ETXD3") (class "Default")
      (node (ref "DD1") (pin "D8") (pinfunction "PA4/ETXD3/TS_DO/KP_IN4_D8") (pintype "passive"))
      (node (ref "DD2") (pin "3") (pinfunction "TXD3_3") (pintype "passive"))
    )
    (net (code "56") (name "/ETXEN") (class "Default")
      (node (ref "DD1") (pin "C11") (pinfunction "PA13/ETXEN/UART1_RX/KP_OUT5_C11") (pintype "passive"))
      (node (ref "DD2") (pin "2") (pinfunction "TXEN_2") (pintype "passive"))
    )
    (net (code "57") (name "/FBIN") (class "Default")
      (node (ref "C28") (pin "2") (pintype "passive"))
      (node (ref "DD2") (pin "8") (pinfunction "PWFBIN_8") (pintype "passive"))
      (node (ref "L2") (pin "2") (pinfunction "2_2") (pintype "passive"))
    )
    (net (code "58") (name "/FBOUT") (class "Default")
      (node (ref "C18") (pin "1") (pintype "passive"))
      (node (ref "C24") (pin "2") (pintype "passive"))
      (node (ref "C26") (pin "2") (pintype "passive"))
      (node (ref "C27") (pin "2") (pintype "passive"))
      (node (ref "DD2") (pin "32") (pinfunction "PWFBOUT_32") (pintype "passive"))
      (node (ref "L2") (pin "1") (pinfunction "1_1") (pintype "passive"))
      (node (ref "XS1") (pin "4") (pintype "passive"))
      (node (ref "XS1") (pin "5") (pintype "passive"))
    )
    (net (code "59") (name "/FMINL") (class "Default")
      (node (ref "DD1") (pin "W16") (pinfunction "FMINL_W16") (pintype "passive"))
      (node (ref "XP10") (pin "14") (pinfunction "14_14") (pintype "passive"))
    )
    (net (code "60") (name "/FMINR") (class "Default")
      (node (ref "DD1") (pin "V16") (pinfunction "FMINR_V16") (pintype "passive"))
      (node (ref "XP10") (pin "16") (pinfunction "16_16") (pintype "passive"))
    )
    (net (code "61") (name "/HCEC") (class "Default")
      (node (ref "DD1") (pin "R17") (pinfunction "HCEC_R17") (pintype "passive"))
      (node (ref "VD11") (pin "3") (pinfunction "3_3") (pintype "passive"))
      (node (ref "XP5") (pin "13") (pinfunction "13_13") (pintype "passive"))
    )
    (net (code "62") (name "/HHPD") (class "Default")
      (node (ref "C143") (pin "2") (pintype "passive"))
      (node (ref "DD1") (pin "T17") (pinfunction "HHPD_T17") (pintype "passive"))
      (node (ref "R14") (pin "2") (pintype "passive"))
    )
    (net (code "63") (name "/HPCOM") (class "Default")
      (node (ref "DD1") (pin "V13") (pinfunction "HPCOMFB_V13") (pintype "passive"))
      (node (ref "DD1") (pin "W13") (pinfunction "HPCOM_W13") (pintype "passive"))
      (node (ref "R50") (pin "2") (pintype "passive"))
      (node (ref "VD14") (pin "3") (pinfunction "3_3") (pintype "passive"))
      (node (ref "XP1") (pin "2") (pinfunction "2_2") (pintype "passive"))
      (node (ref "XP1") (pin "5") (pinfunction "5_5") (pintype "passive"))
    )
    (net (code "64") (name "/HPD") (class "Default")
      (node (ref "R14") (pin "1") (pintype "passive"))
      (node (ref "R71") (pin "2") (pintype "passive"))
      (node (ref "VD10") (pin "3") (pinfunction "3_3") (pintype "passive"))
      (node (ref "XP5") (pin "19") (pinfunction "19_19") (pintype "passive"))
    )
    (net (code "65") (name "/HPL") (class "Default")
      (node (ref "DD1") (pin "Y13") (pinfunction "HPOUTL_Y13") (pintype "passive"))
      (node (ref "R51") (pin "2") (pintype "passive"))
      (node (ref "VD13") (pin "3") (pinfunction "3_3") (pintype "passive"))
      (node (ref "XP1") (pin "4") (pinfunction "4_4") (pintype "passive"))
    )
    (net (code "66") (name "/HPR") (class "Default")
      (node (ref "DD1") (pin "Y14") (pinfunction "HPOUTR_Y14") (pintype "passive"))
      (node (ref "R52") (pin "2") (pintype "passive"))
      (node (ref "VD12") (pin "3") (pinfunction "3_3") (pintype "passive"))
      (node (ref "XP1") (pin "3") (pinfunction "3_3") (pintype "passive"))
    )
    (net (code "67") (name "/HSCL") (class "Default")
      (node (ref "DD1") (pin "R18") (pinfunction "HSCL_R18") (pintype "passive"))
      (node (ref "R68") (pin "1") (pintype "passive"))
      (node (ref "VD8") (pin "3") (pinfunction "3_3") (pintype "passive"))
      (node (ref "XP5") (pin "15") (pinfunction "15_15") (pintype "passive"))
    )
    (net (code "68") (name "/HSDA") (class "Default")
      (node (ref "DD1") (pin "T18") (pinfunction "HSDA_T18") (pintype "passive"))
      (node (ref "R70") (pin "1") (pintype "passive"))
      (node (ref "VD9") (pin "3") (pinfunction "3_3") (pintype "passive"))
      (node (ref "XP5") (pin "16") (pinfunction "16_16") (pintype "passive"))
    )
    (net (code "69") (name "/HTX0_N") (class "Default")
      (node (ref "DD1") (pin "R19") (pinfunction "HTX0N_R19") (pintype "passive"))
      (node (ref "VD2") (pin "2") (pinfunction "IN2_2") (pintype "passive"))
      (node (ref "XP5") (pin "9") (pinfunction "9_9") (pintype "passive"))
    )
    (net (code "70") (name "/HTX0_P") (class "Default")
      (node (ref "DD1") (pin "R20") (pinfunction "HTX0P_R20") (pintype "passive"))
      (node (ref "VD2") (pin "1") (pinfunction "IN1_1") (pintype "passive"))
      (node (ref "XP5") (pin "7") (pinfunction "7_7") (pintype "passive"))
    )
    (net (code "71") (name "/HTX1_N") (class "Default")
      (node (ref "DD1") (pin "P19") (pinfunction "HTX1N_P19") (pintype "passive"))
      (node (ref "VD1") (pin "5") (pinfunction "IN4_5") (pintype "passive"))
      (node (ref "XP5") (pin "6") (pinfunction "6_6") (pintype "passive"))
    )
    (net (code "72") (name "/HTX1_P") (class "Default")
      (node (ref "DD1") (pin "P20") (pinfunction "HTX1P_P20") (pintype "passive"))
      (node (ref "VD1") (pin "4") (pinfunction "IN3_4") (pintype "passive"))
      (node (ref "XP5") (pin "4") (pinfunction "4_4") (pintype "passive"))
    )
    (net (code "73") (name "/HTX2_N") (class "Default")
      (node (ref "DD1") (pin "N19") (pinfunction "HTX2N_N19") (pintype "passive"))
      (node (ref "VD1") (pin "2") (pinfunction "IN2_2") (pintype "passive"))
      (node (ref "XP5") (pin "3") (pinfunction "3_3") (pintype "passive"))
    )
    (net (code "74") (name "/HTX2_P") (class "Default")
      (node (ref "DD1") (pin "N20") (pinfunction "HTX2P_N20") (pintype "passive"))
      (node (ref "VD1") (pin "1") (pinfunction "IN1_1") (pintype "passive"))
      (node (ref "XP5") (pin "1") (pinfunction "1_1") (pintype "passive"))
    )
    (net (code "75") (name "/HTXC_N") (class "Default")
      (node (ref "DD1") (pin "T19") (pinfunction "HTXCN_T19") (pintype "passive"))
      (node (ref "VD2") (pin "5") (pinfunction "IN4_5") (pintype "passive"))
      (node (ref "XP5") (pin "12") (pinfunction "12_12") (pintype "passive"))
    )
    (net (code "76") (name "/HTXC_P") (class "Default")
      (node (ref "DD1") (pin "T20") (pinfunction "HTXCP_T20") (pintype "passive"))
      (node (ref "VD2") (pin "4") (pinfunction "IN3_4") (pintype "passive"))
      (node (ref "XP5") (pin "10") (pinfunction "10_10") (pintype "passive"))
    )
    (net (code "77") (name "/JTAG_SEL0_N") (class "Default")
      (node (ref "DD1") (pin "M20") (pinfunction "JTAG_SEL0_N_M20") (pintype "passive"))
      (node (ref "R43") (pin "2") (pintype "passive"))
    )
    (net (code "78") (name "/JTAG_SEL1_N") (class "Default")
      (node (ref "DD1") (pin "M19") (pinfunction "JTAG_SEL1_N_M19") (pintype "passive"))
      (node (ref "R44") (pin "2") (pintype "passive"))
    )
    (net (code "79") (name "/LED0") (class "Default")
      (node (ref "DD1") (pin "A20") (pinfunction "PD15/LCD_D15/ERXERR_A20") (pintype "passive"))
      (node (ref "R73") (pin "2") (pintype "passive"))
    )
    (net (code "80") (name "/LINEINL") (class "Default")
      (node (ref "C80") (pin "2") (pintype "passive"))
      (node (ref "DD1") (pin "U17") (pinfunction "LINEINL_U17") (pintype "passive"))
    )
    (net (code "81") (name "/LINEINR") (class "Default")
      (node (ref "C78") (pin "2") (pintype "passive"))
      (node (ref "DD1") (pin "V18") (pinfunction "LINEINR_V18") (pintype "passive"))
    )
    (net (code "82") (name "/LRADC0") (class "Default")
      (node (ref "DD1") (pin "Y17") (pinfunction "LRADC0_Y17") (pintype "passive"))
      (node (ref "XP10") (pin "13") (pinfunction "13_13") (pintype "passive"))
    )
    (net (code "83") (name "/LRADC1") (class "Default")
      (node (ref "DD1") (pin "Y18") (pinfunction "LRADC1_Y18") (pintype "passive"))
      (node (ref "XP10") (pin "11") (pinfunction "11_11") (pintype "passive"))
    )
    (net (code "84") (name "/MICIN1") (class "Default")
      (node (ref "C87") (pin "1") (pintype "passive"))
      (node (ref "DD1") (pin "Y15") (pinfunction "MICIN1_Y15") (pintype "passive"))
      (node (ref "R60") (pin "2") (pintype "passive"))
    )
    (net (code "85") (name "/MICIN2") (class "Default")
      (node (ref "C88") (pin "1") (pintype "passive"))
      (node (ref "DD1") (pin "W15") (pinfunction "MICIN2_W15") (pintype "passive"))
      (node (ref "R61") (pin "2") (pintype "passive"))
    )
    (net (code "86") (name "/MIC_IN_1") (class "Default")
      (node (ref "C87") (pin "2") (pintype "passive"))
      (node (ref "R62") (pin "2") (pintype "passive"))
      (node (ref "XP10") (pin "10") (pinfunction "10_10") (pintype "passive"))
    )
    (net (code "87") (name "/MIC_IN_2") (class "Default")
      (node (ref "C88") (pin "2") (pintype "passive"))
      (node (ref "XP10") (pin "9") (pinfunction "9_9") (pintype "passive"))
    )
    (net (code "88") (name "/ODT0") (class "Default")
      (node (ref "DD1") (pin "V11") (pinfunction "SODT0/DDR2_A12/DDR3_ODT0_V11") (pintype "passive"))
      (node (ref "DD3") (pin "G1") (pinfunction "ODT_G1") (pintype "passive"))
      (node (ref "DD6") (pin "G1") (pinfunction "ODT_G1") (pintype "passive"))
    )
    (net (code "89") (name "/ODT1") (class "Default")
      (node (ref "DD1") (pin "M4") (pinfunction "SODT1/DDR2_ODT1/DDR3_ODT1_M4") (pintype "passive"))
      (node (ref "DD3") (pin "F1") (pinfunction "NC/ODT1_F1") (pintype "passive"))
      (node (ref "DD6") (pin "F1") (pinfunction "NC/ODT1_F1") (pintype "passive"))
    )
    (net (code "90") (name "/PB0{slash}TWI0_SCK") (class "Default")
      (node (ref "DD1") (pin "L20") (pinfunction "PB0/TWI0_SCK_L20") (pintype "passive"))
      (node (ref "DD7") (pin "6") (pinfunction "SCL_6") (pintype "passive"))
      (node (ref "R76") (pin "1") (pintype "passive"))
      (node (ref "XP10") (pin "22") (pinfunction "22_22") (pintype "passive"))
    )
    (net (code "91") (name "/PB1{slash}TWI0_SDA") (class "Default")
      (node (ref "DD1") (pin "L19") (pinfunction "PB1/TWI0_SDA_L19") (pintype "passive"))
      (node (ref "DD7") (pin "5") (pinfunction "SDA_5") (pintype "passive"))
      (node (ref "R78") (pin "1") (pintype "passive"))
      (node (ref "XP10") (pin "23") (pinfunction "23_23") (pintype "passive"))
    )
    (net (code "92") (name "/PB2{slash}PWM0") (class "Default")
      (node (ref "DD1") (pin "K20") (pinfunction "PB2/PWM0/EINT16_K20") (pintype "passive"))
      (node (ref "XP10") (pin "24") (pinfunction "24_24") (pintype "passive"))
    )
    (net (code "93") (name "/PB3{slash}IR_TX") (class "Default")
      (node (ref "DD1") (pin "A14") (pinfunction "PB3/IR_TX/EINT17_A14") (pintype "passive"))
      (node (ref "XP11") (pin "19") (pinfunction "19_19") (pintype "passive"))
    )
    (net (code "94") (name "/PB4{slash}IR_RX") (class "Default")
      (node (ref "DD1") (pin "K19") (pinfunction "PB4/IR_RX/EINT18_K19") (pintype "passive"))
      (node (ref "XP11") (pin "21") (pinfunction "21_21") (pintype "passive"))
    )
    (net (code "95") (name "/PB5{slash}I2S_MCLK") (class "Default")
      (node (ref "DD1") (pin "D2") (pinfunction "PB5/I2S_MCLK/EINT19_D2") (pintype "passive"))
      (node (ref "XP14") (pin "9") (pinfunction "9_9") (pintype "passive"))
    )
    (net (code "96") (name "/PB6{slash}I2S_BCLK") (class "Default")
      (node (ref "DD1") (pin "E1") (pinfunction "PB6/I2S_BCLK/EINT20_E1") (pintype "passive"))
      (node (ref "XP14") (pin "7") (pinfunction "7_7") (pintype "passive"))
    )
    (net (code "97") (name "/PB7{slash}I2S_LRCK") (class "Default")
      (node (ref "DD1") (pin "E2") (pinfunction "PB7/I2S_LRCK/EINT21_E2") (pintype "passive"))
      (node (ref "XP14") (pin "10") (pinfunction "10_10") (pintype "passive"))
    )
    (net (code "98") (name "/PB8{slash}I2S_DO") (class "Default")
      (node (ref "DD1") (pin "F1") (pinfunction "PB8/I2S_DO/EINT22_F1") (pintype "passive"))
      (node (ref "XP14") (pin "5") (pinfunction "5_5") (pintype "passive"))
    )
    (net (code "99") (name "/PB9{slash}I2S_DI") (class "Default")
      (node (ref "DD1") (pin "F2") (pinfunction "PB9/I2S_DI/EINT23_F2") (pintype "passive"))
      (node (ref "XP14") (pin "8") (pinfunction "8_8") (pintype "passive"))
    )
    (net (code "100") (name "/PB10{slash}SPI2_CS1") (class "Default")
      (node (ref "DD1") (pin "D3") (pinfunction "PB10/SPI2_CS1/EINT24_D3") (pintype "passive"))
      (node (ref "XP14") (pin "6") (pinfunction "6_6") (pintype "passive"))
    )
    (net (code "101") (name "/PB11{slash}SPI2_CS0{slash}JTAG_MS0") (class "Default")
      (node (ref "DD1") (pin "E3") (pinfunction "PB11/SPI2_CS0/JTAG_MS0/EINT25_E3") (pintype "passive"))
      (node (ref "XP7") (pin "10") (pinfunction "10_10") (pintype "passive"))
    )
    (net (code "102") (name "/PB12{slash}SPI2_CLK{slash}JTAG_CK0") (class "Default")
      (node (ref "DD1") (pin "E4") (pinfunction "PB12/SPI2_CLK/JTAG_CK0/EINT26_E4") (pintype "passive"))
      (node (ref "XP7") (pin "9") (pinfunction "9_9") (pintype "passive"))
    )
    (net (code "103") (name "/PB13{slash}SPI2_MOSI{slash}JTAG_DO0") (class "Default")
      (node (ref "DD1") (pin "F3") (pinfunction "PB13/SPI2_MOSI/JTAG_DO0/EINT27_F3") (pintype "passive"))
      (node (ref "XP7") (pin "8") (pinfunction "8_8") (pintype "passive"))
    )
    (net (code "104") (name "/PB14{slash}SPI2_MISO{slash}JTAG_DI0") (class "Default")
      (node (ref "DD1") (pin "F4") (pinfunction "PB14/SPI2_MISO/JTAG_DI0/EINT28_F4") (pintype "passive"))
      (node (ref "XP7") (pin "7") (pinfunction "7_7") (pintype "passive"))
    )
    (net (code "105") (name "/PB15{slash}TWI1_SCK") (class "Default")
      (node (ref "DD1") (pin "J20") (pinfunction "PB15/TWI1_SCK_J20") (pintype "passive"))
      (node (ref "R66") (pin "2") (pintype "passive"))
      (node (ref "XP10") (pin "25") (pinfunction "25_25") (pintype "passive"))
    )
    (net (code "106") (name "/PB16{slash}TWI1_SDA") (class "Default")
      (node (ref "DD1") (pin "J19") (pinfunction "PB16/TWI1_SDA_J19") (pintype "passive"))
      (node (ref "R65") (pin "1") (pintype "passive"))
      (node (ref "XP10") (pin "26") (pinfunction "26_26") (pintype "passive"))
    )
    (net (code "107") (name "/PB17{slash}TWI2_SCK") (class "Default")
      (node (ref "DD1") (pin "A7") (pinfunction "PB17/TWI2_SCK_A7") (pintype "passive"))
      (node (ref "R69") (pin "1") (pintype "passive"))
      (node (ref "XP7") (pin "5") (pinfunction "5_5") (pintype "passive"))
    )
    (net (code "108") (name "/PB18{slash}TWI2_SDA") (class "Default")
      (node (ref "DD1") (pin "B8") (pinfunction "PB18/TWI2_SDA_B8") (pintype "passive"))
      (node (ref "R72") (pin "2") (pintype "passive"))
      (node (ref "XP7") (pin "6") (pinfunction "6_6") (pintype "passive"))
    )
    (net (code "109") (name "/PB19{slash}UART0_TX") (class "Default")
      (node (ref "DD1") (pin "G3") (pinfunction "PB19/UART0_TX/EINT29_G3") (pintype "passive"))
      (node (ref "R15") (pin "2") (pintype "passive"))
    )
    (net (code "110") (name "/PB20{slash}UART0_RX") (class "Default")
      (node (ref "DD1") (pin "G4") (pinfunction "PB20/UART0_RX/EINT30_G4") (pintype "passive"))
      (node (ref "R19") (pin "2") (pintype "passive"))
    )
    (net (code "111") (name "/PC0{slash}SPI0_MOSI") (class "Default")
      (node (ref "DD1") (pin "D1") (pinfunction "PC0/NWE/SPI0_MOSI_D1") (pintype "passive"))
      (node (ref "XP11") (pin "8") (pinfunction "8_8") (pintype "passive"))
    )
    (net (code "112") (name "/PC1{slash}SPI0_MISO") (class "Default")
      (node (ref "DD1") (pin "C3") (pinfunction "PC1/NALE/SPI0_MISO_C3") (pintype "passive"))
      (node (ref "XP11") (pin "9") (pinfunction "9_9") (pintype "passive"))
    )
    (net (code "113") (name "/PC2{slash}SPI0_CLK") (class "Default")
      (node (ref "DD1") (pin "C2") (pinfunction "PC2/NCLE/SPI0_CLK_C2") (pintype "passive"))
      (node (ref "XP11") (pin "10") (pinfunction "10_10") (pintype "passive"))
    )
    (net (code "114") (name "/PC3{slash}SPI0_CS0") (class "Default")
      (node (ref "DD1") (pin "C1") (pinfunction "PC3/NCE1/SPI0_CS0_C1") (pintype "passive"))
      (node (ref "XP11") (pin "7") (pinfunction "7_7") (pintype "passive"))
    )
    (net (code "115") (name "/PC5{slash}SDC2_SDET#") (class "Default")
      (node (ref "DD1") (pin "B1") (pinfunction "PC5/NRE_B1") (pintype "passive"))
      (node (ref "XP11") (pin "11") (pinfunction "11_11") (pintype "passive"))
    )
    (net (code "116") (name "/PC6{slash}SDC2_CMD") (class "Default")
      (node (ref "DD1") (pin "A1") (pinfunction "PC6/NRB0/SDC2_CMD_A1") (pintype "passive"))
      (node (ref "XP11") (pin "12") (pinfunction "12_12") (pintype "passive"))
    )
    (net (code "117") (name "/PC7{slash}SDC2_CLK") (class "Default")
      (node (ref "DD1") (pin "A2") (pinfunction "PC7/NRB1/SDC2_CLK_A2") (pintype "passive"))
      (node (ref "XP11") (pin "14") (pinfunction "14_14") (pintype "passive"))
    )
    (net (code "118") (name "/PC8{slash}SDC2_D0") (class "Default")
      (node (ref "DD1") (pin "B3") (pinfunction "PC8/NDQ0/SDC2_D0_B3") (pintype "passive"))
      (node (ref "XP11") (pin "15") (pinfunction "15_15") (pintype "passive"))
    )
    (net (code "119") (name "/PC9{slash}SDC2_D1") (class "Default")
      (node (ref "DD1") (pin "A3") (pinfunction "PC9/NDQ1/SDC2_D1_A3") (pintype "passive"))
      (node (ref "XP11") (pin "16") (pinfunction "16_16") (pintype "passive"))
    )
    (net (code "120") (name "/PC10{slash}SDC2_D2") (class "Default")
      (node (ref "DD1") (pin "C4") (pinfunction "PC10/NDQ2/SDC2_D2_C4") (pintype "passive"))
      (node (ref "XP11") (pin "13") (pinfunction "13_13") (pintype "passive"))
    )
    (net (code "121") (name "/PC11{slash}SDC2_D3") (class "Default")
      (node (ref "DD1") (pin "B4") (pinfunction "PC11/NDQ3/SDC2_D3_B4") (pintype "passive"))
      (node (ref "XP11") (pin "17") (pinfunction "17_17") (pintype "passive"))
    )
    (net (code "122") (name "/PC16{slash}UART3_TX") (class "Default")
      (node (ref "DD1") (pin "A5") (pinfunction "PC16/NWP/UART3_TX_A5") (pintype "passive"))
      (node (ref "XP14") (pin "3") (pinfunction "3_3") (pintype "passive"))
    )
    (net (code "123") (name "/PC17UART3_RX") (class "Default")
      (node (ref "DD1") (pin "B6") (pinfunction "PC17/NCE2/UART3_RX_B6") (pintype "passive"))
      (node (ref "XP14") (pin "4") (pinfunction "4_4") (pintype "passive"))
    )
    (net (code "124") (name "/PC18{slash}UART2_TX{slash}UART3_CTS") (class "Default")
      (node (ref "DD1") (pin "A6") (pinfunction "PC18/NCE3/UART2_TX/UART3_CTS_A6") (pintype "passive"))
      (node (ref "R27") (pin "2") (pintype "passive"))
    )
    (net (code "125") (name "/PC19{slash}UART2_RX{slash}UART3_RTS") (class "Default")
      (node (ref "DD1") (pin "B7") (pinfunction "PC19/NDQS/UART2_RX/UART3_RTS_B7") (pintype "passive"))
      (node (ref "R26") (pin "1") (pintype "passive"))
    )
    (net (code "126") (name "/PD2{slash}UART2_TX") (class "Default")
      (node (ref "DD1") (pin "B15") (pinfunction "PD2/LCD_D2/UART2_TX_B15") (pintype "passive"))
      (node (ref "R55") (pin "2") (pintype "passive"))
    )
    (net (code "127") (name "/PD3{slash}UART2_RX") (class "Default")
      (node (ref "DD1") (pin "A15") (pinfunction "PD3/LCD_D3/UART2_RX_A15") (pintype "passive"))
      (node (ref "R83") (pin "2") (pintype "passive"))
    )
    (net (code "128") (name "/PD4{slash}UART2_CTS") (class "Default")
      (node (ref "DD1") (pin "D16") (pinfunction "PD4/LCD_D4/UART2_CTS_D16") (pintype "passive"))
      (node (ref "XP11") (pin "28") (pinfunction "28_28") (pintype "passive"))
    )
    (net (code "129") (name "/PD5{slash}UART2_RTS") (class "Default")
      (node (ref "DD1") (pin "C16") (pinfunction "PD5/LCD_D5/UART2_RTS_C16") (pintype "passive"))
      (node (ref "XP11") (pin "26") (pinfunction "26_26") (pintype "passive"))
    )
    (net (code "130") (name "/PE0{slash}TS_CLK{slash}CSI_PCLK{slash}SPI2_CS0") (class "Default")
      (node (ref "DD1") (pin "H20") (pinfunction "PE0/TS_CLK/CSI_PCLK/SPI2_CS0/EINT14_H20") (pintype "passive"))
      (node (ref "XP10") (pin "27") (pinfunction "27_27") (pintype "passive"))
    )
    (net (code "131") (name "/PE1{slash}TS_ERR{slash}CSI_MCLK{slash}SPI2_CLK") (class "Default")
      (node (ref "DD1") (pin "H19") (pinfunction "PE1/TS_ERR/CSI_MCLK/SPI2_CLK/EINT15_H19") (pintype "passive"))
      (node (ref "XP10") (pin "28") (pinfunction "28_28") (pintype "passive"))
    )
    (net (code "132") (name "/PE2{slash}TS_SYNC{slash}CSI_HSYNC{slash}SPI2_MOSI") (class "Default")
      (node (ref "DD1") (pin "G20") (pinfunction "PE2/TS_SYNC/CSI_HSYNC/SPI2_MOSI_G20") (pintype "passive"))
      (node (ref "XP10") (pin "29") (pinfunction "29_29") (pintype "passive"))
    )
    (net (code "133") (name "/PE3{slash}TS_DVLD{slash}CSI_VSYNC{slash}SPI2_MISO") (class "Default")
      (node (ref "DD1") (pin "G19") (pinfunction "PE3/TS_DVLD/CSI_VSYNC/SPI2_MISO_G19") (pintype "passive"))
      (node (ref "XP10") (pin "30") (pinfunction "30_30") (pintype "passive"))
    )
    (net (code "134") (name "/PE4{slash}TS_D0{slash}CSI_D0{slash}SDC2_DO") (class "Default")
      (node (ref "DD1") (pin "F20") (pinfunction "PE4/TS_D0/CSI_D0/SDC2_DO_F20") (pintype "passive"))
      (node (ref "XP10") (pin "31") (pinfunction "31_31") (pintype "passive"))
    )
    (net (code "135") (name "/PE5{slash}TS_D1{slash}CSI_D1{slash}SDC2_D1") (class "Default")
      (node (ref "DD1") (pin "F19") (pinfunction "PE5/TS_D1/CSI_D1/SDC2_D1_F19") (pintype "passive"))
      (node (ref "XP10") (pin "32") (pinfunction "32_32") (pintype "passive"))
    )
    (net (code "136") (name "/PE6{slash}TS_D2{slash}CSI_D2{slash}SDC2_D2") (class "Default")
      (node (ref "DD1") (pin "E20") (pinfunction "PE6/TS_D2/CSI_D2/SDC2_D2_E20") (pintype "passive"))
      (node (ref "XP10") (pin "33") (pinfunction "33_33") (pintype "passive"))
    )
    (net (code "137") (name "/PE7{slash}TS_D3{slash}CSI_D3{slash}SDC2_D3") (class "Default")
      (node (ref "DD1") (pin "E19") (pinfunction "PE7/TS_D3/CSI_D3/SDC2_D3_E19") (pintype "passive"))
      (node (ref "XP10") (pin "34") (pinfunction "34_34") (pintype "passive"))
    )
    (net (code "138") (name "/PE8{slash}TS_D4{slash}CSI_D4{slash}SDC2_CMD") (class "Default")
      (node (ref "DD1") (pin "D20") (pinfunction "PE8/TS_D4/CSI_D4/SDC2_CMD_D20") (pintype "passive"))
      (node (ref "XP10") (pin "35") (pinfunction "35_35") (pintype "passive"))
    )
    (net (code "139") (name "/PE9{slash}TS_D5{slash}CSI_D5{slash}SDC2_CLK") (class "Default")
      (node (ref "DD1") (pin "D19") (pinfunction "PE9/TS_D5/CSI_D5/SDC2_CLK_D19") (pintype "passive"))
      (node (ref "XP10") (pin "36") (pinfunction "36_36") (pintype "passive"))
    )
    (net (code "140") (name "/PE10{slash}TS_D6{slash}CSI_D6") (class "Default")
      (node (ref "DD1") (pin "C20") (pinfunction "PE10/TS_D6/CSI_D6/UART1_TX_C20") (pintype "passive"))
      (node (ref "XP10") (pin "37") (pinfunction "37_37") (pintype "passive"))
    )
    (net (code "141") (name "/PE11{slash}TS_D7{slash}CSI_D7") (class "Default")
      (node (ref "DD1") (pin "C19") (pinfunction "PE11/TS_D7/CSI_D7/UART1_RX_C19") (pintype "passive"))
      (node (ref "XP10") (pin "38") (pinfunction "38_38") (pintype "passive"))
    )
    (net (code "142") (name "/PG3{slash}UART1_TX") (class "Default")
      (node (ref "DD1") (pin "A11") (pinfunction "PG3/SDC1_CMD/UART1_TX/EINT3_A11") (pintype "passive"))
      (node (ref "R47") (pin "1") (pintype "passive"))
    )
    (net (code "143") (name "/PG4{slash}UART1_RX") (class "Default")
      (node (ref "DD1") (pin "B12") (pinfunction "PG4/SDC1_CLK/UART1_RX/EINT4_B12") (pintype "passive"))
      (node (ref "R54") (pin "1") (pintype "passive"))
    )
    (net (code "144") (name "/PG9{slash}UART3_TX") (class "Default")
      (node (ref "DD1") (pin "G1") (pinfunction "PG9/SPI1_CS0/UART3_TX/EINT9_G1") (pintype "passive"))
      (node (ref "R41") (pin "1") (pintype "passive"))
    )
    (net (code "145") (name "/PG10{slash}UART3_RX") (class "Default")
      (node (ref "DD1") (pin "G2") (pinfunction "PG10/SPI1_CLK/UART3_RX/EINT10_G2") (pintype "passive"))
      (node (ref "R42") (pin "1") (pintype "passive"))
    )
    (net (code "146") (name "/PG_5V") (class "Default")
      (node (ref "DD11") (pin "7") (pinfunction "PG_7") (pintype "passive"))
    )
    (net (code "147") (name "/PHYAD0{slash}LED0") (class "Default")
      (node (ref "DD2") (pin "9") (pinfunction "LED0/PHYAD0_9") (pintype "passive"))
      (node (ref "R2") (pin "1") (pintype "passive"))
      (node (ref "R4") (pin "1") (pintype "passive"))
    )
    (net (code "148") (name "/PHYAD1{slash}LED1") (class "Default")
      (node (ref "DD2") (pin "10") (pinfunction "LED1/PHYAD1_10") (pintype "passive"))
      (node (ref "R5") (pin "1") (pintype "passive"))
    )
    (net (code "149") (name "/PHYAD2{slash}LED2") (class "Default")
      (node (ref "DD2") (pin "12") (pinfunction "LED2/PHYAD2_12") (pintype "passive"))
      (node (ref "R6") (pin "1") (pintype "passive"))
    )
    (net (code "150") (name "/PHYAD3{slash}LED3") (class "Default")
      (node (ref "DD2") (pin "13") (pinfunction "LED3/PHYAD3_13") (pintype "passive"))
      (node (ref "R1") (pin "1") (pintype "passive"))
      (node (ref "R8") (pin "1") (pintype "passive"))
    )
    (net (code "151") (name "/PHYAD4{slash}LED4") (class "Default")
      (node (ref "DD2") (pin "15") (pinfunction "LED4/PHYAD4_15") (pintype "passive"))
      (node (ref "R11") (pin "1") (pintype "passive"))
    )
    (net (code "152") (name "/RAS") (class "Default")
      (node (ref "DD1") (pin "U4") (pinfunction "SRAS/DDR2_A11/DDR3_RAS_U4") (pintype "passive"))
      (node (ref "DD3") (pin "F3") (pinfunction "#RAS_F3") (pintype "passive"))
      (node (ref "DD6") (pin "F3") (pinfunction "#RAS_F3") (pintype "passive"))
    )
    (net (code "153") (name "/RECOVERY") (class "Default")
      (node (ref "BT1") (pin "1") (pinfunction "1_1") (pintype "passive"))
      (node (ref "DD1") (pin "B20") (pinfunction "PD17/LCD_D17_B20") (pintype "passive"))
      (node (ref "R74") (pin "1") (pintype "passive"))
    )
    (net (code "154") (name "/RESET_N") (class "Default")
      (node (ref "DD1") (pin "A8") (pinfunction "RESET_N_A8") (pintype "passive"))
      (node (ref "R67") (pin "2") (pintype "passive"))
      (node (ref "XP14") (pin "1") (pinfunction "1_1") (pintype "passive"))
    )
    (net (code "155") (name "/RTC_CLK_OUT") (class "Default")
      (node (ref "DD7") (pin "7") (pinfunction "CLKOUT_7") (pintype "passive"))
      (node (ref "R93") (pin "2") (pintype "passive"))
      (node (ref "XP10") (pin "39") (pinfunction "39_39") (pintype "passive"))
    )
    (net (code "156") (name "/RTC_~{INT}") (class "Default")
      (node (ref "DD7") (pin "3") (pinfunction "INT_3") (pintype "passive"))
      (node (ref "R75") (pin "2") (pintype "passive"))
      (node (ref "XP10") (pin "40") (pinfunction "40_40") (pintype "passive"))
    )
    (net (code "157") (name "/SA0") (class "Default")
      (node (ref "DD1") (pin "V7") (pinfunction "SA0/DDR2_BA1/DDR3_A0_V7") (pintype "passive"))
      (node (ref "DD3") (pin "K3") (pinfunction "A0_K3") (pintype "passive"))
      (node (ref "DD6") (pin "K3") (pinfunction "A0_K3") (pintype "passive"))
    )
    (net (code "158") (name "/SA1") (class "Default")
      (node (ref "DD1") (pin "R4") (pinfunction "SA1/DDR2_A2/DDR3_A1_R4") (pintype "passive"))
      (node (ref "DD3") (pin "L7") (pinfunction "A1_L7") (pintype "passive"))
      (node (ref "DD6") (pin "L7") (pinfunction "A1_L7") (pintype "passive"))
    )
    (net (code "159") (name "/SA2") (class "Default")
      (node (ref "DD1") (pin "U8") (pinfunction "SA2/DDR2_A1/DDR3_A2_U8") (pintype "passive"))
      (node (ref "DD3") (pin "L3") (pinfunction "A2_L3") (pintype "passive"))
      (node (ref "DD6") (pin "L3") (pinfunction "A2_L3") (pintype "passive"))
    )
    (net (code "160") (name "/SA3") (class "Default")
      (node (ref "DD1") (pin "U7") (pinfunction "SA3/DDR2_BA0/DDR3_A3_U7") (pintype "passive"))
      (node (ref "DD3") (pin "K2") (pinfunction "A3_K2") (pintype "passive"))
      (node (ref "DD6") (pin "K2") (pinfunction "A3_K2") (pintype "passive"))
    )
    (net (code "161") (name "/SA4") (class "Default")
      (node (ref "DD1") (pin "P3") (pinfunction "SA4/DDR2_A0/DDR3_A4_P3") (pintype "passive"))
      (node (ref "DD3") (pin "L8") (pinfunction "A4_L8") (pintype "passive"))
      (node (ref "DD6") (pin "L8") (pinfunction "A4_L8") (pintype "passive"))
    )
    (net (code "162") (name "/SA5") (class "Default")
      (node (ref "DD1") (pin "V8") (pinfunction "SA5/DDR2_A10/DDR3_A5_V8") (pintype "passive"))
      (node (ref "DD3") (pin "L2") (pinfunction "A5_L2") (pintype "passive"))
      (node (ref "DD6") (pin "L2") (pinfunction "A5_L2") (pintype "passive"))
    )
    (net (code "163") (name "/SA6") (class "Default")
      (node (ref "DD1") (pin "R3") (pinfunction "SA6/DDR2_A4/DDR3_A6_R3") (pintype "passive"))
      (node (ref "DD3") (pin "M8") (pinfunction "A6_M8") (pintype "passive"))
      (node (ref "DD6") (pin "M8") (pinfunction "A6_M8") (pintype "passive"))
    )
    (net (code "164") (name "/SA7") (class "Default")
      (node (ref "DD1") (pin "V10") (pinfunction "SA7/DDR2_A7/DDR3_A7_V10") (pintype "passive"))
      (node (ref "DD3") (pin "M2") (pinfunction "A7_M2") (pintype "passive"))
      (node (ref "DD6") (pin "M2") (pinfunction "A7_M2") (pintype "passive"))
    )
    (net (code "165") (name "/SA8") (class "Default")
      (node (ref "DD1") (pin "T3") (pinfunction "SA8/DDR2_A6/DDR3_A8_T3") (pintype "passive"))
      (node (ref "DD3") (pin "N8") (pinfunction "A8_N8") (pintype "passive"))
      (node (ref "DD6") (pin "N8") (pinfunction "A8_N8") (pintype "passive"))
    )
    (net (code "166") (name "/SA9") (class "Default")
      (node (ref "DD1") (pin "V9") (pinfunction "SA9/DDR2_A3/DDR3_A9_V9") (pintype "passive"))
      (node (ref "DD3") (pin "M3") (pinfunction "A9_M3") (pintype "passive"))
      (node (ref "DD6") (pin "M3") (pinfunction "A9_M3") (pintype "passive"))
    )
    (net (code "167") (name "/SA10") (class "Default")
      (node (ref "DD1") (pin "M3") (pinfunction "SA10/DDR2_RAS/DDR3_A10_M3") (pintype "passive"))
      (node (ref "DD3") (pin "H7") (pinfunction "A10/AP_H7") (pintype "passive"))
      (node (ref "DD6") (pin "H7") (pinfunction "A10/AP_H7") (pintype "passive"))
    )
    (net (code "168") (name "/SA11") (class "Default")
      (node (ref "DD1") (pin "T4") (pinfunction "SA11/DDR2_A8/DDR3_A11_T4") (pintype "passive"))
      (node (ref "DD3") (pin "M7") (pinfunction "A11_M7") (pintype "passive"))
      (node (ref "DD6") (pin "M7") (pinfunction "A11_M7") (pintype "passive"))
    )
    (net (code "169") (name "/SA12") (class "Default")
      (node (ref "DD1") (pin "P4") (pinfunction "SA12/DDR2_CAS/DDR3_A12_P4") (pintype "passive"))
      (node (ref "DD3") (pin "K7") (pinfunction "A12/#BC_K7") (pintype "passive"))
      (node (ref "DD6") (pin "K7") (pinfunction "A12/#BC_K7") (pintype "passive"))
    )
    (net (code "170") (name "/SA13") (class "Default")
      (node (ref "DD1") (pin "U9") (pinfunction "SA13/DDR2_A5/DDR3_A13_U9") (pintype "passive"))
      (node (ref "DD3") (pin "N3") (pinfunction "A13_N3") (pintype "passive"))
      (node (ref "DD6") (pin "N3") (pinfunction "A13_N3") (pintype "passive"))
    )
    (net (code "171") (name "/SA14") (class "Default")
      (node (ref "DD1") (pin "U3") (pinfunction "SA14/DDR2_A14/DDR3_A14_U3") (pintype "passive"))
      (node (ref "DD3") (pin "N7") (pinfunction "A14_N7") (pintype "passive"))
      (node (ref "DD6") (pin "N7") (pinfunction "A14_N7") (pintype "passive"))
    )
    (net (code "172") (name "/SD0-CLK") (class "Default")
      (node (ref "DD1") (pin "K18") (pinfunction "PF2/SDC0_CLK/UART0_TX_K18") (pintype "passive"))
      (node (ref "XS2") (pin "5") (pinfunction "CLK_5") (pintype "input"))
    )
    (net (code "173") (name "/SD0-CMD") (class "Default")
      (node (ref "DD1") (pin "K17") (pinfunction "PF3/SDC0_CMD/JTAG_DO1_K17") (pintype "passive"))
      (node (ref "R38") (pin "1") (pintype "passive"))
      (node (ref "XS2") (pin "3") (pinfunction "CMD/MOSI_3") (pintype "bidirectional"))
    )
    (net (code "174") (name "/SD0-D0") (class "Default")
      (node (ref "DD1") (pin "L17") (pinfunction "PF1/SDC0_D0/JTAG_DI1_L17") (pintype "passive"))
      (node (ref "R37") (pin "1") (pintype "passive"))
      (node (ref "XS2") (pin "7") (pinfunction "DAT0/MISO_7") (pintype "bidirectional"))
    )
    (net (code "175") (name "/SD0-D1") (class "Default")
      (node (ref "DD1") (pin "L18") (pinfunction "PF0/SDC0_D1/JTAG_MS1_L18") (pintype "passive"))
      (node (ref "R36") (pin "1") (pintype "passive"))
      (node (ref "XS2") (pin "8") (pinfunction "DAT1_8") (pintype "bidirectional"))
    )
    (net (code "176") (name "/SD0-D2") (class "Default")
      (node (ref "DD1") (pin "J17") (pinfunction "PF5/SDC0_D2/JTAG_CK1_J17") (pintype "passive"))
      (node (ref "R40") (pin "1") (pintype "passive"))
      (node (ref "XS2") (pin "1") (pinfunction "DTA2_1") (pintype "bidirectional"))
    )
    (net (code "177") (name "/SD0-D3") (class "Default")
      (node (ref "DD1") (pin "J18") (pinfunction "PF4/SDC0_D3/UART0_RX_J18") (pintype "passive"))
      (node (ref "R39") (pin "1") (pintype "passive"))
      (node (ref "XS2") (pin "2") (pinfunction "DAT3/CS_2") (pintype "bidirectional"))
    )
    (net (code "178") (name "/SD0-DET#") (class "Default")
      (node (ref "DD1") (pin "A10") (pinfunction "PG1/GPS_SIGN/EINT1_A10") (pintype "passive"))
      (node (ref "R35") (pin "1") (pintype "passive"))
      (node (ref "XS2") (pin "9") (pinfunction "CD_9") (pintype "passive"))
    )
    (net (code "179") (name "/TPRX_N") (class "Default")
      (node (ref "DD2") (pin "30") (pinfunction "TPRX-_30") (pintype "passive"))
      (node (ref "R23") (pin "2") (pintype "passive"))
      (node (ref "XS1") (pin "6") (pintype "passive"))
    )
    (net (code "180") (name "/TPRX_P") (class "Default")
      (node (ref "DD2") (pin "31") (pinfunction "TPRX+_31") (pintype "passive"))
      (node (ref "R22") (pin "2") (pintype "passive"))
      (node (ref "XS1") (pin "3") (pintype "passive"))
    )
    (net (code "181") (name "/TPTX_N") (class "Default")
      (node (ref "DD2") (pin "33") (pinfunction "TPTX-_33") (pintype "passive"))
      (node (ref "R21") (pin "2") (pintype "passive"))
      (node (ref "XS1") (pin "2") (pintype "passive"))
    )
    (net (code "182") (name "/TPTX_P") (class "Default")
      (node (ref "DD2") (pin "34") (pinfunction "TPTX+_34") (pintype "passive"))
      (node (ref "R20") (pin "2") (pintype "passive"))
      (node (ref "XS1") (pin "1") (pintype "passive"))
    )
    (net (code "183") (name "/TPX1") (class "Default")
      (node (ref "DD1") (pin "Y20") (pinfunction "TPX1_Y20") (pintype "passive"))
      (node (ref "XP10") (pin "18") (pinfunction "18_18") (pintype "passive"))
    )
    (net (code "184") (name "/TPX2") (class "Default")
      (node (ref "DD1") (pin "Y19") (pinfunction "TPX2_Y19") (pintype "passive"))
      (node (ref "XP10") (pin "17") (pinfunction "17_17") (pintype "passive"))
    )
    (net (code "185") (name "/TPY1") (class "Default")
      (node (ref "DD1") (pin "W20") (pinfunction "TPY1_W20") (pintype "passive"))
      (node (ref "XP10") (pin "20") (pinfunction "20_20") (pintype "passive"))
    )
    (net (code "186") (name "/TPY2") (class "Default")
      (node (ref "DD1") (pin "W19") (pinfunction "TPY2_W19") (pintype "passive"))
      (node (ref "XP10") (pin "19") (pinfunction "19_19") (pintype "passive"))
    )
    (net (code "187") (name "/TVOUT") (class "Default")
      (node (ref "DD1") (pin "M18") (pinfunction "TVOUT_M18") (pintype "passive"))
      (node (ref "R64") (pin "1") (pintype "passive"))
      (node (ref "VD7") (pin "3") (pinfunction "3_3") (pintype "passive"))
    )
    (net (code "188") (name "/UART0_RX") (class "Default")
      (node (ref "R19") (pin "1") (pintype "passive"))
      (node (ref "XP11") (pin "3") (pinfunction "3_3") (pintype "passive"))
      (node (ref "XP9") (pin "3") (pinfunction "3_3") (pintype "passive"))
    )
    (net (code "189") (name "/UART0_TX") (class "Default")
      (node (ref "R15") (pin "1") (pintype "passive"))
      (node (ref "XP11") (pin "1") (pinfunction "1_1") (pintype "passive"))
      (node (ref "XP9") (pin "2") (pinfunction "2_2") (pintype "passive"))
    )
    (net (code "190") (name "/UART1_RX_") (class "Default")
      (node (ref "R54") (pin "2") (pintype "passive"))
      (node (ref "XP11") (pin "22") (pinfunction "22_22") (pintype "passive"))
    )
    (net (code "191") (name "/UART1_TX_") (class "Default")
      (node (ref "R47") (pin "2") (pintype "passive"))
      (node (ref "XP11") (pin "20") (pinfunction "20_20") (pintype "passive"))
    )
    (net (code "192") (name "/UART2_RX") (class "Default")
      (node (ref "R26") (pin "2") (pintype "passive"))
      (node (ref "XP7") (pin "4") (pinfunction "4_4") (pintype "passive"))
    )
    (net (code "193") (name "/UART2_RX_") (class "Default")
      (node (ref "R83") (pin "1") (pintype "passive"))
      (node (ref "XP11") (pin "25") (pinfunction "25_25") (pintype "passive"))
    )
    (net (code "194") (name "/UART2_TX") (class "Default")
      (node (ref "R27") (pin "1") (pintype "passive"))
      (node (ref "XP7") (pin "3") (pinfunction "3_3") (pintype "passive"))
    )
    (net (code "195") (name "/UART2_TX_") (class "Default")
      (node (ref "R55") (pin "1") (pintype "passive"))
      (node (ref "XP11") (pin "23") (pinfunction "23_23") (pintype "passive"))
    )
    (net (code "196") (name "/UART3_RX_") (class "Default")
      (node (ref "R42") (pin "2") (pintype "passive"))
      (node (ref "XP11") (pin "4") (pinfunction "4_4") (pintype "passive"))
    )
    (net (code "197") (name "/UART3_TX_") (class "Default")
      (node (ref "R41") (pin "2") (pintype "passive"))
      (node (ref "XP11") (pin "2") (pinfunction "2_2") (pintype "passive"))
    )
    (net (code "198") (name "/UBOOT_N") (class "Default")
      (node (ref "DD1") (pin "A9") (pinfunction "UBOOT_N_A9") (pintype "passive"))
      (node (ref "R32") (pin "1") (pintype "passive"))
    )
    (net (code "199") (name "/UD0_N") (class "Default")
      (node (ref "DD1") (pin "P18") (pinfunction "UDM0_P18") (pintype "passive"))
      (node (ref "XP4") (pin "D-") (pinfunction "D-_D-") (pintype "passive"))
    )
    (net (code "200") (name "/UD0_P") (class "Default")
      (node (ref "DD1") (pin "P17") (pinfunction "UDP0_P17") (pintype "passive"))
      (node (ref "XP4") (pin "D+") (pinfunction "D+_D+") (pintype "passive"))
    )
    (net (code "201") (name "/UD1_N") (class "Default")
      (node (ref "DD1") (pin "N18") (pinfunction "UDM1_N18") (pintype "passive"))
      (node (ref "XP2") (pin "2") (pinfunction "2_2") (pintype "passive"))
    )
    (net (code "202") (name "/UD1_P") (class "Default")
      (node (ref "DD1") (pin "N17") (pinfunction "UDP1_N17") (pintype "passive"))
      (node (ref "XP2") (pin "3") (pinfunction "3_3") (pintype "passive"))
    )
    (net (code "203") (name "/USB0_DET#") (class "Default")
      (node (ref "DD1") (pin "H2") (pinfunction "PG12/SPI1_MISO/UART3_RTS/EINT12_H2") (pintype "passive"))
      (node (ref "R59") (pin "1") (pintype "passive"))
      (node (ref "XP4") (pin "ID") (pinfunction "ID_ID") (pintype "passive"))
    )
    (net (code "204") (name "/USB1-DRV") (class "Default")
      (node (ref "DD1") (pin "C15") (pinfunction "PD1/LCD_D1_C15") (pintype "passive"))
      (node (ref "DD4") (pin "4") (pinfunction "EN_4") (pintype "passive"))
      (node (ref "R45") (pin "2") (pintype "passive"))
    )
    (net (code "205") (name "/VBAT_RTC_3V") (class "Default")
      (node (ref "VD4") (pin "2") (pinfunction "2_2") (pintype "passive"))
      (node (ref "XP8") (pin "2") (pinfunction "2_2") (pintype "passive"))
    )
    (net (code "206") (name "/VDD_HDMI") (class "Default")
      (node (ref "C83") (pin "2") (pintype "passive"))
      (node (ref "C84") (pin "2") (pintype "passive"))
      (node (ref "DD1") (pin "R16") (pinfunction "V33_HDMI_R16") (pintype "passive"))
      (node (ref "R56") (pin "2") (pintype "passive"))
    )
    (net (code "207") (name "/VDD_RTC") (class "Default")
      (node (ref "C73") (pin "2") (pintype "passive"))
      (node (ref "DD7") (pin "8") (pinfunction "VDD_8") (pintype "passive"))
      (node (ref "R75") (pin "1") (pintype "passive"))
      (node (ref "R93") (pin "1") (pintype "passive"))
      (node (ref "VD4") (pin "3") (pinfunction "3_3") (pintype "passive"))
    )
    (net (code "208") (name "/VMIC") (class "Default")
      (node (ref "DD1") (pin "Y16") (pinfunction "VMIC_Y16") (pintype "passive"))
      (node (ref "R63") (pin "2") (pintype "passive"))
      (node (ref "XP10") (pin "12") (pinfunction "12_12") (pintype "passive"))
    )
    (net (code "209") (name "/VRA1") (class "Default")
      (node (ref "C59") (pin "1") (pintype "passive"))
      (node (ref "DD1") (pin "V15") (pinfunction "VRA1_V15") (pintype "passive"))
    )
    (net (code "210") (name "/VRA2") (class "Default")
      (node (ref "C62") (pin "1") (pintype "passive"))
      (node (ref "DD1") (pin "V14") (pinfunction "VRA2_V14") (pintype "passive"))
      (node (ref "R49") (pin "2") (pintype "passive"))
    )
    (net (code "211") (name "/VRP") (class "Default")
      (node (ref "C64") (pin "1") (pintype "passive"))
      (node (ref "DD1") (pin "W14") (pinfunction "VRP_W14") (pintype "passive"))
    )
    (net (code "212") (name "/WE") (class "Default")
      (node (ref "DD1") (pin "V3") (pinfunction "SWE/DDR2_CKE0/DDR3_WE_V3") (pintype "passive"))
      (node (ref "DD3") (pin "H3") (pinfunction "#WE_H3") (pintype "passive"))
      (node (ref "DD6") (pin "H3") (pinfunction "#WE_H3") (pintype "passive"))
    )
    (net (code "213") (name "1V5") (class "Default")
      (node (ref "C1") (pin "2") (pintype "passive"))
      (node (ref "C10") (pin "2") (pintype "passive"))
      (node (ref "C11") (pin "2") (pintype "passive"))
      (node (ref "C117") (pin "2") (pintype "passive"))
      (node (ref "C118") (pin "2") (pintype "passive"))
      (node (ref "C14") (pin "2") (pintype "passive"))
      (node (ref "C15") (pin "2") (pintype "passive"))
      (node (ref "C19") (pin "2") (pintype "passive"))
      (node (ref "C2") (pin "2") (pintype "passive"))
      (node (ref "C20") (pin "2") (pintype "passive"))
      (node (ref "C21") (pin "2") (pintype "passive"))
      (node (ref "C22") (pin "2") (pintype "passive"))
      (node (ref "C23") (pin "2") (pintype "passive"))
      (node (ref "C25") (pin "2") (pintype "passive"))
      (node (ref "C3") (pin "2") (pintype "passive"))
      (node (ref "C37") (pin "2") (pintype "passive"))
      (node (ref "C38") (pin "2") (pintype "passive"))
      (node (ref "C42") (pin "2") (pintype "passive"))
      (node (ref "C43") (pin "2") (pintype "passive"))
      (node (ref "C44") (pin "2") (pintype "passive"))
      (node (ref "C45") (pin "2") (pintype "passive"))
      (node (ref "C46") (pin "2") (pintype "passive"))
      (node (ref "C6") (pin "2") (pintype "passive"))
      (node (ref "C7") (pin "2") (pintype "passive"))
      (node (ref "C8") (pin "2") (pintype "passive"))
      (node (ref "C9") (pin "2") (pintype "passive"))
      (node (ref "DD1") (pin "M5") (pinfunction "VCC_DRAM_1_M5") (pintype "passive"))
      (node (ref "DD1") (pin "N5") (pinfunction "VCC_DRAM_2_N5") (pintype "passive"))
      (node (ref "DD1") (pin "T10") (pinfunction "VCC_DRAM_6_T10") (pintype "passive"))
      (node (ref "DD1") (pin "T11") (pinfunction "VCC_DRAM_7_T11") (pintype "passive"))
      (node (ref "DD1") (pin "T5") (pinfunction "VCC_DRAM_3_T5") (pintype "passive"))
      (node (ref "DD1") (pin "T6") (pinfunction "VCC_DRAM_4_T6") (pintype "passive"))
      (node (ref "DD1") (pin "T9") (pinfunction "VCC_DRAM_5_T9") (pintype "passive"))
      (node (ref "DD3") (pin "A2") (pinfunction "VDD_A2") (pintype "passive"))
      (node (ref "DD3") (pin "A9") (pinfunction "VDD_A9") (pintype "passive"))
      (node (ref "DD3") (pin "B9") (pinfunction "VDDQ_B9") (pintype "passive"))
      (node (ref "DD3") (pin "C1") (pinfunction "VDDQ_C1") (pintype "passive"))
      (node (ref "DD3") (pin "D7") (pinfunction "VDD_D7") (pintype "passive"))
      (node (ref "DD3") (pin "E2") (pinfunction "VDDQ_E2") (pintype "passive"))
      (node (ref "DD3") (pin "E9") (pinfunction "VDDQ_E9") (pintype "passive"))
      (node (ref "DD3") (pin "G2") (pinfunction "VDD_G2") (pintype "passive"))
      (node (ref "DD3") (pin "G8") (pinfunction "VDD_G8") (pintype "passive"))
      (node (ref "DD3") (pin "K1") (pinfunction "VDD_K1") (pintype "passive"))
      (node (ref "DD3") (pin "K9") (pinfunction "VDD_K9") (pintype "passive"))
      (node (ref "DD3") (pin "M1") (pinfunction "VDD_M1") (pintype "passive"))
      (node (ref "DD3") (pin "M9") (pinfunction "VDD_M9") (pintype "passive"))
      (node (ref "DD5") (pin "5") (pinfunction "Vout_1V5_5") (pintype "passive"))
      (node (ref "DD6") (pin "A2") (pinfunction "VDD_A2") (pintype "passive"))
      (node (ref "DD6") (pin "A9") (pinfunction "VDD_A9") (pintype "passive"))
      (node (ref "DD6") (pin "B9") (pinfunction "VDDQ_B9") (pintype "passive"))
      (node (ref "DD6") (pin "C1") (pinfunction "VDDQ_C1") (pintype "passive"))
      (node (ref "DD6") (pin "D7") (pinfunction "VDD_D7") (pintype "passive"))
      (node (ref "DD6") (pin "E2") (pinfunction "VDDQ_E2") (pintype "passive"))
      (node (ref "DD6") (pin "E9") (pinfunction "VDDQ_E9") (pintype "passive"))
      (node (ref "DD6") (pin "G2") (pinfunction "VDD_G2") (pintype "passive"))
      (node (ref "DD6") (pin "G8") (pinfunction "VDD_G8") (pintype "passive"))
      (node (ref "DD6") (pin "K1") (pinfunction "VDD_K1") (pintype "passive"))
      (node (ref "DD6") (pin "K9") (pinfunction "VDD_K9") (pintype "passive"))
      (node (ref "DD6") (pin "M1") (pinfunction "VDD_M1") (pintype "passive"))
      (node (ref "DD6") (pin "M9") (pinfunction "VDD_M9") (pintype "passive"))
      (node (ref "R30") (pin "2") (pintype "passive"))
    )
    (net (code "214") (name "3V3") (class "Default")
      (node (ref "C101") (pin "1") (pintype "passive"))
      (node (ref "C102") (pin "1") (pintype "passive"))
      (node (ref "C105") (pin "2") (pintype "passive"))
      (node (ref "C106") (pin "2") (pintype "passive"))
      (node (ref "C107") (pin "2") (pintype "passive"))
      (node (ref "C108") (pin "2") (pintype "passive"))
      (node (ref "C109") (pin "2") (pintype "passive"))
      (node (ref "C110") (pin "2") (pintype "passive"))
      (node (ref "C111") (pin "2") (pintype "passive"))
      (node (ref "C112") (pin "2") (pintype "passive"))
      (node (ref "C12") (pin "2") (pintype "passive"))
      (node (ref "C120") (pin "2") (pintype "passive"))
      (node (ref "C13") (pin "2") (pintype "passive"))
      (node (ref "C47") (pin "2") (pintype "passive"))
      (node (ref "C72") (pin "2") (pintype "passive"))
      (node (ref "C74") (pin "2") (pintype "passive"))
      (node (ref "C75") (pin "2") (pintype "passive"))
      (node (ref "C76") (pin "2") (pintype "passive"))
      (node (ref "C77") (pin "2") (pintype "passive"))
      (node (ref "C79") (pin "1") (pintype "passive"))
      (node (ref "C86") (pin "1") (pintype "passive"))
      (node (ref "C90") (pin "1") (pintype "passive"))
      (node (ref "DD1") (pin "E5") (pinfunction "VCC_1_E5") (pintype "passive"))
      (node (ref "DD1") (pin "F5") (pinfunction "VCC_2_F5") (pintype "passive"))
      (node (ref "DD1") (pin "G16") (pinfunction "VCC_3_G16") (pintype "passive"))
      (node (ref "DD1") (pin "H16") (pinfunction "VCC_4_H16") (pintype "passive"))
      (node (ref "DD1") (pin "J16") (pinfunction "VCC_5_J16") (pintype "passive"))
      (node (ref "DD1") (pin "K16") (pinfunction "VCC_6_K16") (pintype "passive"))
      (node (ref "DD1") (pin "L16") (pinfunction "VCC_7_L16") (pintype "passive"))
      (node (ref "DD1") (pin "P16") (pinfunction "V33_USB_P16") (pintype "passive"))
      (node (ref "DD1") (pin "T14") (pinfunction "V33_HP_T14") (pintype "passive"))
      (node (ref "DD10") (pin "3") (pinfunction "VCC_3") (pintype "power_in"))
      (node (ref "DD2") (pin "14") (pinfunction "DVDD33_14") (pintype "passive"))
      (node (ref "DD2") (pin "37") (pinfunction "ANE_37") (pintype "passive"))
      (node (ref "DD2") (pin "38") (pinfunction "DUPLEX_38") (pintype "passive"))
      (node (ref "DD2") (pin "39") (pinfunction "SPEED_39") (pintype "passive"))
      (node (ref "DD2") (pin "41") (pinfunction "LDPS_41") (pintype "passive"))
      (node (ref "DD2") (pin "44") (pinfunction "MII/SNIB_44") (pintype "passive"))
      (node (ref "DD2") (pin "48") (pinfunction "DVDD33_48") (pintype "passive"))
      (node (ref "DD5") (pin "3") (pinfunction "EN_3") (pintype "passive"))
      (node (ref "DD8") (pin "1") (pinfunction "EN_1") (pintype "passive"))
      (node (ref "L1") (pin "2") (pinfunction "2_2") (pintype "passive"))
      (node (ref "L7") (pin "2") (pinfunction "2_2") (pintype "passive"))
      (node (ref "R12") (pin "1") (pintype "passive"))
      (node (ref "R25") (pin "2") (pintype "passive"))
      (node (ref "R3") (pin "1") (pintype "passive"))
      (node (ref "R32") (pin "2") (pintype "passive"))
      (node (ref "R34") (pin "2") (pintype "passive"))
      (node (ref "R35") (pin "2") (pintype "passive"))
      (node (ref "R36") (pin "2") (pintype "passive"))
      (node (ref "R37") (pin "2") (pintype "passive"))
      (node (ref "R38") (pin "2") (pintype "passive"))
      (node (ref "R39") (pin "2") (pintype "passive"))
      (node (ref "R4") (pin "2") (pintype "passive"))
      (node (ref "R40") (pin "2") (pintype "passive"))
      (node (ref "R43") (pin "1") (pintype "passive"))
      (node (ref "R44") (pin "1") (pintype "passive"))
      (node (ref "R56") (pin "1") (pintype "passive"))
      (node (ref "R59") (pin "2") (pintype "passive"))
      (node (ref "R65") (pin "2") (pintype "passive"))
      (node (ref "R66") (pin "1") (pintype "passive"))
      (node (ref "R69") (pin "2") (pintype "passive"))
      (node (ref "R72") (pin "1") (pintype "passive"))
      (node (ref "R74") (pin "2") (pintype "passive"))
      (node (ref "R76") (pin "2") (pintype "passive"))
      (node (ref "R77") (pin "2") (pintype "passive"))
      (node (ref "R78") (pin "2") (pintype "passive"))
      (node (ref "R80") (pin "2") (pintype "passive"))
      (node (ref "VD11") (pin "2") (pinfunction "2_2") (pintype "passive"))
      (node (ref "VD12") (pin "2") (pinfunction "2_2") (pintype "passive"))
      (node (ref "VD13") (pin "2") (pinfunction "2_2") (pintype "passive"))
      (node (ref "VD14") (pin "2") (pinfunction "2_2") (pintype "passive"))
      (node (ref "VD4") (pin "1") (pinfunction "1_1") (pintype "passive"))
      (node (ref "VD5") (pin "1") (pinfunction "1_1") (pintype "passive"))
      (node (ref "VD5") (pin "2") (pinfunction "2_2") (pintype "passive"))
      (node (ref "VD7") (pin "2") (pinfunction "2_2") (pintype "passive"))
      (node (ref "XP10") (pin "8") (pinfunction "8_8") (pintype "passive"))
      (node (ref "XP11") (pin "18") (pinfunction "18_18") (pintype "passive"))
      (node (ref "XP11") (pin "30") (pinfunction "30_30") (pintype "passive"))
      (node (ref "XP7") (pin "1") (pinfunction "1_1") (pintype "passive"))
      (node (ref "XP9") (pin "1") (pinfunction "1_1") (pintype "passive"))
      (node (ref "XS1") (pin "9") (pintype "passive"))
      (node (ref "XS2") (pin "4") (pinfunction "VDD_4") (pintype "power_in"))
    )
    (net (code "215") (name "5V") (class "Default")
      (node (ref "C115") (pin "2") (pintype "passive"))
      (node (ref "C127") (pin "2") (pintype "passive"))
      (node (ref "C128") (pin "2") (pintype "passive"))
      (node (ref "C129") (pin "2") (pintype "passive"))
      (node (ref "C130") (pin "2") (pintype "passive"))
      (node (ref "C131") (pin "2") (pintype "passive"))
      (node (ref "C132") (pin "2") (pintype "passive"))
      (node (ref "C133") (pin "2") (pintype "passive"))
      (node (ref "C134") (pin "2") (pintype "passive"))
      (node (ref "C136") (pin "2") (pintype "passive"))
      (node (ref "C141") (pin "2") (pintype "passive"))
      (node (ref "C81") (pin "2") (pintype "passive"))
      (node (ref "C93") (pin "2") (pintype "passive"))
      (node (ref "C94") (pin "2") (pintype "passive"))
      (node (ref "C95") (pin "2") (pintype "passive"))
      (node (ref "C96") (pin "2") (pintype "passive"))
      (node (ref "DD4") (pin "5") (pinfunction "IN_5") (pintype "passive"))
      (node (ref "DD5") (pin "1") (pinfunction "Vin_1") (pintype "passive"))
      (node (ref "DD8") (pin "4") (pinfunction "VIN_4") (pintype "passive"))
      (node (ref "DD9") (pin "1") (pinfunction "EN_1") (pintype "passive"))
      (node (ref "DD9") (pin "4") (pinfunction "VIN_4") (pintype "passive"))
      (node (ref "L12") (pin "2") (pinfunction "2_2") (pintype "passive"))
      (node (ref "R33") (pin "1") (pintype "passive"))
      (node (ref "R68") (pin "2") (pintype "passive"))
      (node (ref "R70") (pin "2") (pintype "passive"))
      (node (ref "R87") (pin "2") (pintype "passive"))
      (node (ref "R88") (pin "1") (pintype "passive"))
      (node (ref "VD10") (pin "2") (pinfunction "2_2") (pintype "passive"))
      (node (ref "VD3") (pin "1") (pinfunction "1_1") (pintype "passive"))
      (node (ref "VD3") (pin "2") (pinfunction "2_2") (pintype "passive"))
      (node (ref "VD8") (pin "2") (pinfunction "2_2") (pintype "passive"))
      (node (ref "VD9") (pin "2") (pinfunction "2_2") (pintype "passive"))
      (node (ref "XP10") (pin "5") (pinfunction "5_5") (pintype "passive"))
      (node (ref "XP10") (pin "6") (pinfunction "6_6") (pintype "passive"))
      (node (ref "XP4") (pin "VBUS") (pinfunction "VBUS_VBUS") (pintype "passive"))
    )
    (net (code "216") (name "12V") (class "Default")
      (node (ref "C123") (pin "2") (pintype "passive"))
      (node (ref "C124") (pin "2") (pintype "passive"))
      (node (ref "C125") (pin "2") (pintype "passive"))
      (node (ref "C140") (pin "2") (pintype "passive"))
      (node (ref "C91") (pin "2") (pintype "passive"))
      (node (ref "C92") (pin "2") (pintype "passive"))
      (node (ref "DD11") (pin "2") (pinfunction "Vin_2") (pintype "passive"))
      (node (ref "R85") (pin "2") (pintype "passive"))
      (node (ref "VD6") (pin "1") (pinfunction "1_1") (pintype "passive"))
      (node (ref "XP10") (pin "1") (pinfunction "1_1") (pintype "passive"))
      (node (ref "XP10") (pin "2") (pinfunction "2_2") (pintype "passive"))
      (node (ref "XP13") (pin "1") (pinfunction "+_1") (pintype "passive"))
    )
    (net (code "217") (name "AGND") (class "Default")
      (node (ref "C63") (pin "2") (pintype "passive"))
      (node (ref "R48") (pin "2") (pintype "passive"))
      (node (ref "XP2") (pin "P1") (pinfunction "6_P1") (pintype "passive"))
      (node (ref "XP2") (pin "P2") (pinfunction "5_P2") (pintype "passive"))
      (node (ref "XP2") (pin "P3") (pinfunction "5_P3") (pintype "passive"))
      (node (ref "XP2") (pin "P4") (pinfunction "6_P4") (pintype "passive"))
      (node (ref "XP4") (pin "GND1") (pinfunction "GND1_GND1") (pintype "passive"))
      (node (ref "XP4") (pin "GND2") (pinfunction "GND2_GND2") (pintype "passive"))
      (node (ref "XP4") (pin "GND3") (pinfunction "GND3_GND3") (pintype "passive"))
    )
    (net (code "218") (name "AVCC3V") (class "Default")
      (node (ref "C122") (pin "2") (pintype "passive"))
      (node (ref "C82") (pin "1") (pintype "passive"))
      (node (ref "DD1") (pin "T15") (pinfunction "AVCC_T15") (pintype "passive"))
      (node (ref "L11") (pin "2") (pinfunction "2_2") (pintype "passive"))
    )
    (net (code "219") (name "CPU_VDD") (class "Default")
      (node (ref "C100") (pin "1") (pintype "passive"))
      (node (ref "C103") (pin "2") (pintype "passive"))
      (node (ref "C104") (pin "2") (pintype "passive"))
      (node (ref "C49") (pin "1") (pintype "passive"))
      (node (ref "C50") (pin "1") (pintype "passive"))
      (node (ref "C51") (pin "1") (pintype "passive"))
      (node (ref "C54") (pin "2") (pintype "passive"))
      (node (ref "C55") (pin "2") (pintype "passive"))
      (node (ref "C56") (pin "2") (pintype "passive"))
      (node (ref "C57") (pin "2") (pintype "passive"))
      (node (ref "C58") (pin "2") (pintype "passive"))
      (node (ref "C60") (pin "1") (pintype "passive"))
      (node (ref "C61") (pin "1") (pintype "passive"))
      (node (ref "C65") (pin "2") (pintype "passive"))
      (node (ref "C66") (pin "1") (pintype "passive"))
      (node (ref "C67") (pin "1") (pintype "passive"))
      (node (ref "C97") (pin "1") (pintype "passive"))
      (node (ref "C98") (pin "1") (pintype "passive"))
      (node (ref "C99") (pin "1") (pintype "passive"))
      (node (ref "DD1") (pin "E10") (pinfunction "VDD_CPU_5_E10") (pintype "passive"))
      (node (ref "DD1") (pin "E11") (pinfunction "VDD_CPU_6_E11") (pintype "passive"))
      (node (ref "DD1") (pin "E12") (pinfunction "VDD_CPU_7_E12") (pintype "passive"))
      (node (ref "DD1") (pin "E13") (pinfunction "VDD_CPU_8_E13") (pintype "passive"))
      (node (ref "DD1") (pin "E14") (pinfunction "VDD_CPU_9_E14") (pintype "passive"))
      (node (ref "DD1") (pin "E15") (pinfunction "VDD_CORE_1_E15") (pintype "passive"))
      (node (ref "DD1") (pin "E16") (pinfunction "VDD_CORE_2_E16") (pintype "passive"))
      (node (ref "DD1") (pin "E6") (pinfunction "VDD_CPU_1_E6") (pintype "passive"))
      (node (ref "DD1") (pin "E7") (pinfunction "VDD_CPU_2_E7") (pintype "passive"))
      (node (ref "DD1") (pin "E8") (pinfunction "VDD_CPU_3_E8") (pintype "passive"))
      (node (ref "DD1") (pin "E9") (pinfunction "VDD_CPU_4_E9") (pintype "passive"))
      (node (ref "DD1") (pin "F16") (pinfunction "VDD_CORE_3_F16") (pintype "passive"))
      (node (ref "DD1") (pin "H4") (pinfunction "VDD_CORE_4_H4") (pintype "passive"))
      (node (ref "DD1") (pin "H5") (pinfunction "VDD_CORE_5_H5") (pintype "passive"))
      (node (ref "DD1") (pin "J4") (pinfunction "VDD_DLL_1_J4") (pintype "passive"))
      (node (ref "DD1") (pin "J5") (pinfunction "VDD_DLL_2_J5") (pintype "passive"))
      (node (ref "DD1") (pin "M16") (pinfunction "VDD_CORE_6_M16") (pintype "passive"))
      (node (ref "DD1") (pin "M17") (pinfunction "VDD_CORE_7_M17") (pintype "passive"))
      (node (ref "DD1") (pin "T13") (pinfunction "VDD_CORE_8_T13") (pintype "passive"))
      (node (ref "DD1") (pin "U13") (pinfunction "VDD_CORE_9_U13") (pintype "passive"))
      (node (ref "L5") (pin "2") (pinfunction "2_2") (pintype "passive"))
      (node (ref "R79") (pin "2") (pintype "passive"))
    )
    (net (code "220") (name "GND") (class "Default")
      (node (ref "BT1") (pin "2") (pinfunction "2_2") (pintype "passive"))
      (node (ref "C1") (pin "1") (pintype "passive"))
      (node (ref "C10") (pin "1") (pintype "passive"))
      (node (ref "C100") (pin "2") (pintype "passive"))
      (node (ref "C102") (pin "2") (pintype "passive"))
      (node (ref "C103") (pin "1") (pintype "passive"))
      (node (ref "C104") (pin "1") (pintype "passive"))
      (node (ref "C105") (pin "1") (pintype "passive"))
      (node (ref "C106") (pin "1") (pintype "passive"))
      (node (ref "C107") (pin "1") (pintype "passive"))
      (node (ref "C108") (pin "1") (pintype "passive"))
      (node (ref "C109") (pin "1") (pintype "passive"))
      (node (ref "C11") (pin "1") (pintype "passive"))
      (node (ref "C110") (pin "1") (pintype "passive"))
      (node (ref "C111") (pin "1") (pintype "passive"))
      (node (ref "C112") (pin "1") (pintype "passive"))
      (node (ref "C115") (pin "1") (pintype "passive"))
      (node (ref "C117") (pin "1") (pintype "passive"))
      (node (ref "C118") (pin "1") (pintype "passive"))
      (node (ref "C12") (pin "1") (pintype "passive"))
      (node (ref "C120") (pin "1") (pintype "passive"))
      (node (ref "C121") (pin "1") (pintype "passive"))
      (node (ref "C122") (pin "1") (pintype "passive"))
      (node (ref "C123") (pin "1") (pintype "passive"))
      (node (ref "C124") (pin "1") (pintype "passive"))
      (node (ref "C125") (pin "1") (pintype "passive"))
      (node (ref "C126") (pin "1") (pintype "passive"))
      (node (ref "C127") (pin "1") (pintype "passive"))
      (node (ref "C128") (pin "1") (pintype "passive"))
      (node (ref "C129") (pin "1") (pintype "passive"))
      (node (ref "C13") (pin "1") (pintype "passive"))
      (node (ref "C130") (pin "1") (pintype "passive"))
      (node (ref "C131") (pin "1") (pintype "passive"))
      (node (ref "C132") (pin "1") (pintype "passive"))
      (node (ref "C133") (pin "1") (pintype "passive"))
      (node (ref "C134") (pin "1") (pintype "passive"))
      (node (ref "C136") (pin "1") (pintype "passive"))
      (node (ref "C138") (pin "1") (pintype "passive"))
      (node (ref "C139") (pin "1") (pintype "passive"))
      (node (ref "C14") (pin "1") (pintype "passive"))
      (node (ref "C140") (pin "1") (pintype "passive"))
      (node (ref "C141") (pin "1") (pintype "passive"))
      (node (ref "C142") (pin "1") (pintype "passive"))
      (node (ref "C143") (pin "1") (pintype "passive"))
      (node (ref "C15") (pin "1") (pintype "passive"))
      (node (ref "C16") (pin "2") (pintype "passive"))
      (node (ref "C17") (pin "2") (pintype "passive"))
      (node (ref "C18") (pin "2") (pintype "passive"))
      (node (ref "C19") (pin "1") (pintype "passive"))
      (node (ref "C2") (pin "1") (pintype "passive"))
      (node (ref "C20") (pin "1") (pintype "passive"))
      (node (ref "C21") (pin "1") (pintype "passive"))
      (node (ref "C22") (pin "1") (pintype "passive"))
      (node (ref "C23") (pin "1") (pintype "passive"))
      (node (ref "C24") (pin "1") (pintype "passive"))
      (node (ref "C25") (pin "1") (pintype "passive"))
      (node (ref "C26") (pin "1") (pintype "passive"))
      (node (ref "C27") (pin "1") (pintype "passive"))
      (node (ref "C28") (pin "1") (pintype "passive"))
      (node (ref "C29") (pin "1") (pintype "passive"))
      (node (ref "C3") (pin "1") (pintype "passive"))
      (node (ref "C30") (pin "1") (pintype "passive"))
      (node (ref "C31") (pin "1") (pintype "passive"))
      (node (ref "C32") (pin "1") (pintype "passive"))
      (node (ref "C33") (pin "1") (pintype "passive"))
      (node (ref "C34") (pin "1") (pintype "passive"))
      (node (ref "C35") (pin "1") (pintype "passive"))
      (node (ref "C36") (pin "1") (pintype "passive"))
      (node (ref "C38") (pin "1") (pintype "passive"))
      (node (ref "C39") (pin "1") (pintype "passive"))
      (node (ref "C4") (pin "1") (pintype "passive"))
      (node (ref "C40") (pin "1") (pintype "passive"))
      (node (ref "C41") (pin "1") (pintype "passive"))
      (node (ref "C42") (pin "1") (pintype "passive"))
      (node (ref "C43") (pin "1") (pintype "passive"))
      (node (ref "C44") (pin "1") (pintype "passive"))
      (node (ref "C45") (pin "1") (pintype "passive"))
      (node (ref "C46") (pin "1") (pintype "passive"))
      (node (ref "C47") (pin "1") (pintype "passive"))
      (node (ref "C48") (pin "1") (pintype "passive"))
      (node (ref "C49") (pin "2") (pintype "passive"))
      (node (ref "C5") (pin "1") (pintype "passive"))
      (node (ref "C50") (pin "2") (pintype "passive"))
      (node (ref "C51") (pin "2") (pintype "passive"))
      (node (ref "C52") (pin "1") (pintype "passive"))
      (node (ref "C53") (pin "1") (pintype "passive"))
      (node (ref "C54") (pin "1") (pintype "passive"))
      (node (ref "C55") (pin "1") (pintype "passive"))
      (node (ref "C56") (pin "1") (pintype "passive"))
      (node (ref "C57") (pin "1") (pintype "passive"))
      (node (ref "C58") (pin "1") (pintype "passive"))
      (node (ref "C59") (pin "2") (pintype "passive"))
      (node (ref "C6") (pin "1") (pintype "passive"))
      (node (ref "C60") (pin "2") (pintype "passive"))
      (node (ref "C61") (pin "2") (pintype "passive"))
      (node (ref "C62") (pin "2") (pintype "passive"))
      (node (ref "C63") (pin "1") (pintype "passive"))
      (node (ref "C64") (pin "2") (pintype "passive"))
      (node (ref "C65") (pin "1") (pintype "passive"))
      (node (ref "C66") (pin "2") (pintype "passive"))
      (node (ref "C67") (pin "2") (pintype "passive"))
      (node (ref "C68") (pin "2") (pintype "passive"))
      (node (ref "C69") (pin "2") (pintype "passive"))
      (node (ref "C7") (pin "1") (pintype "passive"))
      (node (ref "C70") (pin "2") (pintype "passive"))
      (node (ref "C72") (pin "1") (pintype "passive"))
      (node (ref "C73") (pin "1") (pintype "passive"))
      (node (ref "C74") (pin "1") (pintype "passive"))
      (node (ref "C75") (pin "1") (pintype "passive"))
      (node (ref "C76") (pin "1") (pintype "passive"))
      (node (ref "C77") (pin "1") (pintype "passive"))
      (node (ref "C79") (pin "2") (pintype "passive"))
      (node (ref "C8") (pin "1") (pintype "passive"))
      (node (ref "C81") (pin "1") (pintype "passive"))
      (node (ref "C82") (pin "2") (pintype "passive"))
      (node (ref "C83") (pin "1") (pintype "passive"))
      (node (ref "C84") (pin "1") (pintype "passive"))
      (node (ref "C85") (pin "2") (pintype "passive"))
      (node (ref "C86") (pin "2") (pintype "passive"))
      (node (ref "C89") (pin "2") (pintype "passive"))
      (node (ref "C9") (pin "1") (pintype "passive"))
      (node (ref "C90") (pin "2") (pintype "passive"))
      (node (ref "C91") (pin "1") (pintype "passive"))
      (node (ref "C92") (pin "1") (pintype "passive"))
      (node (ref "C93") (pin "1") (pintype "passive"))
      (node (ref "C94") (pin "1") (pintype "passive"))
      (node (ref "C95") (pin "1") (pintype "passive"))
      (node (ref "C96") (pin "1") (pintype "passive"))
      (node (ref "C98") (pin "2") (pintype "passive"))
      (node (ref "C99") (pin "2") (pintype "passive"))
      (node (ref "DD1") (pin "D4") (pinfunction "TEST_D4") (pintype "passive"))
      (node (ref "DD1") (pin "G5") (pinfunction "VDD_EFUSE_G5") (pintype "passive"))
      (node (ref "DD1") (pin "H10") (pinfunction "GND_3_H10") (pintype "passive"))
      (node (ref "DD1") (pin "H11") (pinfunction "GND_4_H11") (pintype "passive"))
      (node (ref "DD1") (pin "H12") (pinfunction "GND_5_H12") (pintype "passive"))
      (node (ref "DD1") (pin "H13") (pinfunction "GND_6_H13") (pintype "passive"))
      (node (ref "DD1") (pin "H8") (pinfunction "GND_1_H8") (pintype "passive"))
      (node (ref "DD1") (pin "H9") (pinfunction "GND_2_H9") (pintype "passive"))
      (node (ref "DD1") (pin "J10") (pinfunction "GND_9_J10") (pintype "passive"))
      (node (ref "DD1") (pin "J11") (pinfunction "GND_10_J11") (pintype "passive"))
      (node (ref "DD1") (pin "J12") (pinfunction "GND_11_J12") (pintype "passive"))
      (node (ref "DD1") (pin "J13") (pinfunction "GND_12_J13") (pintype "passive"))
      (node (ref "DD1") (pin "J8") (pinfunction "GND_7_J8") (pintype "passive"))
      (node (ref "DD1") (pin "J9") (pinfunction "GND_8_J9") (pintype "passive"))
      (node (ref "DD1") (pin "K10") (pinfunction "GND_15_K10") (pintype "passive"))
      (node (ref "DD1") (pin "K11") (pinfunction "GND_16_K11") (pintype "passive"))
      (node (ref "DD1") (pin "K12") (pinfunction "GND_17_K12") (pintype "passive"))
      (node (ref "DD1") (pin "K13") (pinfunction "GND_18_K13") (pintype "passive"))
      (node (ref "DD1") (pin "K4") (pinfunction "GND_DLL_1_K4") (pintype "passive"))
      (node (ref "DD1") (pin "K5") (pinfunction "GND_DLL_2_K5") (pintype "passive"))
      (node (ref "DD1") (pin "K8") (pinfunction "GND_13_K8") (pintype "passive"))
      (node (ref "DD1") (pin "K9") (pinfunction "GND_14_K9") (pintype "passive"))
      (node (ref "DD1") (pin "L10") (pinfunction "GND_21_L10") (pintype "passive"))
      (node (ref "DD1") (pin "L11") (pinfunction "GND_22_L11") (pintype "passive"))
      (node (ref "DD1") (pin "L12") (pinfunction "GND_23_L12") (pintype "passive"))
      (node (ref "DD1") (pin "L13") (pinfunction "GND_24_L13") (pintype "passive"))
      (node (ref "DD1") (pin "L5") (pinfunction "GND_DRAM_1_L5") (pintype "passive"))
      (node (ref "DD1") (pin "L8") (pinfunction "GND_19_L8") (pintype "passive"))
      (node (ref "DD1") (pin "L9") (pinfunction "GND_20_L9") (pintype "passive"))
      (node (ref "DD1") (pin "M10") (pinfunction "GND_27_M10") (pintype "passive"))
      (node (ref "DD1") (pin "M11") (pinfunction "GND_28_M11") (pintype "passive"))
      (node (ref "DD1") (pin "M12") (pinfunction "GND_29_M12") (pintype "passive"))
      (node (ref "DD1") (pin "M13") (pinfunction "GND_30_M13") (pintype "passive"))
      (node (ref "DD1") (pin "M8") (pinfunction "GND_25_M8") (pintype "passive"))
      (node (ref "DD1") (pin "M9") (pinfunction "GND_26_M9") (pintype "passive"))
      (node (ref "DD1") (pin "N10") (pinfunction "GND_33_N10") (pintype "passive"))
      (node (ref "DD1") (pin "N11") (pinfunction "GND_34_N11") (pintype "passive"))
      (node (ref "DD1") (pin "N12") (pinfunction "GND_35_N12") (pintype "passive"))
      (node (ref "DD1") (pin "N13") (pinfunction "GND_36_N13") (pintype "passive"))
      (node (ref "DD1") (pin "N16") (pinfunction "GND_USB_N16") (pintype "passive"))
      (node (ref "DD1") (pin "N8") (pinfunction "GND_31_N8") (pintype "passive"))
      (node (ref "DD1") (pin "N9") (pinfunction "GND_32_N9") (pintype "passive"))
      (node (ref "DD1") (pin "P5") (pinfunction "GND_DRAM_2_P5") (pintype "passive"))
      (node (ref "DD1") (pin "R5") (pinfunction "GND_DRAM_3_R5") (pintype "passive"))
      (node (ref "DD1") (pin "T12") (pinfunction "GND_DRAM_6_T12") (pintype "passive"))
      (node (ref "DD1") (pin "T7") (pinfunction "GND_DRAM_4_T7") (pintype "passive"))
      (node (ref "DD1") (pin "T8") (pinfunction "GND_DRAM_5_T8") (pintype "passive"))
      (node (ref "DD1") (pin "U12") (pinfunction "GND_DRAM_7_U12") (pintype "passive"))
      (node (ref "DD1") (pin "U15") (pinfunction "GND_HP_U15") (pintype "passive"))
      (node (ref "DD1") (pin "U16") (pinfunction "AGND_U16") (pintype "passive"))
      (node (ref "DD1") (pin "V19") (pinfunction "GND_37_V19") (pintype "passive"))
      (node (ref "DD10") (pin "1") (pinfunction "GND_1") (pintype "passive"))
      (node (ref "DD11") (pin "1") (pinfunction "PGND_1") (pintype "passive"))
      (node (ref "DD11") (pin "3") (pinfunction "AGND_3") (pintype "passive"))
      (node (ref "DD2") (pin "11") (pinfunction "DGND_11") (pintype "passive"))
      (node (ref "DD2") (pin "17") (pinfunction "DGND_17") (pintype "passive"))
      (node (ref "DD2") (pin "29") (pinfunction "AGND_29") (pintype "passive"))
      (node (ref "DD2") (pin "35") (pinfunction "AGND_35") (pintype "passive"))
      (node (ref "DD2") (pin "40") (pinfunction "RPTR_40") (pintype "passive"))
      (node (ref "DD2") (pin "43") (pinfunction "ISOLATE_43") (pintype "passive"))
      (node (ref "DD2") (pin "45") (pinfunction "DGND_45") (pintype "passive"))
      (node (ref "DD3") (pin "A1") (pinfunction "VSS_A1") (pintype "passive"))
      (node (ref "DD3") (pin "A8") (pinfunction "VSS_A8") (pintype "passive"))
      (node (ref "DD3") (pin "B1") (pinfunction "VSS_B1") (pintype "passive"))
      (node (ref "DD3") (pin "B2") (pinfunction "VSSQ_B2") (pintype "passive"))
      (node (ref "DD3") (pin "B8") (pinfunction "VSSQ_B8") (pintype "passive"))
      (node (ref "DD3") (pin "C9") (pinfunction "VSSQ_C9") (pintype "passive"))
      (node (ref "DD3") (pin "D1") (pinfunction "VSSQ_D1") (pintype "passive"))
      (node (ref "DD3") (pin "D8") (pinfunction "VSS_D8") (pintype "passive"))
      (node (ref "DD3") (pin "D9") (pinfunction "VSSQ_D9") (pintype "passive"))
      (node (ref "DD3") (pin "F2") (pinfunction "VSS_F2") (pintype "passive"))
      (node (ref "DD3") (pin "F8") (pinfunction "VSS_F8") (pintype "passive"))
      (node (ref "DD3") (pin "J1") (pinfunction "VSS_J1") (pintype "passive"))
      (node (ref "DD3") (pin "J9") (pinfunction "VSS_J9") (pintype "passive"))
      (node (ref "DD3") (pin "L1") (pinfunction "VSS_L1") (pintype "passive"))
      (node (ref "DD3") (pin "L9") (pinfunction "VSS_L9") (pintype "passive"))
      (node (ref "DD3") (pin "N1") (pinfunction "VSS_N1") (pintype "passive"))
      (node (ref "DD3") (pin "N9") (pinfunction "VSS_N9") (pintype "passive"))
      (node (ref "DD4") (pin "2") (pinfunction "GND_2") (pintype "passive"))
      (node (ref "DD5") (pin "2") (pinfunction "GND_2") (pintype "passive"))
      (node (ref "DD6") (pin "A1") (pinfunction "VSS_A1") (pintype "passive"))
      (node (ref "DD6") (pin "A8") (pinfunction "VSS_A8") (pintype "passive"))
      (node (ref "DD6") (pin "B1") (pinfunction "VSS_B1") (pintype "passive"))
      (node (ref "DD6") (pin "B2") (pinfunction "VSSQ_B2") (pintype "passive"))
      (node (ref "DD6") (pin "B8") (pinfunction "VSSQ_B8") (pintype "passive"))
      (node (ref "DD6") (pin "C9") (pinfunction "VSSQ_C9") (pintype "passive"))
      (node (ref "DD6") (pin "D1") (pinfunction "VSSQ_D1") (pintype "passive"))
      (node (ref "DD6") (pin "D8") (pinfunction "VSS_D8") (pintype "passive"))
      (node (ref "DD6") (pin "D9") (pinfunction "VSSQ_D9") (pintype "passive"))
      (node (ref "DD6") (pin "F2") (pinfunction "VSS_F2") (pintype "passive"))
      (node (ref "DD6") (pin "F8") (pinfunction "VSS_F8") (pintype "passive"))
      (node (ref "DD6") (pin "J1") (pinfunction "VSS_J1") (pintype "passive"))
      (node (ref "DD6") (pin "J9") (pinfunction "VSS_J9") (pintype "passive"))
      (node (ref "DD6") (pin "L1") (pinfunction "VSS_L1") (pintype "passive"))
      (node (ref "DD6") (pin "L9") (pinfunction "VSS_L9") (pintype "passive"))
      (node (ref "DD6") (pin "N1") (pinfunction "VSS_N1") (pintype "passive"))
      (node (ref "DD6") (pin "N9") (pinfunction "VSS_N9") (pintype "passive"))
      (node (ref "DD7") (pin "4") (pinfunction "VSS_4") (pintype "passive"))
      (node (ref "DD8") (pin "2") (pinfunction "GND_2") (pintype "passive"))
      (node (ref "DD9") (pin "2") (pinfunction "GND_2") (pintype "passive"))
      (node (ref "LED1") (pin "1") (pinfunction "K_1") (pintype "passive"))
      (node (ref "LED2") (pin "1") (pinfunction "K_1") (pintype "passive"))
      (node (ref "R10") (pin "1") (pintype "passive"))
      (node (ref "R11") (pin "2") (pintype "passive"))
      (node (ref "R16") (pin "1") (pintype "passive"))
      (node (ref "R17") (pin "1") (pintype "passive"))
      (node (ref "R18") (pin "1") (pintype "passive"))
      (node (ref "R24") (pin "2") (pintype "passive"))
      (node (ref "R28") (pin "2") (pintype "passive"))
      (node (ref "R29") (pin "1") (pintype "passive"))
      (node (ref "R31") (pin "2") (pintype "passive"))
      (node (ref "R45") (pin "1") (pintype "passive"))
      (node (ref "R46") (pin "1") (pintype "passive"))
      (node (ref "R48") (pin "1") (pintype "passive"))
      (node (ref "R49") (pin "1") (pintype "passive"))
      (node (ref "R5") (pin "2") (pintype "passive"))
      (node (ref "R53") (pin "2") (pintype "passive"))
      (node (ref "R57") (pin "1") (pintype "passive"))
      (node (ref "R58") (pin "1") (pintype "passive"))
      (node (ref "R6") (pin "2") (pintype "passive"))
      (node (ref "R60") (pin "1") (pintype "passive"))
      (node (ref "R61") (pin "1") (pintype "passive"))
      (node (ref "R71") (pin "1") (pintype "passive"))
      (node (ref "R8") (pin "2") (pintype "passive"))
      (node (ref "R81") (pin "1") (pintype "passive"))
      (node (ref "R82") (pin "1") (pintype "passive"))
      (node (ref "R90") (pin "1") (pintype "passive"))
      (node (ref "VD1") (pin "38") (pinfunction "GND_38") (pintype "passive"))
      (node (ref "VD10") (pin "1") (pinfunction "1_1") (pintype "passive"))
      (node (ref "VD11") (pin "1") (pinfunction "1_1") (pintype "passive"))
      (node (ref "VD12") (pin "1") (pinfunction "1_1") (pintype "passive"))
      (node (ref "VD13") (pin "1") (pinfunction "1_1") (pintype "passive"))
      (node (ref "VD14") (pin "1") (pinfunction "1_1") (pintype "passive"))
      (node (ref "VD2") (pin "38") (pinfunction "GND_38") (pintype "passive"))
      (node (ref "VD6") (pin "2") (pinfunction "2_2") (pintype "passive"))
      (node (ref "VD7") (pin "1") (pinfunction "1_1") (pintype "passive"))
      (node (ref "VD8") (pin "1") (pinfunction "1_1") (pintype "passive"))
      (node (ref "VD9") (pin "1") (pinfunction "1_1") (pintype "passive"))
      (node (ref "XP10") (pin "15") (pinfunction "15_15") (pintype "passive"))
      (node (ref "XP10") (pin "21") (pinfunction "21_21") (pintype "passive"))
      (node (ref "XP10") (pin "3") (pinfunction "3_3") (pintype "passive"))
      (node (ref "XP10") (pin "4") (pinfunction "4_4") (pintype "passive"))
      (node (ref "XP10") (pin "7") (pinfunction "7_7") (pintype "passive"))
      (node (ref "XP11") (pin "24") (pinfunction "24_24") (pintype "passive"))
      (node (ref "XP11") (pin "27") (pinfunction "27_27") (pintype "passive"))
      (node (ref "XP11") (pin "5") (pinfunction "5_5") (pintype "passive"))
      (node (ref "XP11") (pin "6") (pinfunction "6_6") (pintype "passive"))
      (node (ref "XP13") (pin "2") (pinfunction "-_2") (pintype "passive"))
      (node (ref "XP14") (pin "2") (pinfunction "2_2") (pintype "passive"))
      (node (ref "XP2") (pin "4") (pinfunction "4_4") (pintype "passive"))
      (node (ref "XP3") (pin "2") (pinfunction "2_2") (pintype "passive"))
      (node (ref "XP3") (pin "5") (pinfunction "5_5") (pintype "passive"))
      (node (ref "XP4") (pin "GND") (pinfunction "GND_GND") (pintype "passive"))
      (node (ref "XP5") (pin "11") (pinfunction "11_11") (pintype "passive"))
      (node (ref "XP5") (pin "17") (pinfunction "17_17") (pintype "passive"))
      (node (ref "XP5") (pin "2") (pinfunction "2_2") (pintype "passive"))
      (node (ref "XP5") (pin "5") (pinfunction "5_5") (pintype "passive"))
      (node (ref "XP5") (pin "8") (pinfunction "8_8") (pintype "passive"))
      (node (ref "XP5") (pin "P1") (pinfunction "P1_P1") (pintype "passive"))
      (node (ref "XP5") (pin "P2") (pinfunction "P2_P2") (pintype "passive"))
      (node (ref "XP5") (pin "P3") (pinfunction "P3_P3") (pintype "passive"))
      (node (ref "XP5") (pin "P4") (pinfunction "P4_P4") (pintype "passive"))
      (node (ref "XP6") (pin "1") (pinfunction "1_1") (pintype "passive"))
      (node (ref "XP7") (pin "2") (pinfunction "2_2") (pintype "passive"))
      (node (ref "XP8") (pin "1") (pinfunction "1_1") (pintype "passive"))
      (node (ref "XP9") (pin "4") (pinfunction "4_4") (pintype "passive"))
      (node (ref "XS1") (pin "11") (pintype "passive"))
      (node (ref "XS2") (pin "11") (pinfunction "S_11") (pintype "passive"))
      (node (ref "XS2") (pin "12") (pinfunction "S_12") (pintype "passive"))
      (node (ref "XS2") (pin "13") (pinfunction "S_13") (pintype "passive"))
      (node (ref "XS2") (pin "6") (pinfunction "VSS_6") (pintype "power_in"))
    )
    (net (code "221") (name "Net-(C39-Pad2)") (class "Default")
      (node (ref "C39") (pin "2") (pintype "passive"))
      (node (ref "R20") (pin "1") (pintype "passive"))
      (node (ref "R21") (pin "1") (pintype "passive"))
    )
    (net (code "222") (name "Net-(C40-Pad2)") (class "Default")
      (node (ref "C40") (pin "2") (pintype "passive"))
      (node (ref "R22") (pin "1") (pintype "passive"))
      (node (ref "R23") (pin "1") (pintype "passive"))
    )
    (net (code "223") (name "Net-(C68-Pad1)") (class "Default")
      (node (ref "C68") (pin "1") (pintype "passive"))
      (node (ref "R50") (pin "1") (pintype "passive"))
    )
    (net (code "224") (name "Net-(C69-Pad1)") (class "Default")
      (node (ref "C69") (pin "1") (pintype "passive"))
      (node (ref "R51") (pin "1") (pintype "passive"))
    )
    (net (code "225") (name "Net-(C70-Pad1)") (class "Default")
      (node (ref "C70") (pin "1") (pintype "passive"))
      (node (ref "R52") (pin "1") (pintype "passive"))
    )
    (net (code "226") (name "Net-(C78-Pad1)") (class "Default")
      (node (ref "C78") (pin "1") (pintype "passive"))
      (node (ref "R57") (pin "2") (pintype "passive"))
      (node (ref "XP3") (pin "3") (pinfunction "3_3") (pintype "passive"))
    )
    (net (code "227") (name "Net-(C80-Pad1)") (class "Default")
      (node (ref "C80") (pin "1") (pintype "passive"))
      (node (ref "R58") (pin "2") (pintype "passive"))
      (node (ref "XP3") (pin "4") (pinfunction "4_4") (pintype "passive"))
    )
    (net (code "228") (name "Net-(C89-Pad1)") (class "Default")
      (node (ref "C89") (pin "1") (pintype "passive"))
      (node (ref "R62") (pin "1") (pintype "passive"))
      (node (ref "R63") (pin "1") (pintype "passive"))
    )
    (net (code "229") (name "Net-(C121-Pad2)") (class "Default")
      (node (ref "C121") (pin "2") (pintype "passive"))
      (node (ref "L11") (pin "1") (pinfunction "1_1") (pintype "passive"))
      (node (ref "VD5") (pin "3") (pinfunction "3_3") (pintype "passive"))
    )
    (net (code "230") (name "Net-(C137-Pad1)") (class "Default")
      (node (ref "C137") (pin "1") (pintype "passive"))
      (node (ref "R88") (pin "2") (pintype "passive"))
    )
    (net (code "231") (name "Net-(C139-Pad2)") (class "Default")
      (node (ref "C139") (pin "2") (pintype "passive"))
      (node (ref "R92") (pin "1") (pintype "passive"))
    )
    (net (code "232") (name "Net-(DD1A-V33_PLL)") (class "Default")
      (node (ref "C85") (pin "1") (pintype "passive"))
      (node (ref "DD1") (pin "T16") (pinfunction "V33_PLL_T16") (pintype "passive"))
    )
    (net (code "233") (name "Net-(DD1B-NMI_N)") (class "Default")
      (node (ref "DD1") (pin "B9") (pinfunction "NMI_N_B9") (pintype "passive"))
      (node (ref "R34") (pin "1") (pintype "passive"))
    )
    (net (code "234") (name "Net-(DD1B-X24MIN)") (class "Default")
      (node (ref "BQ2") (pin "2") (pinfunction "2_2") (pintype "passive"))
      (node (ref "C41") (pin "2") (pintype "passive"))
      (node (ref "DD1") (pin "U20") (pinfunction "X24MIN_U20") (pintype "passive"))
    )
    (net (code "235") (name "Net-(DD1B-X24MOUT)") (class "Default")
      (node (ref "BQ2") (pin "1") (pinfunction "1_1") (pintype "passive"))
      (node (ref "C48") (pin "2") (pintype "passive"))
      (node (ref "DD1") (pin "V20") (pinfunction "X24MOUT_V20") (pintype "passive"))
    )
    (net (code "236") (name "Net-(DD1D-SZQ)") (class "Default")
      (node (ref "DD1") (pin "K3") (pinfunction "SZQ_K3") (pintype "passive"))
      (node (ref "R16") (pin "2") (pintype "passive"))
    )
    (net (code "237") (name "Net-(DD2-AVDD33)") (class "Default")
      (node (ref "C4") (pin "2") (pintype "passive"))
      (node (ref "C5") (pin "2") (pintype "passive"))
      (node (ref "DD2") (pin "36") (pinfunction "AVDD33_36") (pintype "passive"))
      (node (ref "L1") (pin "1") (pinfunction "1_1") (pintype "passive"))
    )
    (net (code "238") (name "Net-(DD2-RESETB)") (class "Default")
      (node (ref "C32") (pin "2") (pintype "passive"))
      (node (ref "DD2") (pin "42") (pinfunction "RESETB_42") (pintype "passive"))
      (node (ref "R12") (pin "2") (pintype "passive"))
      (node (ref "R13") (pin "2") (pintype "passive"))
    )
    (net (code "239") (name "Net-(DD2-RTSET)") (class "Default")
      (node (ref "DD2") (pin "28") (pinfunction "RTSET_28") (pintype "passive"))
      (node (ref "R10") (pin "2") (pintype "passive"))
    )
    (net (code "240") (name "Net-(DD2-X1)") (class "Default")
      (node (ref "BQ1") (pin "1") (pinfunction "1_1") (pintype "passive"))
      (node (ref "C16") (pin "1") (pintype "passive"))
      (node (ref "DD2") (pin "46") (pinfunction "X1_46") (pintype "passive"))
    )
    (net (code "241") (name "Net-(DD2-X2)") (class "Default")
      (node (ref "BQ1") (pin "2") (pinfunction "2_2") (pintype "passive"))
      (node (ref "C17") (pin "1") (pintype "passive"))
      (node (ref "DD2") (pin "47") (pinfunction "X2_47") (pintype "passive"))
    )
    (net (code "242") (name "Net-(DD3-ZQ)") (class "Default")
      (node (ref "DD3") (pin "H8") (pinfunction "ZQ_H8") (pintype "passive"))
      (node (ref "R17") (pin "2") (pintype "passive"))
    )
    (net (code "243") (name "Net-(DD4-ISET)") (class "Default")
      (node (ref "DD4") (pin "3") (pinfunction "ISET_3") (pintype "passive"))
      (node (ref "R46") (pin "2") (pintype "passive"))
    )
    (net (code "244") (name "Net-(DD6-ZQ)") (class "Default")
      (node (ref "DD6") (pin "H8") (pinfunction "ZQ_H8") (pintype "passive"))
      (node (ref "R18") (pin "2") (pintype "passive"))
    )
    (net (code "245") (name "Net-(DD7-OCSI)") (class "Default")
      (node (ref "BQ3") (pin "2") (pinfunction "2_2") (pintype "passive"))
      (node (ref "DD7") (pin "1") (pinfunction "OCSI_1") (pintype "passive"))
    )
    (net (code "246") (name "Net-(DD7-OSCO)") (class "Default")
      (node (ref "BQ3") (pin "1") (pinfunction "1_1") (pintype "passive"))
      (node (ref "DD7") (pin "2") (pinfunction "OSCO_2") (pintype "passive"))
    )
    (net (code "247") (name "Net-(DD8-FB)") (class "Default")
      (node (ref "C97") (pin "2") (pintype "passive"))
      (node (ref "DD8") (pin "5") (pinfunction "FB_5") (pintype "passive"))
      (node (ref "R79") (pin "1") (pintype "passive"))
      (node (ref "R81") (pin "2") (pintype "passive"))
    )
    (net (code "248") (name "Net-(DD8-LX)") (class "Default")
      (node (ref "DD8") (pin "3") (pinfunction "LX_3") (pintype "passive"))
      (node (ref "L5") (pin "1") (pinfunction "1_1") (pintype "passive"))
    )
    (net (code "249") (name "Net-(DD9-FB)") (class "Default")
      (node (ref "C101") (pin "2") (pintype "passive"))
      (node (ref "DD9") (pin "5") (pinfunction "FB_5") (pintype "passive"))
      (node (ref "R80") (pin "1") (pintype "passive"))
      (node (ref "R82") (pin "2") (pintype "passive"))
    )
    (net (code "250") (name "Net-(DD9-LX)") (class "Default")
      (node (ref "DD9") (pin "3") (pinfunction "LX_3") (pintype "passive"))
      (node (ref "L7") (pin "1") (pinfunction "1_1") (pintype "passive"))
    )
    (net (code "251") (name "Net-(DD10-RESET)") (class "Default")
      (node (ref "DD10") (pin "2") (pinfunction "RESET_2") (pintype "output"))
      (node (ref "R67") (pin "1") (pintype "passive"))
    )
    (net (code "252") (name "Net-(DD11-COMP)") (class "Default")
      (node (ref "C138") (pin "2") (pintype "passive"))
      (node (ref "DD11") (pin "5") (pinfunction "COMP_5") (pintype "passive"))
      (node (ref "R92") (pin "2") (pintype "passive"))
    )
    (net (code "253") (name "Net-(DD11-EN)") (class "Default")
      (node (ref "C126") (pin "2") (pintype "passive"))
      (node (ref "DD11") (pin "6") (pinfunction "EN_6") (pintype "passive"))
      (node (ref "R85") (pin "1") (pintype "passive"))
    )
    (net (code "254") (name "Net-(DD11-FB)") (class "Default")
      (node (ref "C137") (pin "2") (pintype "passive"))
      (node (ref "DD11") (pin "4") (pinfunction "FB_4") (pintype "passive"))
      (node (ref "R87") (pin "1") (pintype "passive"))
      (node (ref "R90") (pin "2") (pintype "passive"))
    )
    (net (code "255") (name "Net-(DD11-Vsw)") (class "Default")
      (node (ref "DD11") (pin "8") (pinfunction "Vsw_8") (pintype "passive"))
      (node (ref "L12") (pin "1") (pinfunction "1_1") (pintype "passive"))
    )
    (net (code "256") (name "Net-(LED1-A)") (class "Default")
      (node (ref "LED1") (pin "2") (pinfunction "A_2") (pintype "passive"))
      (node (ref "R73") (pin "1") (pintype "passive"))
    )
    (net (code "257") (name "Net-(LED2-A)") (class "Default")
      (node (ref "LED2") (pin "2") (pinfunction "A_2") (pintype "passive"))
      (node (ref "R77") (pin "1") (pintype "passive"))
    )
    (net (code "258") (name "Net-(R1-Pad2)") (class "Default")
      (node (ref "R1") (pin "2") (pintype "passive"))
      (node (ref "XS1") (pin "12") (pintype "passive"))
    )
    (net (code "259") (name "Net-(R2-Pad2)") (class "Default")
      (node (ref "R2") (pin "2") (pintype "passive"))
      (node (ref "XS1") (pin "10") (pintype "passive"))
    )
    (net (code "260") (name "Net-(R64-Pad2)") (class "Default")
      (node (ref "R64") (pin "2") (pintype "passive"))
      (node (ref "XP6") (pin "2") (pinfunction "2_2") (pintype "passive"))
    )
    (net (code "261") (name "Net-(XS1A-SHIELD)") (class "Default")
      (node (ref "R24") (pin "1") (pintype "passive"))
      (node (ref "XS1") (pin "8") (pinfunction "SHIELD_8") (pintype "passive"))
    )
    (net (code "262") (name "Net-(XS2-G)") (class "Default")
      (node (ref "R53") (pin "1") (pintype "passive"))
      (node (ref "XS2") (pin "10") (pinfunction "G_10") (pintype "passive"))
    )
    (net (code "263") (name "unconnected-(DD1A-HPBP-PadU14)") (class "Default")
      (node (ref "DD1") (pin "U14") (pinfunction "HPBP_U14") (pintype "passive"))
    )
    (net (code "264") (name "unconnected-(DD1B-HVREG1-PadU18)") (class "Default")
      (node (ref "DD1") (pin "U18") (pinfunction "HVREG1_U18") (pintype "passive"))
    )
    (net (code "265") (name "unconnected-(DD1B-HVREG2-PadU19)") (class "Default")
      (node (ref "DD1") (pin "U19") (pinfunction "HVREG2_U19") (pintype "passive"))
    )
    (net (code "266") (name "unconnected-(DD1B-MIC1OUTN-PadW18)") (class "Default")
      (node (ref "DD1") (pin "W18") (pinfunction "MIC1OUTN_W18") (pintype "passive"))
    )
    (net (code "267") (name "unconnected-(DD1B-MIC1OUTP-PadW17)") (class "Default")
      (node (ref "DD1") (pin "W17") (pinfunction "MIC1OUTP_W17") (pintype "passive"))
    )
    (net (code "268") (name "unconnected-(DD1B-PLLTEST-PadV17)") (class "Default")
      (node (ref "DD1") (pin "V17") (pinfunction "PLLTEST_V17") (pintype "passive"))
    )
    (net (code "269") (name "unconnected-(DD1C-PC4{slash}NCE0-PadB2)") (class "Default")
      (node (ref "DD1") (pin "B2") (pinfunction "PC4/NCE0_B2") (pintype "passive"))
    )
    (net (code "270") (name "unconnected-(DD1C-PC12{slash}NDQ4{slash}SDC2_D4-PadA4)") (class "Default")
      (node (ref "DD1") (pin "A4") (pinfunction "PC12/NDQ4/SDC2_D4_A4") (pintype "passive"))
    )
    (net (code "271") (name "unconnected-(DD1C-PC13{slash}NDQ5{slash}SDC2_D5-PadD5)") (class "Default")
      (node (ref "DD1") (pin "D5") (pinfunction "PC13/NDQ5/SDC2_D5_D5") (pintype "passive"))
    )
    (net (code "272") (name "unconnected-(DD1C-PC14{slash}NDQ6{slash}SDC2_D6-PadC5)") (class "Default")
      (node (ref "DD1") (pin "C5") (pinfunction "PC14/NDQ6/SDC2_D6_C5") (pintype "passive"))
    )
    (net (code "273") (name "unconnected-(DD1C-PC15{slash}NDQ7{slash}SDC2_D7-PadB5)") (class "Default")
      (node (ref "DD1") (pin "B5") (pinfunction "PC15/NDQ7/SDC2_D7_B5") (pintype "passive"))
    )
    (net (code "274") (name "unconnected-(DD1C-PD0{slash}LCD_D0-PadD15)") (class "Default")
      (node (ref "DD1") (pin "D15") (pinfunction "PD0/LCD_D0_D15") (pintype "passive"))
    )
    (net (code "275") (name "unconnected-(DD1C-PD6{slash}LCD_D6{slash}ECRS-PadB16)") (class "Default")
      (node (ref "DD1") (pin "B16") (pinfunction "PD6/LCD_D6/ECRS_B16") (pintype "passive"))
    )
    (net (code "276") (name "unconnected-(DD1C-PD7{slash}LCD_D7{slash}ECOL-PadA16)") (class "Default")
      (node (ref "DD1") (pin "A16") (pinfunction "PD7/LCD_D7/ECOL_A16") (pintype "passive"))
    )
    (net (code "277") (name "unconnected-(DD1C-PD8{slash}LCD_D8-PadC17)") (class "Default")
      (node (ref "DD1") (pin "C17") (pinfunction "PD8/LCD_D8_C17") (pintype "passive"))
    )
    (net (code "278") (name "unconnected-(DD1C-PD9{slash}LCD_D9-PadB17)") (class "Default")
      (node (ref "DD1") (pin "B17") (pinfunction "PD9/LCD_D9_B17") (pintype "passive"))
    )
    (net (code "279") (name "unconnected-(DD1C-PD10{slash}LCD_D10{slash}ERXDO-PadA17)") (class "Default")
      (node (ref "DD1") (pin "A17") (pinfunction "PD10/LCD_D10/ERXDO_A17") (pintype "passive"))
    )
    (net (code "280") (name "unconnected-(DD1C-PD11{slash}LCD_D11{slash}ERXD1-PadC18)") (class "Default")
      (node (ref "DD1") (pin "C18") (pinfunction "PD11/LCD_D11/ERXD1_C18") (pintype "passive"))
    )
    (net (code "281") (name "unconnected-(DD1C-PD12{slash}LCD_D12{slash}ERXD2-PadB18)") (class "Default")
      (node (ref "DD1") (pin "B18") (pinfunction "PD12/LCD_D12/ERXD2_B18") (pintype "passive"))
    )
    (net (code "282") (name "unconnected-(DD1C-PD13{slash}LCD_D13{slash}ERXD3-PadA18)") (class "Default")
      (node (ref "DD1") (pin "A18") (pinfunction "PD13/LCD_D13/ERXD3_A18") (pintype "passive"))
    )
    (net (code "283") (name "unconnected-(DD1C-PD14{slash}LCD_D14{slash}ERXCK-PadA19)") (class "Default")
      (node (ref "DD1") (pin "A19") (pinfunction "PD14/LCD_D14/ERXCK_A19") (pintype "passive"))
    )
    (net (code "284") (name "unconnected-(DD1C-PD16{slash}LCD_D16-PadB19)") (class "Default")
      (node (ref "DD1") (pin "B19") (pinfunction "PD16/LCD_D16_B19") (pintype "passive"))
    )
    (net (code "285") (name "unconnected-(DD1C-PD18{slash}LCD_D18{slash}ERXDV-PadD17)") (class "Default")
      (node (ref "DD1") (pin "D17") (pinfunction "PD18/LCD_D18/ERXDV_D17") (pintype "passive"))
    )
    (net (code "286") (name "unconnected-(DD1C-PD19{slash}LCD_D19{slash}ETXD0-PadD18)") (class "Default")
      (node (ref "DD1") (pin "D18") (pinfunction "PD19/LCD_D19/ETXD0_D18") (pintype "passive"))
    )
    (net (code "287") (name "unconnected-(DD1C-PD20{slash}LCD_D20{slash}ETXD1-PadE17)") (class "Default")
      (node (ref "DD1") (pin "E17") (pinfunction "PD20/LCD_D20/ETXD1_E17") (pintype "passive"))
    )
    (net (code "288") (name "unconnected-(DD1C-PD21{slash}LCD_D21{slash}ETXD2-PadE18)") (class "Default")
      (node (ref "DD1") (pin "E18") (pinfunction "PD21/LCD_D21/ETXD2_E18") (pintype "passive"))
    )
    (net (code "289") (name "unconnected-(DD1C-PD22{slash}LCD_D22{slash}ETXD3-PadF17)") (class "Default")
      (node (ref "DD1") (pin "F17") (pinfunction "PD22/LCD_D22/ETXD3_F17") (pintype "passive"))
    )
    (net (code "290") (name "unconnected-(DD1C-PD23{slash}LCD_D23{slash}ETXEN-PadF18)") (class "Default")
      (node (ref "DD1") (pin "F18") (pinfunction "PD23/LCD_D23/ETXEN_F18") (pintype "passive"))
    )
    (net (code "291") (name "unconnected-(DD1C-PD24{slash}LCD_CLK{slash}ETXCK-PadG17)") (class "Default")
      (node (ref "DD1") (pin "G17") (pinfunction "PD24/LCD_CLK/ETXCK_G17") (pintype "passive"))
    )
    (net (code "292") (name "unconnected-(DD1C-PD25{slash}LCD_DE{slash}ETXERR-PadG18)") (class "Default")
      (node (ref "DD1") (pin "G18") (pinfunction "PD25/LCD_DE/ETXERR_G18") (pintype "passive"))
    )
    (net (code "293") (name "unconnected-(DD1C-PD26{slash}LCD_HSYNC{slash}EMDC-PadH17)") (class "Default")
      (node (ref "DD1") (pin "H17") (pinfunction "PD26/LCD_HSYNC/EMDC_H17") (pintype "passive"))
    )
    (net (code "294") (name "unconnected-(DD1C-PD27{slash}LCD_VSYNC{slash}EMDIO-PadH18)") (class "Default")
      (node (ref "DD1") (pin "H18") (pinfunction "PD27/LCD_VSYNC/EMDIO_H18") (pintype "passive"))
    )
    (net (code "295") (name "unconnected-(DD1C-PG0{slash}GPS_CLK{slash}EINT0-PadB10)") (class "Default")
      (node (ref "DD1") (pin "B10") (pinfunction "PG0/GPS_CLK/EINT0_B10") (pintype "passive"))
    )
    (net (code "296") (name "unconnected-(DD1C-PG2{slash}GPS_MAG{slash}EINT2-PadB11)") (class "Default")
      (node (ref "DD1") (pin "B11") (pinfunction "PG2/GPS_MAG/EINT2_B11") (pintype "passive"))
    )
    (net (code "297") (name "unconnected-(DD1C-PG5{slash}SDC1_D0{slash}UART1_CTS{slash}EINT5-PadA12)") (class "Default")
      (node (ref "DD1") (pin "A12") (pinfunction "PG5/SDC1_D0/UART1_CTS/EINT5_A12") (pintype "passive"))
    )
    (net (code "298") (name "unconnected-(DD1C-PG6{slash}SDC1_D1{slash}UART1_RTS{slash}UART2_RTS{slash}EINT6-PadB13)") (class "Default")
      (node (ref "DD1") (pin "B13") (pinfunction "PG6/SDC1_D1/UART1_RTS/UART2_RTS/EINT6_B13") (pintype "passive"))
    )
    (net (code "299") (name "unconnected-(DD1C-PG7{slash}SDC1_D2{slash}UART2_TX{slash}EINT7-PadA13)") (class "Default")
      (node (ref "DD1") (pin "A13") (pinfunction "PG7/SDC1_D2/UART2_TX/EINT7_A13") (pintype "passive"))
    )
    (net (code "300") (name "unconnected-(DD1C-PG8{slash}SDC1_D3{slash}UART2_RX{slash}EINT8-PadB14)") (class "Default")
      (node (ref "DD1") (pin "B14") (pinfunction "PG8/SDC1_D3/UART2_RX/EINT8_B14") (pintype "passive"))
    )
    (net (code "301") (name "unconnected-(DD1C-PG11{slash}SPI1_MOSI{slash}UART3_CTS{slash}EINT11-PadH1)") (class "Default")
      (node (ref "DD1") (pin "H1") (pinfunction "PG11/SPI1_MOSI/UART3_CTS/EINT11_H1") (pintype "passive"))
    )
    (net (code "302") (name "unconnected-(DD1C-PG13{slash}SPI1_CS1{slash}PWM1{slash}UART2_CTS{slash}EINT13-PadH3)") (class "Default")
      (node (ref "DD1") (pin "H3") (pinfunction "PG13/SPI1_CS1/PWM1/UART2_CTS/EINT13_H3") (pintype "passive"))
    )
    (net (code "303") (name "unconnected-(DD1D-SDQ16{slash}DDR2_D22-PadW4)") (class "Default")
      (node (ref "DD1") (pin "W4") (pinfunction "SDQ16/DDR2_D22_W4") (pintype "passive"))
    )
    (net (code "304") (name "unconnected-(DD1D-SDQ17{slash}DDR2_D23-PadY11)") (class "Default")
      (node (ref "DD1") (pin "Y11") (pinfunction "SDQ17/DDR2_D23_Y11") (pintype "passive"))
    )
    (net (code "305") (name "unconnected-(DD1D-SDQ18{slash}DDR2_D17-PadY3)") (class "Default")
      (node (ref "DD1") (pin "Y3") (pinfunction "SDQ18/DDR2_D17_Y3") (pintype "passive"))
    )
    (net (code "306") (name "unconnected-(DD1D-SDQ19{slash}DDR2_D16-PadV12)") (class "Default")
      (node (ref "DD1") (pin "V12") (pinfunction "SDQ19/DDR2_D16_V12") (pintype "passive"))
    )
    (net (code "307") (name "unconnected-(DD1D-SDQ20{slash}DDR2_D20-PadY2)") (class "Default")
      (node (ref "DD1") (pin "Y2") (pinfunction "SDQ20/DDR2_D20_Y2") (pintype "passive"))
    )
    (net (code "308") (name "unconnected-(DD1D-SDQ21{slash}DDR2_D21-PadW12)") (class "Default")
      (node (ref "DD1") (pin "W12") (pinfunction "SDQ21/DDR2_D21_W12") (pintype "passive"))
    )
    (net (code "309") (name "unconnected-(DD1D-SDQ22{slash}DDR3_D22-PadW3)") (class "Default")
      (node (ref "DD1") (pin "W3") (pinfunction "SDQ22/DDR3_D22_W3") (pintype "passive"))
    )
    (net (code "310") (name "unconnected-(DD1D-SDQ23{slash}DDR2_D18-PadY12)") (class "Default")
      (node (ref "DD1") (pin "Y12") (pinfunction "SDQ23/DDR2_D18_Y12") (pintype "passive"))
    )
    (net (code "311") (name "unconnected-(DD1D-SDQ24{slash}DDR2_D24-PadY8)") (class "Default")
      (node (ref "DD1") (pin "Y8") (pinfunction "SDQ24/DDR2_D24_Y8") (pintype "passive"))
    )
    (net (code "312") (name "unconnected-(DD1D-SDQ25{slash}DDR2_D27-PadW6)") (class "Default")
      (node (ref "DD1") (pin "W6") (pinfunction "SDQ25/DDR2_D27_W6") (pintype "passive"))
    )
    (net (code "313") (name "unconnected-(DD1D-SDQ26{slash}DDR2_D29-PadY10)") (class "Default")
      (node (ref "DD1") (pin "Y10") (pinfunction "SDQ26/DDR2_D29_Y10") (pintype "passive"))
    )
    (net (code "314") (name "unconnected-(DD1D-SDQ27{slash}DDR2_D28-PadY4)") (class "Default")
      (node (ref "DD1") (pin "Y4") (pinfunction "SDQ27/DDR2_D28_Y4") (pintype "passive"))
    )
    (net (code "315") (name "unconnected-(DD1D-SDQ28{slash}DDR2_D31-PadW10)") (class "Default")
      (node (ref "DD1") (pin "W10") (pinfunction "SDQ28/DDR2_D31_W10") (pintype "passive"))
    )
    (net (code "316") (name "unconnected-(DD1D-SDQ29{slash}DDR2_D25-PadW5)") (class "Default")
      (node (ref "DD1") (pin "W5") (pinfunction "SDQ29/DDR2_D25_W5") (pintype "passive"))
    )
    (net (code "317") (name "unconnected-(DD1D-SDQ30{slash}DDR2_D26-PadW11)") (class "Default")
      (node (ref "DD1") (pin "W11") (pinfunction "SDQ30/DDR2_D26_W11") (pintype "passive"))
    )
    (net (code "318") (name "unconnected-(DD1D-SDQ31{slash}DDR2_D30-PadY5)") (class "Default")
      (node (ref "DD1") (pin "Y5") (pinfunction "SDQ31/DDR2_D30_Y5") (pintype "passive"))
    )
    (net (code "319") (name "unconnected-(DD1D-SDQM2{slash}DDR2_DM2{slash}DDR3_DM2-PadW8)") (class "Default")
      (node (ref "DD1") (pin "W8") (pinfunction "SDQM2/DDR2_DM2/DDR3_DM2_W8") (pintype "passive"))
    )
    (net (code "320") (name "unconnected-(DD1D-SDQM3{slash}DDR2_DM3{slash}DDR3_DM3-PadY6)") (class "Default")
      (node (ref "DD1") (pin "Y6") (pinfunction "SDQM3/DDR2_DM3/DDR3_DM3_Y6") (pintype "passive"))
    )
    (net (code "321") (name "unconnected-(DD1D-SDQS2_N{slash}DDR2_DQS2_N{slash}DDR3_DQS2_N-PadY7)") (class "Default")
      (node (ref "DD1") (pin "Y7") (pinfunction "SDQS2_N/DDR2_DQS2_N/DDR3_DQS2_N_Y7") (pintype "passive"))
    )
    (net (code "322") (name "unconnected-(DD1D-SDQS2{slash}DDR2_DQS2{slash}DDR3_DQS2-PadW7)") (class "Default")
      (node (ref "DD1") (pin "W7") (pinfunction "SDQS2/DDR2_DQS2/DDR3_DQS2_W7") (pintype "passive"))
    )
    (net (code "323") (name "unconnected-(DD1D-SDQS3_N{slash}DDR2_DQS3_N{slash}DDR3_DQS3_N-PadY9)") (class "Default")
      (node (ref "DD1") (pin "Y9") (pinfunction "SDQS3_N/DDR2_DQS3_N/DDR3_DQS3_N_Y9") (pintype "passive"))
    )
    (net (code "324") (name "unconnected-(DD1D-SDQS3{slash}DDR2_DQS3{slash}DDR3_DQS3-PadW9)") (class "Default")
      (node (ref "DD1") (pin "W9") (pinfunction "SDQS3/DDR2_DQS3/DDR3_DQS3_W9") (pintype "passive"))
    )
    (net (code "325") (name "unconnected-(DD2-NC-Pad27)") (class "Default")
      (node (ref "DD2") (pin "27") (pinfunction "NC_27") (pintype "passive"))
    )
    (net (code "326") (name "unconnected-(DD3-NC-PadA3)") (class "Default")
      (node (ref "DD3") (pin "A3") (pinfunction "NC_A3") (pintype "passive"))
    )
    (net (code "327") (name "unconnected-(DD3-NC-PadJ7)") (class "Default")
      (node (ref "DD3") (pin "J7") (pinfunction "NC_J7") (pintype "passive"))
    )
    (net (code "328") (name "unconnected-(DD3-NC{slash}ZQ1-PadH9)") (class "Default")
      (node (ref "DD3") (pin "H9") (pinfunction "NC/ZQ1_H9") (pintype "passive"))
    )
    (net (code "329") (name "unconnected-(DD3-NF{slash}#TDQS-PadA7)") (class "Default")
      (node (ref "DD3") (pin "A7") (pinfunction "NF/#TDQS_A7") (pintype "passive"))
    )
    (net (code "330") (name "unconnected-(DD5-NC-Pad4)") (class "Default")
      (node (ref "DD5") (pin "4") (pinfunction "NC_4") (pintype "passive"))
    )
    (net (code "331") (name "unconnected-(DD6-NC-PadA3)") (class "Default")
      (node (ref "DD6") (pin "A3") (pinfunction "NC_A3") (pintype "passive"))
    )
    (net (code "332") (name "unconnected-(DD6-NC-PadJ7)") (class "Default")
      (node (ref "DD6") (pin "J7") (pinfunction "NC_J7") (pintype "passive"))
    )
    (net (code "333") (name "unconnected-(DD6-NC{slash}ZQ1-PadH9)") (class "Default")
      (node (ref "DD6") (pin "H9") (pinfunction "NC/ZQ1_H9") (pintype "passive"))
    )
    (net (code "334") (name "unconnected-(DD6-NF{slash}#TDQS-PadA7)") (class "Default")
      (node (ref "DD6") (pin "A7") (pinfunction "NF/#TDQS_A7") (pintype "passive"))
    )
    (net (code "335") (name "unconnected-(XP4-PadGND4)") (class "Default")
      (node (ref "XP4") (pin "GND4") (pinfunction "GND4_GND4") (pintype "passive"))
    )
    (net (code "336") (name "unconnected-(XP5-Pad14)") (class "Default")
      (node (ref "XP5") (pin "14") (pinfunction "14_14") (pintype "passive"))
    )
    (net (code "337") (name "unconnected-(XP11-Pad29)") (class "Default")
      (node (ref "XP11") (pin "29") (pinfunction "29_29") (pintype "passive"))
    )
    (net (code "338") (name "unconnected-(XP13-C-Pad3)") (class "Default")
      (node (ref "XP13") (pin "3") (pinfunction "C_3") (pintype "passive"))
    )
    (net (code "339") (name "unconnected-(XS1-Pad113)") (class "Default")
      (node (ref "XS1") (pin "113") (pintype "passive"))
    )
    (net (code "340") (name "unconnected-(XS1-Pad114)") (class "Default")
      (node (ref "XS1") (pin "114") (pintype "passive"))
    )
    (net (code "341") (name "unconnected-(XS1-Pad115)") (class "Default")
      (node (ref "XS1") (pin "115") (pintype "passive"))
    )
    (net (code "342") (name "unconnected-(XS1-Pad116)") (class "Default")
      (node (ref "XS1") (pin "116") (pintype "passive"))
    )
    (net (code "343") (name "unconnected-(XS1-Pad117)") (class "Default")
      (node (ref "XS1") (pin "117") (pintype "passive"))
    )
    (net (code "344") (name "unconnected-(XS1-Pad118)") (class "Default")
      (node (ref "XS1") (pin "118") (pintype "passive"))
    )
    (net (code "345") (name "unconnected-(XS1-Pad119)") (class "Default")
      (node (ref "XS1") (pin "119") (pintype "passive"))
    )
    (net (code "346") (name "unconnected-(XS1-Pad120)") (class "Default")
      (node (ref "XS1") (pin "120") (pintype "passive"))
    )
    (net (code "347") (name "unconnected-(XS1-Pad121)") (class "Default")
      (node (ref "XS1") (pin "121") (pintype "passive"))
    )
  )
)
